# Avalon3.net
KiCad netlist of a schematic drawn in Altium Designer
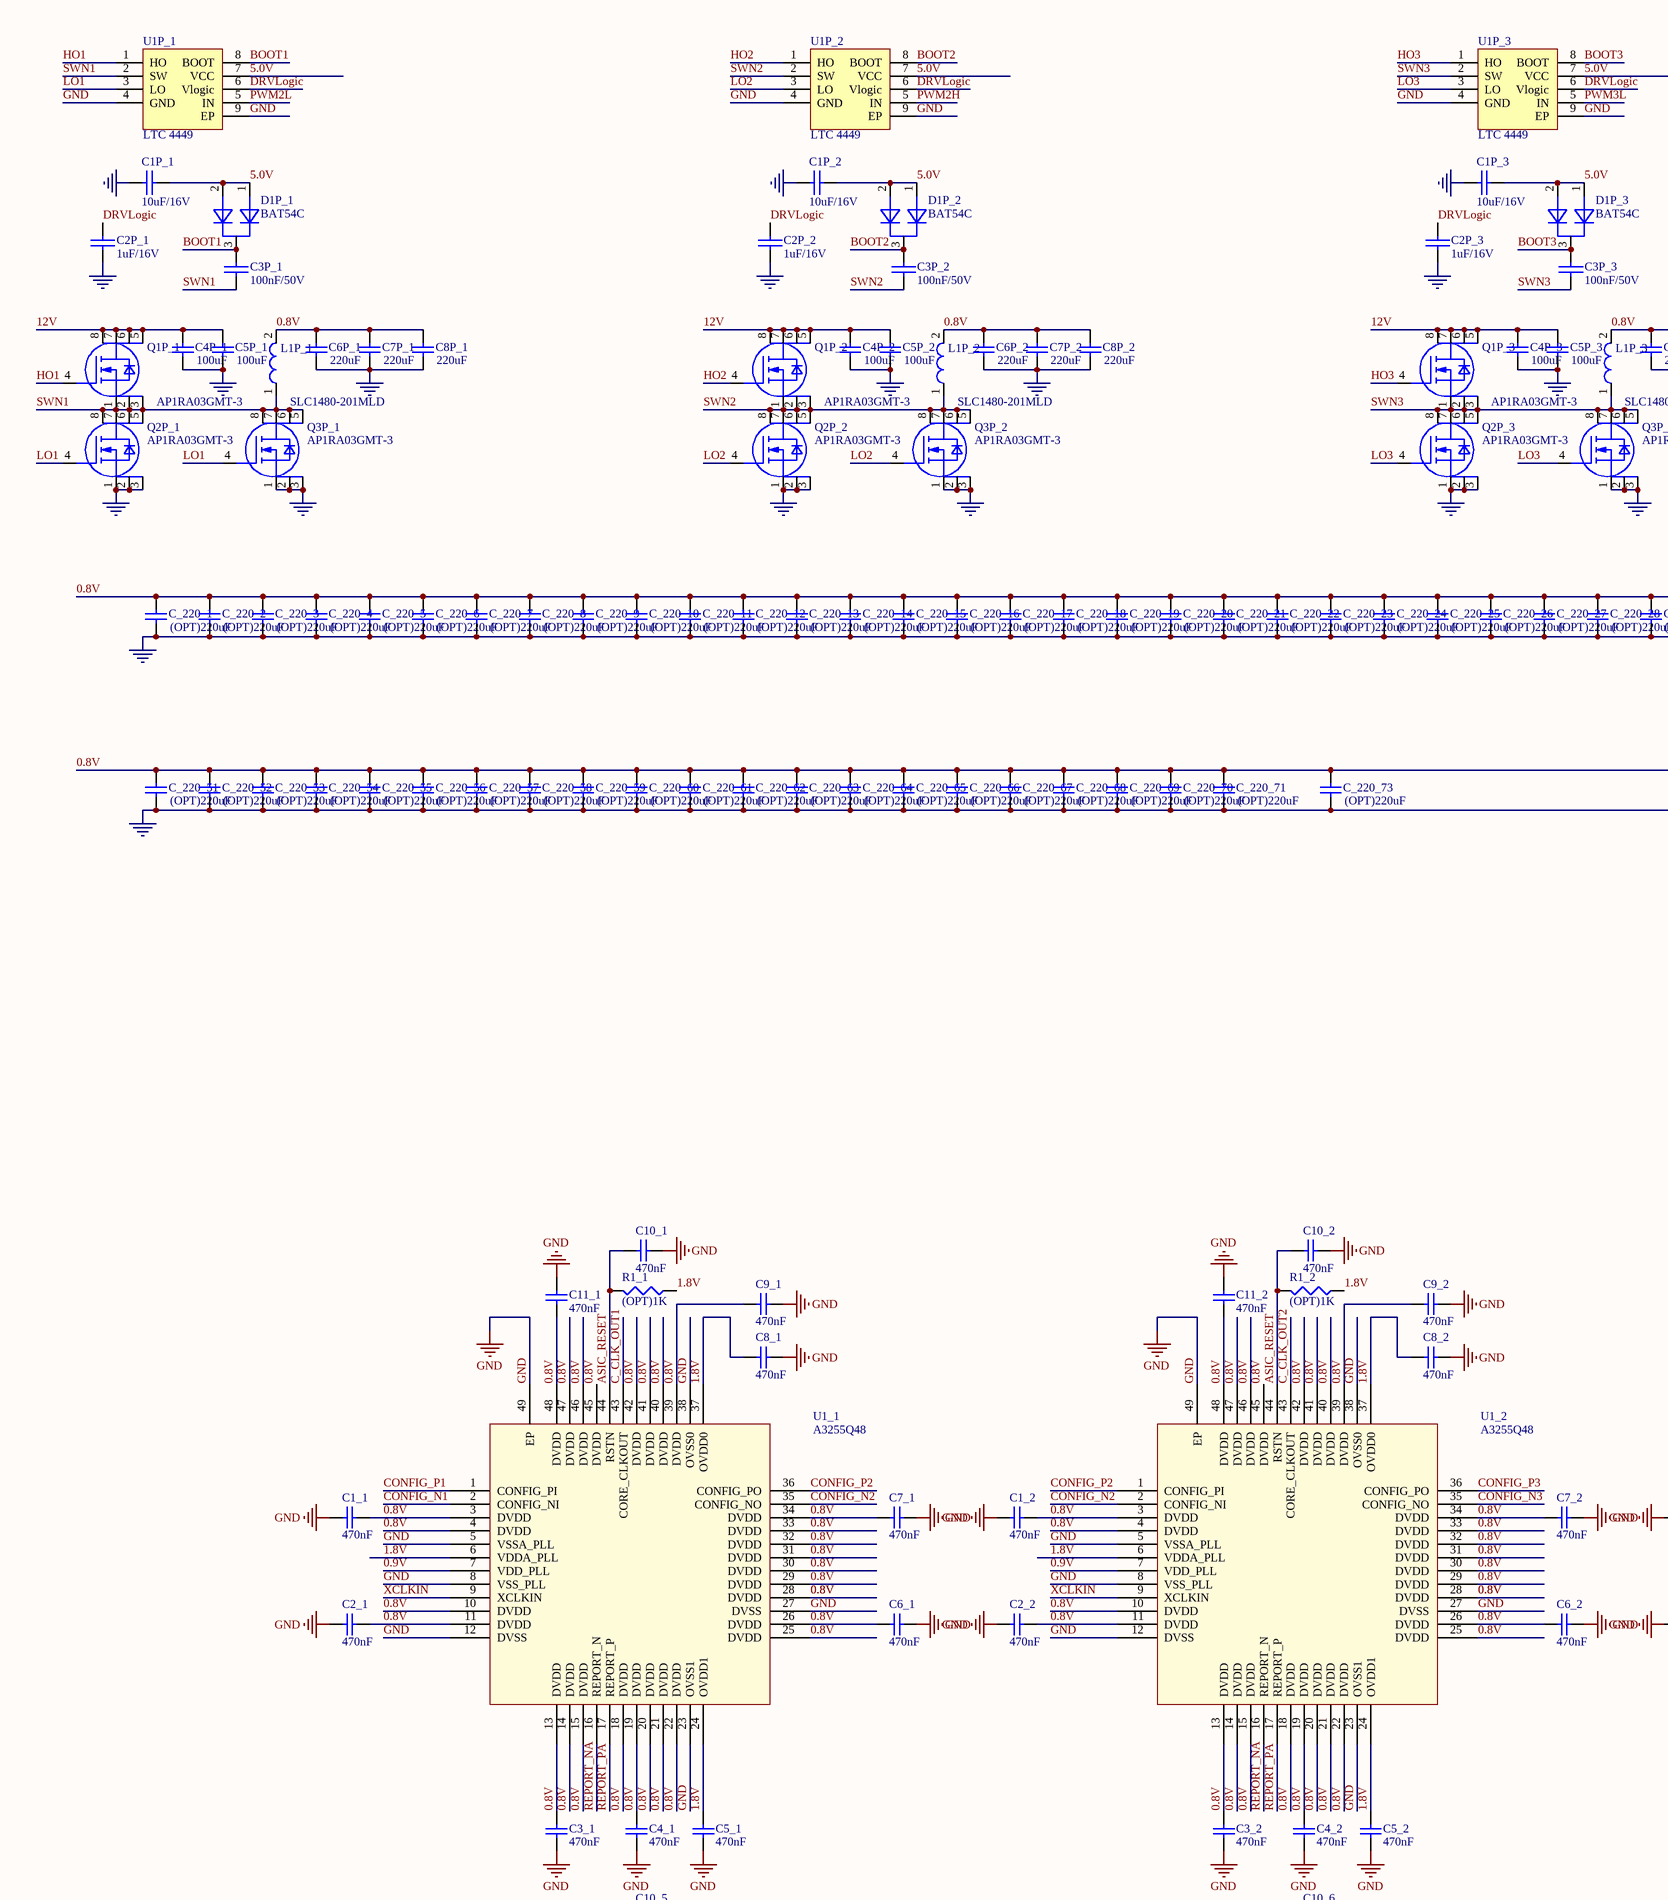
[diagram p0: Avalon3.SchDoc, top left]
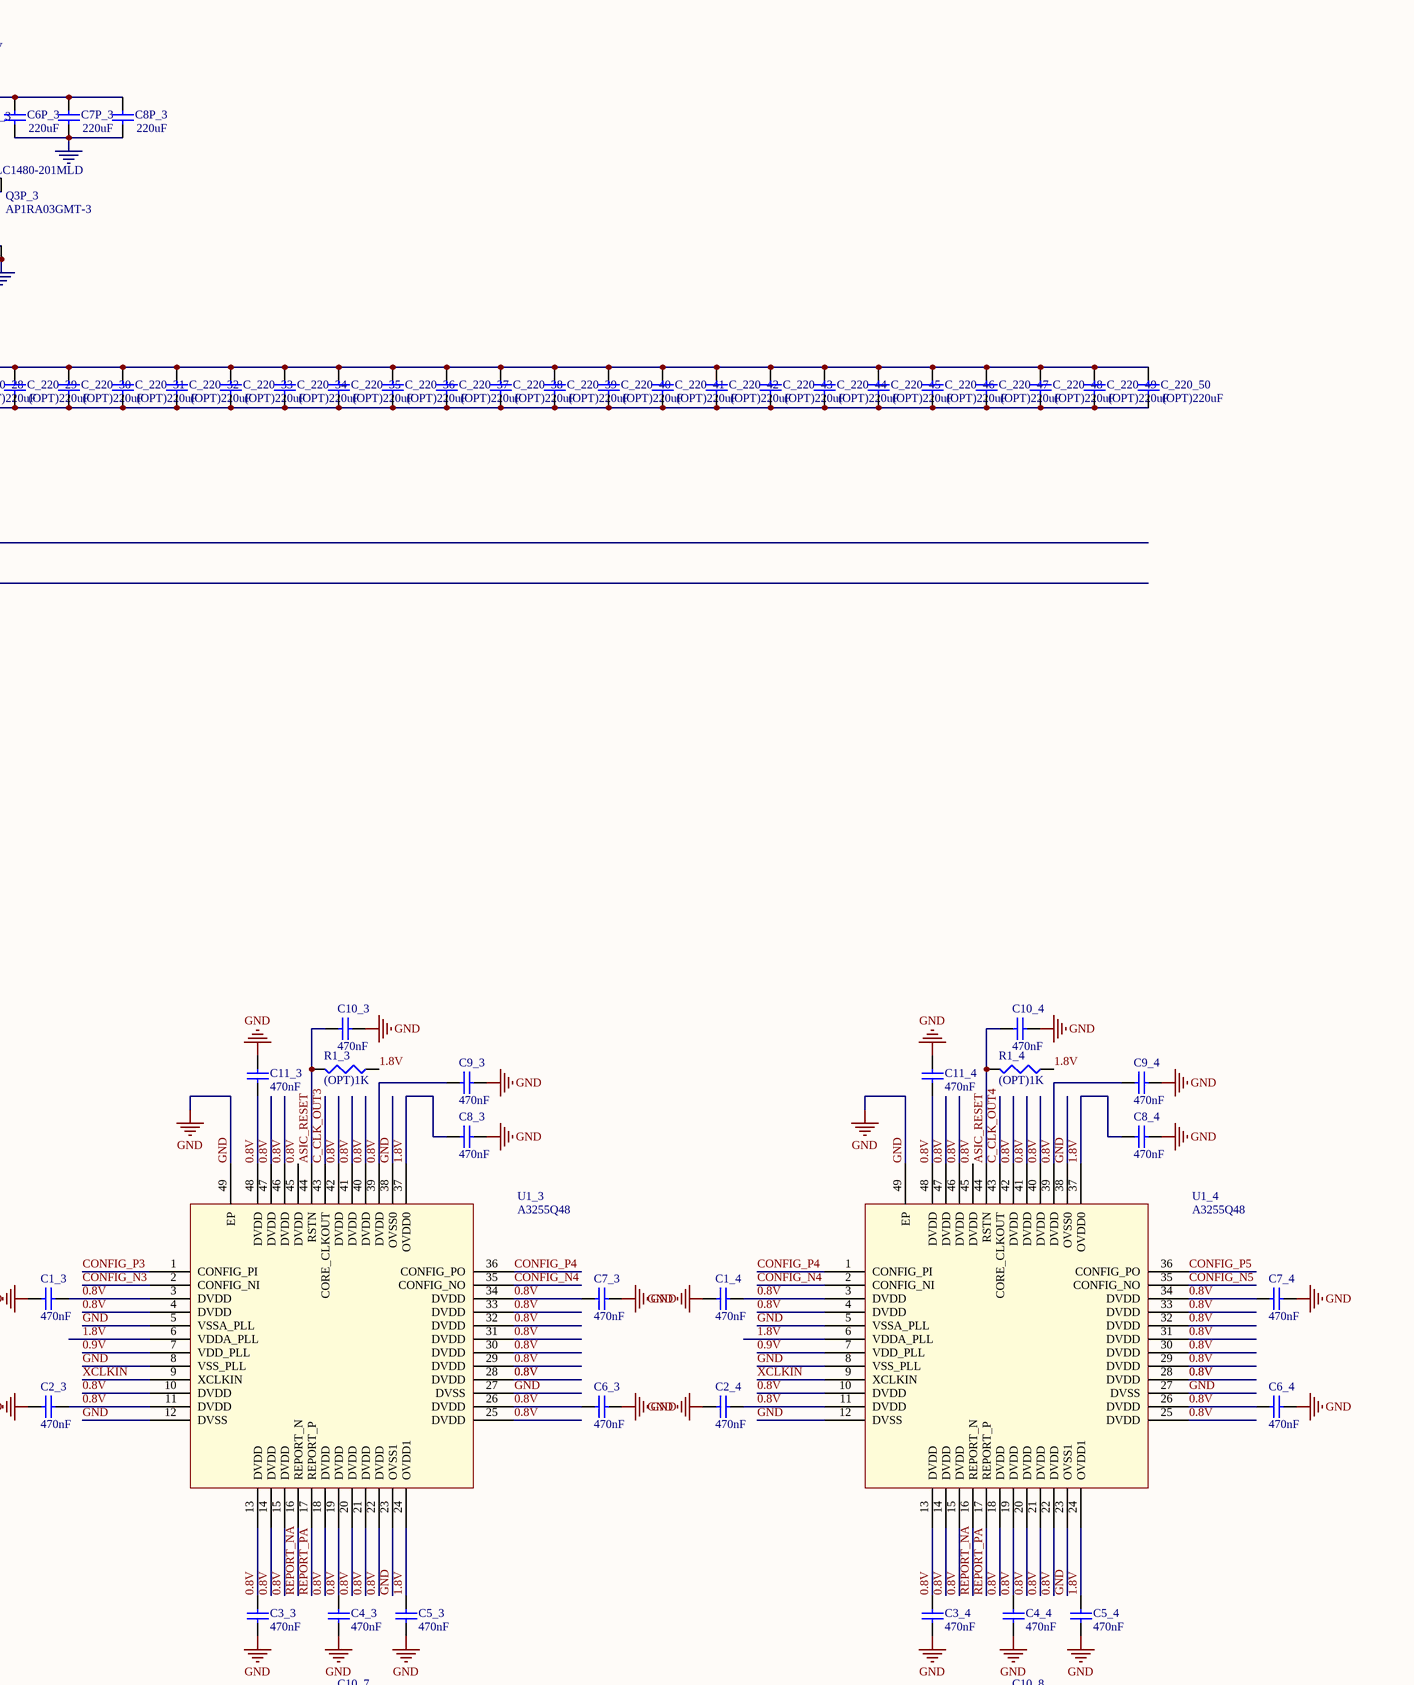
[diagram p1: Avalon3.SchDoc, top middle]
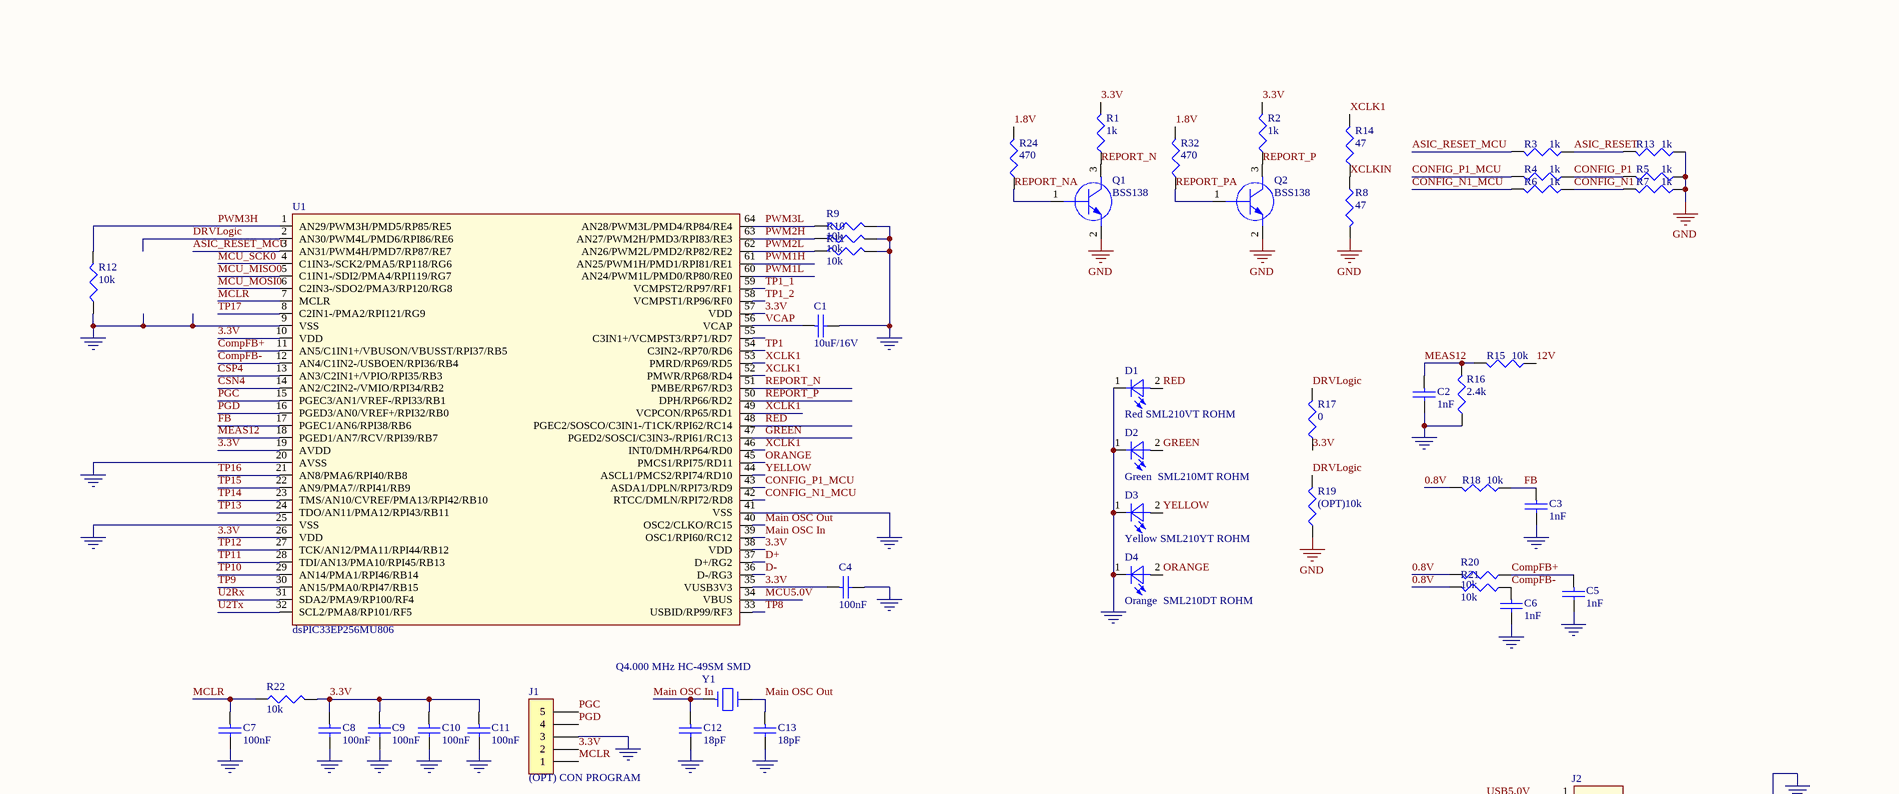
[diagram p2: Avalon3.SchDoc, top right]
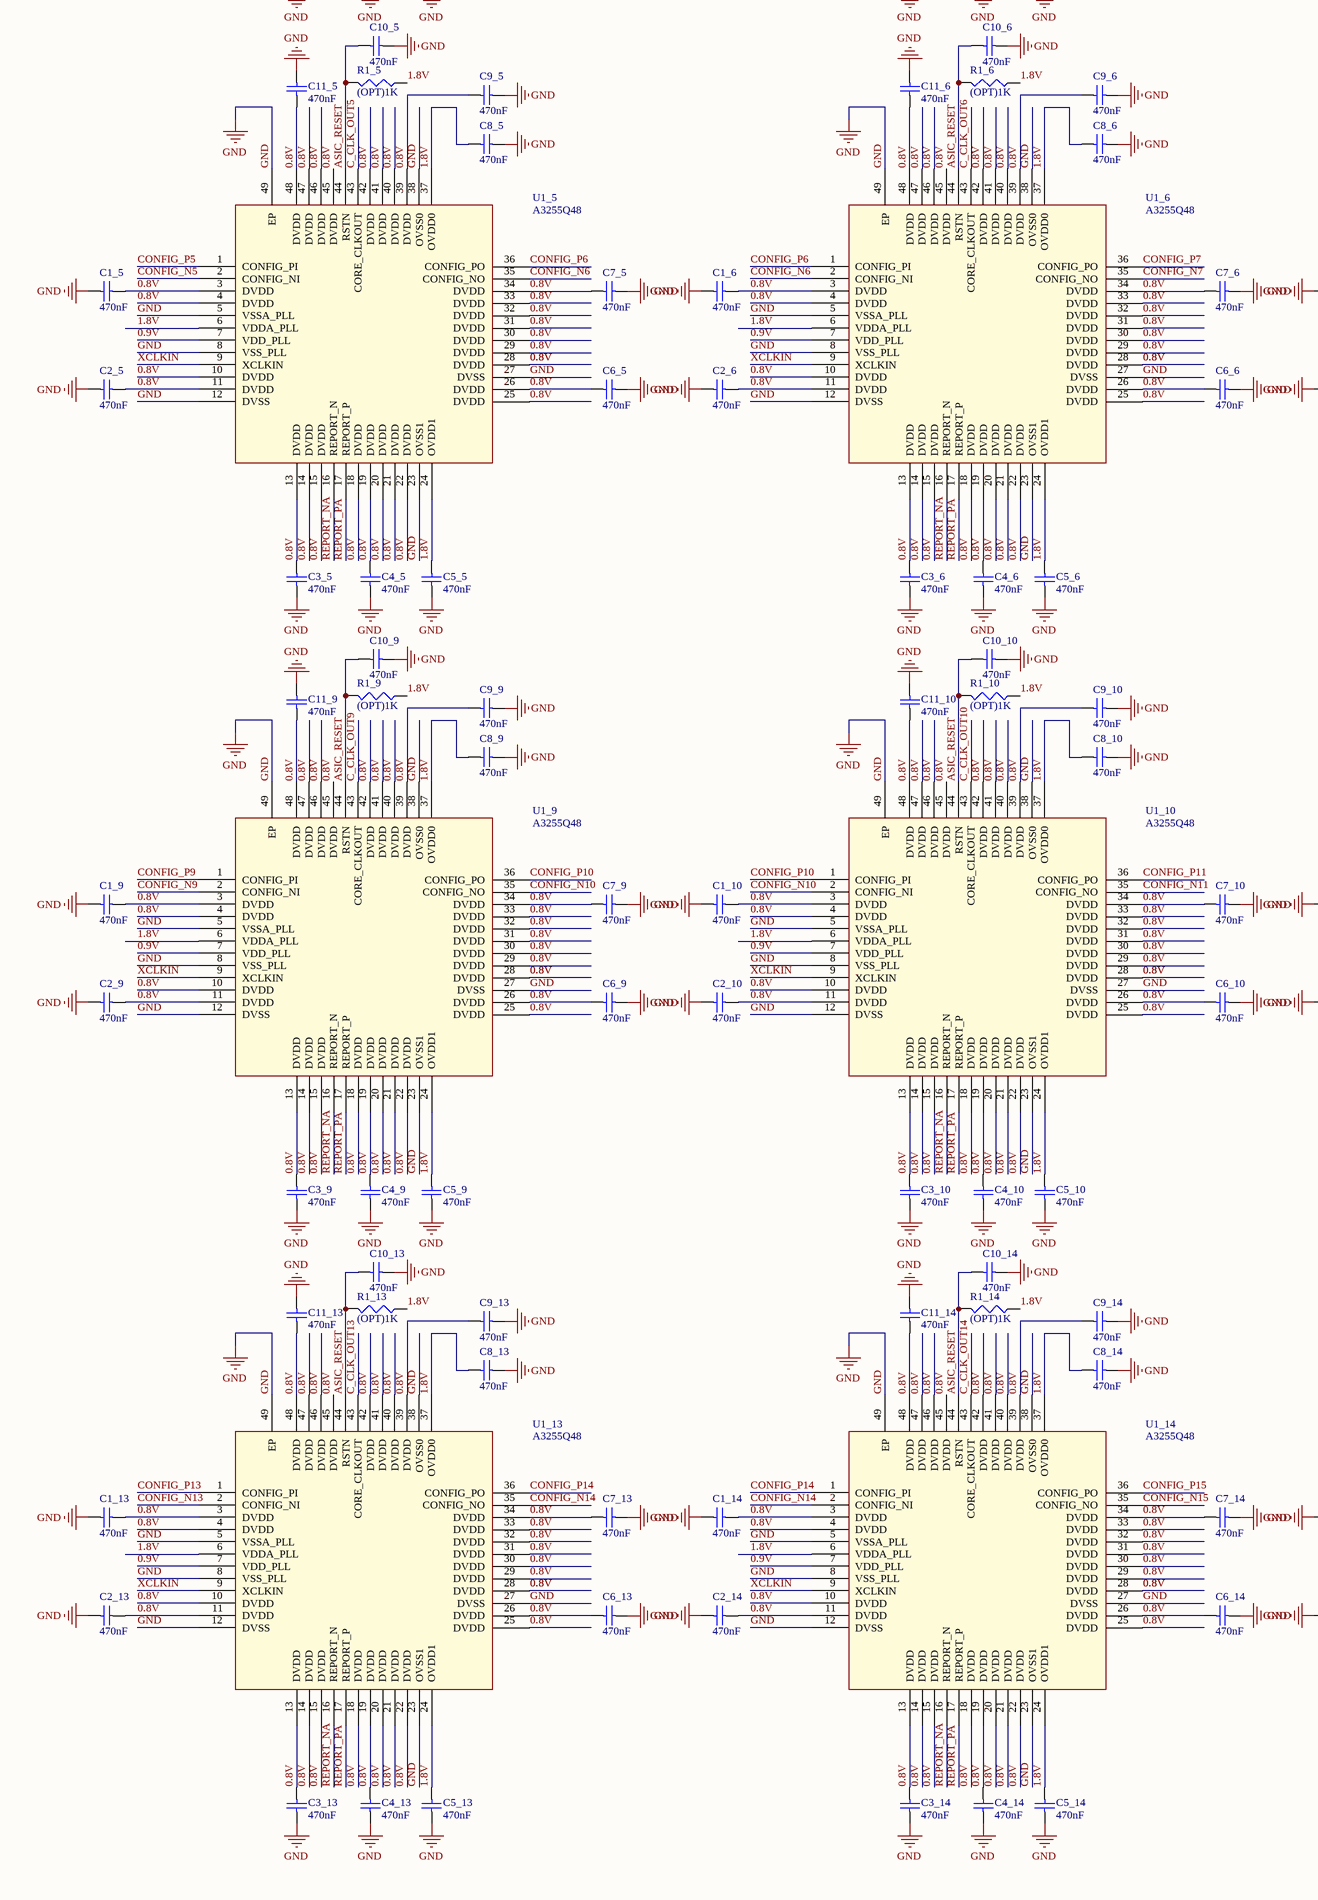
[diagram p3: Avalon3.SchDoc, bottom left]
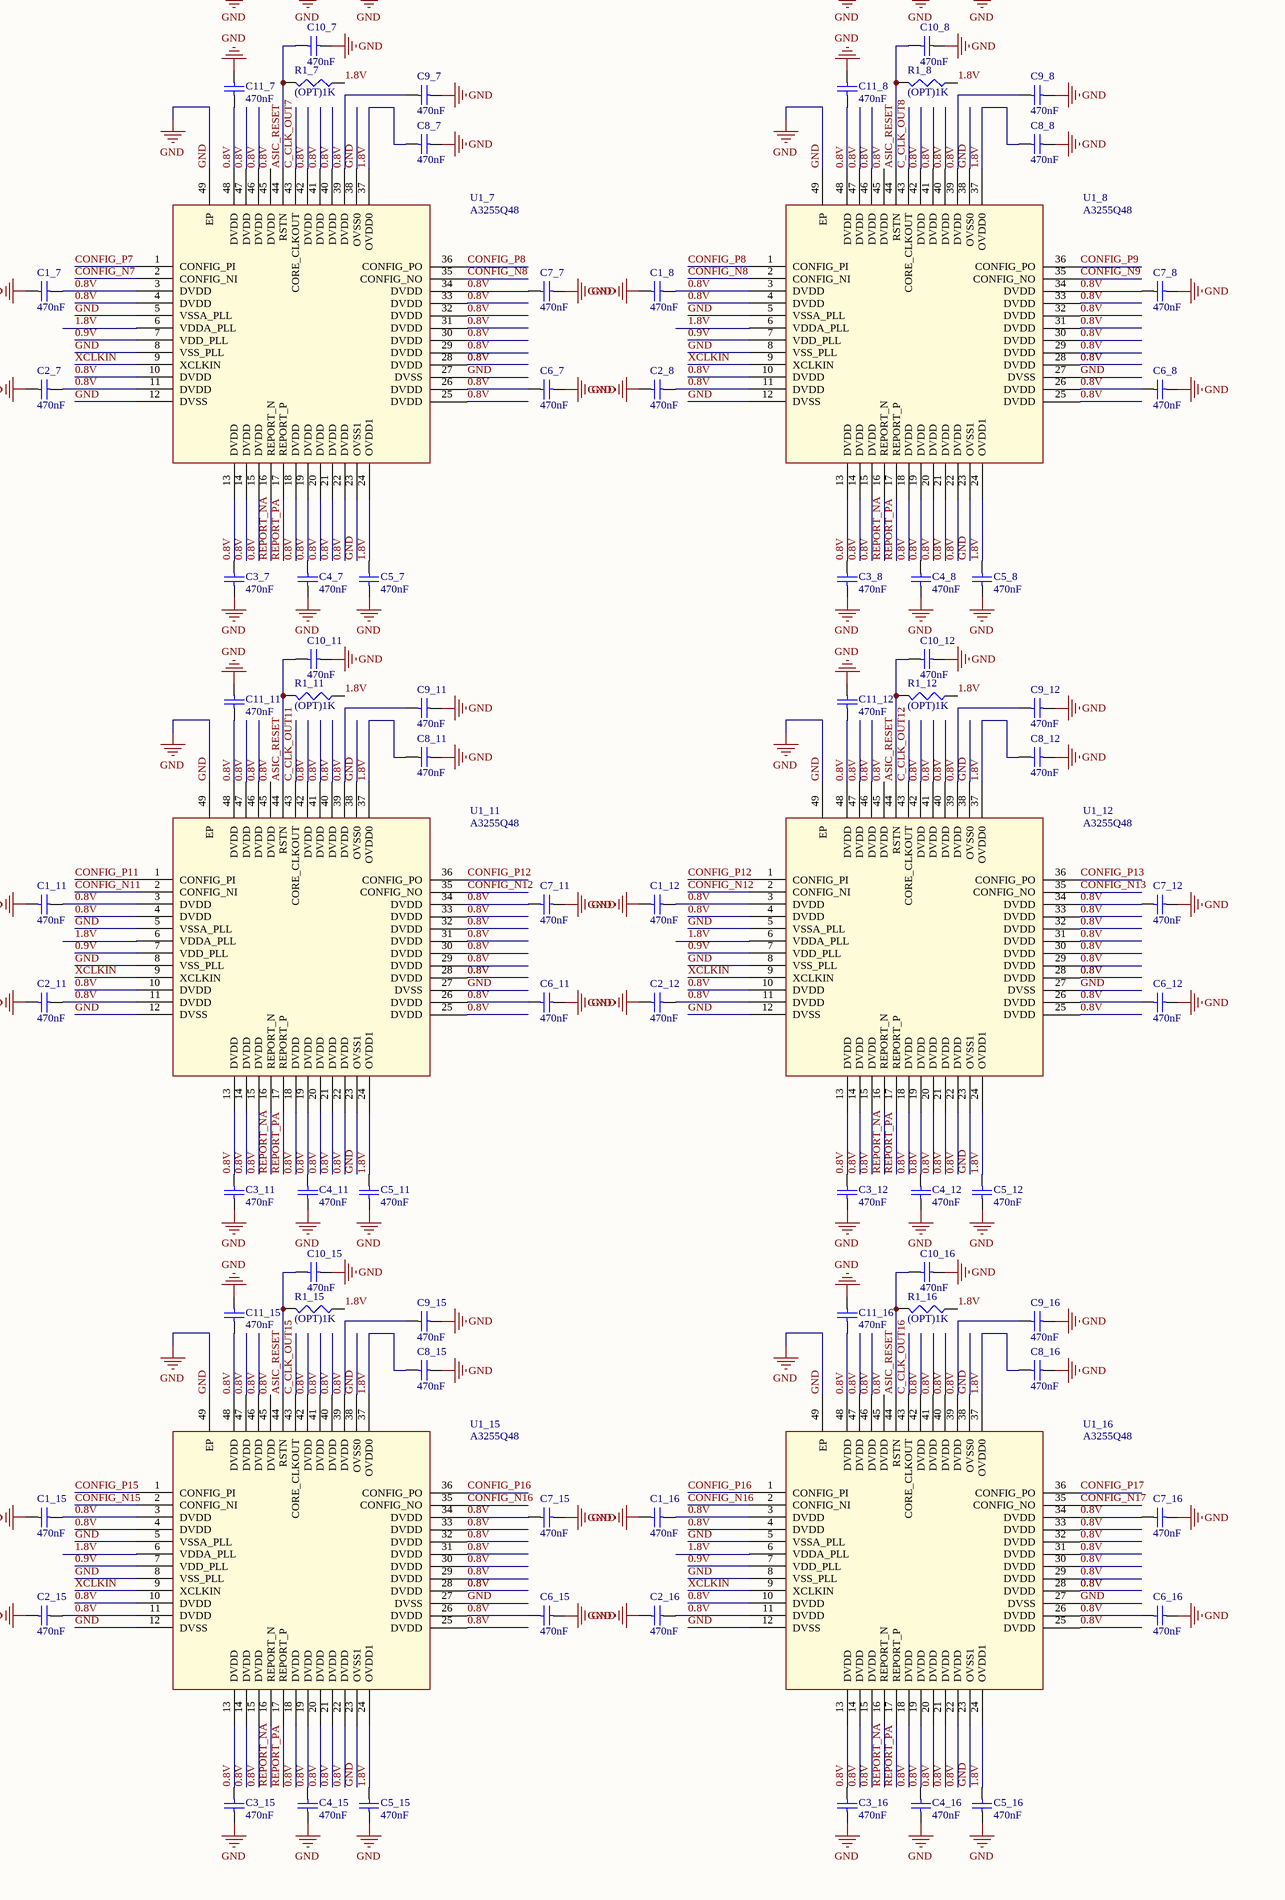
[diagram p4: Avalon3.SchDoc, bottom middle]
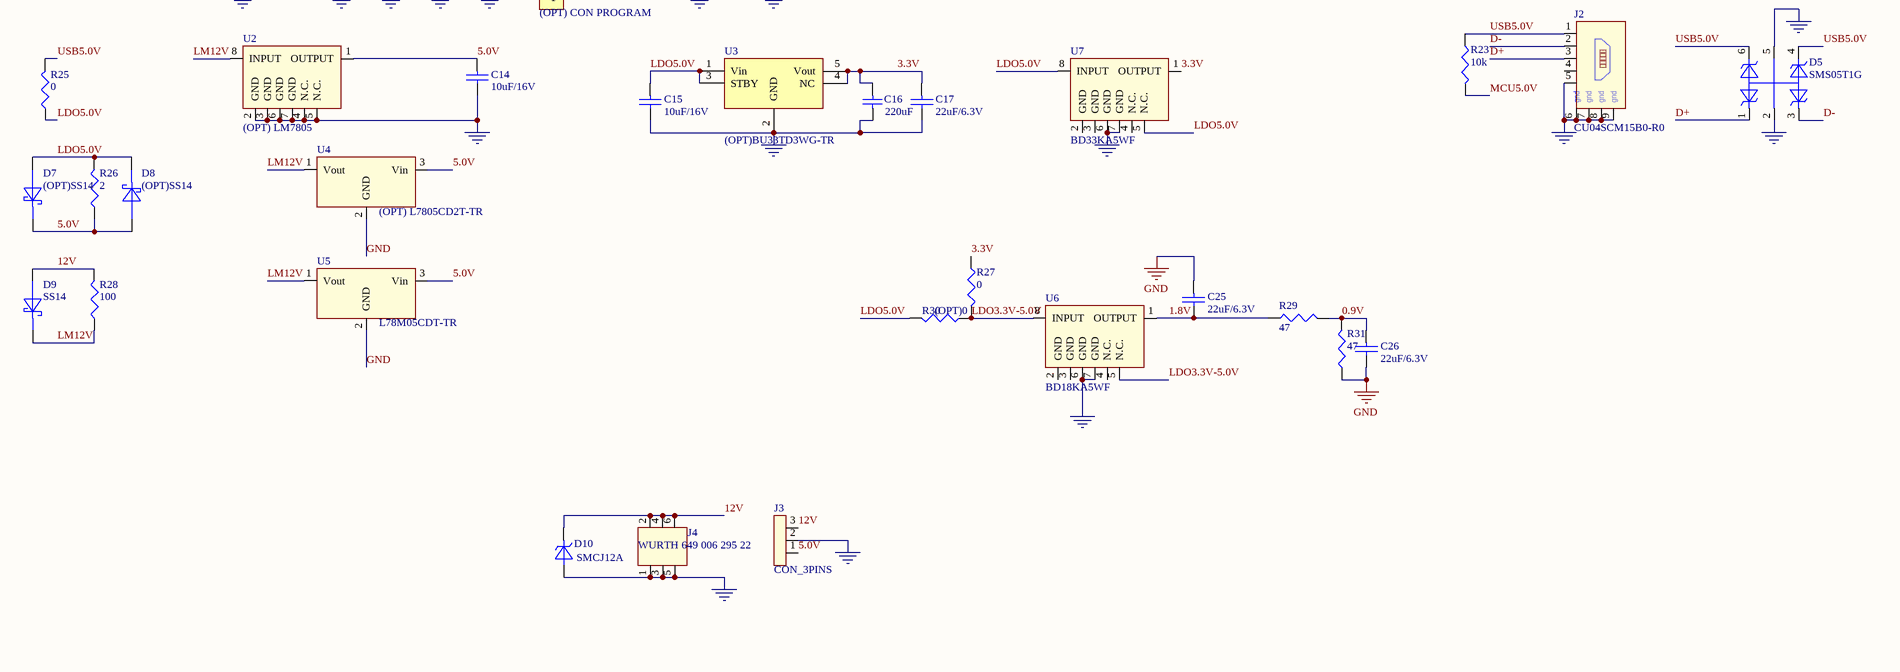
[diagram p5: Avalon3.SchDoc, bottom right]

(export (version "E")
  (design (tool "Eeschema 10.0.6"))
  (components
    (comp (ref "C1")
      (value "10uF/16V")
      (footprint "SMD_0805_CAPC2012X145N")
      (description "Capacitor")
      (libsource (lib "*") (part "CAP"))
    )
    (comp (ref "C1P_1")
      (value "10uF/16V")
      (footprint "SMD_0805_CAPC2012X145N")
      (description "Capacitor")
      (libsource (lib "*") (part "CAP"))
    )
    (comp (ref "C1P_2")
      (value "10uF/16V")
      (footprint "SMD_0805_CAPC2012X145N")
      (description "Capacitor")
      (libsource (lib "*") (part "CAP"))
    )
    (comp (ref "C1P_3")
      (value "10uF/16V")
      (footprint "SMD_0805_CAPC2012X145N")
      (description "Capacitor")
      (libsource (lib "*") (part "CAP"))
    )
    (comp (ref "C1_1")
      (value "470nF")
      (footprint "SMD_0603_CAPC1608X80N")
      (description "Capacitor (Semiconductor SIM Model)")
      (fields (field (name "PUBLISHER") "Altium Limited"))
      (libsource (lib "Miscellaneous Devices") (part "Cap Semi"))
    )
    (comp (ref "C1_2")
      (value "470nF")
      (footprint "SMD_0603_CAPC1608X80N")
      (description "Capacitor (Semiconductor SIM Model)")
      (fields (field (name "PUBLISHER") "Altium Limited"))
      (libsource (lib "Miscellaneous Devices") (part "Cap Semi"))
    )
    (comp (ref "C1_3")
      (value "470nF")
      (footprint "SMD_0603_CAPC1608X80N")
      (description "Capacitor (Semiconductor SIM Model)")
      (fields (field (name "PUBLISHER") "Altium Limited"))
      (libsource (lib "Miscellaneous Devices") (part "Cap Semi"))
    )
    (comp (ref "C1_4")
      (value "470nF")
      (footprint "SMD_0603_CAPC1608X80N")
      (description "Capacitor (Semiconductor SIM Model)")
      (fields (field (name "PUBLISHER") "Altium Limited"))
      (libsource (lib "Miscellaneous Devices") (part "Cap Semi"))
    )
    (comp (ref "C1_5")
      (value "470nF")
      (footprint "SMD_0603_CAPC1608X80N")
      (description "Capacitor (Semiconductor SIM Model)")
      (fields (field (name "PUBLISHER") "Altium Limited"))
      (libsource (lib "Miscellaneous Devices") (part "Cap Semi"))
    )
    (comp (ref "C1_6")
      (value "470nF")
      (footprint "SMD_0603_CAPC1608X80N")
      (description "Capacitor (Semiconductor SIM Model)")
      (fields (field (name "PUBLISHER") "Altium Limited"))
      (libsource (lib "Miscellaneous Devices") (part "Cap Semi"))
    )
    (comp (ref "C1_7")
      (value "470nF")
      (footprint "SMD_0603_CAPC1608X80N")
      (description "Capacitor (Semiconductor SIM Model)")
      (fields (field (name "PUBLISHER") "Altium Limited"))
      (libsource (lib "Miscellaneous Devices") (part "Cap Semi"))
    )
    (comp (ref "C1_8")
      (value "470nF")
      (footprint "SMD_0603_CAPC1608X80N")
      (description "Capacitor (Semiconductor SIM Model)")
      (fields (field (name "PUBLISHER") "Altium Limited"))
      (libsource (lib "Miscellaneous Devices") (part "Cap Semi"))
    )
    (comp (ref "C1_9")
      (value "470nF")
      (footprint "SMD_0603_CAPC1608X80N")
      (description "Capacitor (Semiconductor SIM Model)")
      (fields (field (name "PUBLISHER") "Altium Limited"))
      (libsource (lib "Miscellaneous Devices") (part "Cap Semi"))
    )
    (comp (ref "C1_10")
      (value "470nF")
      (footprint "SMD_0603_CAPC1608X80N")
      (description "Capacitor (Semiconductor SIM Model)")
      (fields (field (name "PUBLISHER") "Altium Limited"))
      (libsource (lib "Miscellaneous Devices") (part "Cap Semi"))
    )
    (comp (ref "C1_11")
      (value "470nF")
      (footprint "SMD_0603_CAPC1608X80N")
      (description "Capacitor (Semiconductor SIM Model)")
      (fields (field (name "PUBLISHER") "Altium Limited"))
      (libsource (lib "Miscellaneous Devices") (part "Cap Semi"))
    )
    (comp (ref "C1_12")
      (value "470nF")
      (footprint "SMD_0603_CAPC1608X80N")
      (description "Capacitor (Semiconductor SIM Model)")
      (fields (field (name "PUBLISHER") "Altium Limited"))
      (libsource (lib "Miscellaneous Devices") (part "Cap Semi"))
    )
    (comp (ref "C1_13")
      (value "470nF")
      (footprint "SMD_0603_CAPC1608X80N")
      (description "Capacitor (Semiconductor SIM Model)")
      (fields (field (name "PUBLISHER") "Altium Limited"))
      (libsource (lib "Miscellaneous Devices") (part "Cap Semi"))
    )
    (comp (ref "C1_14")
      (value "470nF")
      (footprint "SMD_0603_CAPC1608X80N")
      (description "Capacitor (Semiconductor SIM Model)")
      (fields (field (name "PUBLISHER") "Altium Limited"))
      (libsource (lib "Miscellaneous Devices") (part "Cap Semi"))
    )
    (comp (ref "C1_15")
      (value "470nF")
      (footprint "SMD_0603_CAPC1608X80N")
      (description "Capacitor (Semiconductor SIM Model)")
      (fields (field (name "PUBLISHER") "Altium Limited"))
      (libsource (lib "Miscellaneous Devices") (part "Cap Semi"))
    )
    (comp (ref "C1_16")
      (value "470nF")
      (footprint "SMD_0603_CAPC1608X80N")
      (description "Capacitor (Semiconductor SIM Model)")
      (fields (field (name "PUBLISHER") "Altium Limited"))
      (libsource (lib "Miscellaneous Devices") (part "Cap Semi"))
    )
    (comp (ref "C2")
      (value "1nF")
      (footprint "SMD_0603_CAPC1608X80N")
      (description "Capacitor")
      (libsource (lib "*") (part "CAP"))
    )
    (comp (ref "C2P_1")
      (value "1uF/16V")
      (footprint "SMD_0805_CAPC2012X145N")
      (description "Capacitor")
      (libsource (lib "*") (part "CAP"))
    )
    (comp (ref "C2P_2")
      (value "1uF/16V")
      (footprint "SMD_0805_CAPC2012X145N")
      (description "Capacitor")
      (libsource (lib "*") (part "CAP"))
    )
    (comp (ref "C2P_3")
      (value "1uF/16V")
      (footprint "SMD_0805_CAPC2012X145N")
      (description "Capacitor")
      (libsource (lib "*") (part "CAP"))
    )
    (comp (ref "C2_1")
      (value "470nF")
      (footprint "SMD_0603_CAPC1608X80N")
      (description "Capacitor (Semiconductor SIM Model)")
      (fields (field (name "PUBLISHER") "Altium Limited"))
      (libsource (lib "Miscellaneous Devices") (part "Cap Semi"))
    )
    (comp (ref "C2_2")
      (value "470nF")
      (footprint "SMD_0603_CAPC1608X80N")
      (description "Capacitor (Semiconductor SIM Model)")
      (fields (field (name "PUBLISHER") "Altium Limited"))
      (libsource (lib "Miscellaneous Devices") (part "Cap Semi"))
    )
    (comp (ref "C2_3")
      (value "470nF")
      (footprint "SMD_0603_CAPC1608X80N")
      (description "Capacitor (Semiconductor SIM Model)")
      (fields (field (name "PUBLISHER") "Altium Limited"))
      (libsource (lib "Miscellaneous Devices") (part "Cap Semi"))
    )
    (comp (ref "C2_4")
      (value "470nF")
      (footprint "SMD_0603_CAPC1608X80N")
      (description "Capacitor (Semiconductor SIM Model)")
      (fields (field (name "PUBLISHER") "Altium Limited"))
      (libsource (lib "Miscellaneous Devices") (part "Cap Semi"))
    )
    (comp (ref "C2_5")
      (value "470nF")
      (footprint "SMD_0603_CAPC1608X80N")
      (description "Capacitor (Semiconductor SIM Model)")
      (fields (field (name "PUBLISHER") "Altium Limited"))
      (libsource (lib "Miscellaneous Devices") (part "Cap Semi"))
    )
    (comp (ref "C2_6")
      (value "470nF")
      (footprint "SMD_0603_CAPC1608X80N")
      (description "Capacitor (Semiconductor SIM Model)")
      (fields (field (name "PUBLISHER") "Altium Limited"))
      (libsource (lib "Miscellaneous Devices") (part "Cap Semi"))
    )
    (comp (ref "C2_7")
      (value "470nF")
      (footprint "SMD_0603_CAPC1608X80N")
      (description "Capacitor (Semiconductor SIM Model)")
      (fields (field (name "PUBLISHER") "Altium Limited"))
      (libsource (lib "Miscellaneous Devices") (part "Cap Semi"))
    )
    (comp (ref "C2_8")
      (value "470nF")
      (footprint "SMD_0603_CAPC1608X80N")
      (description "Capacitor (Semiconductor SIM Model)")
      (fields (field (name "PUBLISHER") "Altium Limited"))
      (libsource (lib "Miscellaneous Devices") (part "Cap Semi"))
    )
    (comp (ref "C2_9")
      (value "470nF")
      (footprint "SMD_0603_CAPC1608X80N")
      (description "Capacitor (Semiconductor SIM Model)")
      (fields (field (name "PUBLISHER") "Altium Limited"))
      (libsource (lib "Miscellaneous Devices") (part "Cap Semi"))
    )
    (comp (ref "C2_10")
      (value "470nF")
      (footprint "SMD_0603_CAPC1608X80N")
      (description "Capacitor (Semiconductor SIM Model)")
      (fields (field (name "PUBLISHER") "Altium Limited"))
      (libsource (lib "Miscellaneous Devices") (part "Cap Semi"))
    )
    (comp (ref "C2_11")
      (value "470nF")
      (footprint "SMD_0603_CAPC1608X80N")
      (description "Capacitor (Semiconductor SIM Model)")
      (fields (field (name "PUBLISHER") "Altium Limited"))
      (libsource (lib "Miscellaneous Devices") (part "Cap Semi"))
    )
    (comp (ref "C2_12")
      (value "470nF")
      (footprint "SMD_0603_CAPC1608X80N")
      (description "Capacitor (Semiconductor SIM Model)")
      (fields (field (name "PUBLISHER") "Altium Limited"))
      (libsource (lib "Miscellaneous Devices") (part "Cap Semi"))
    )
    (comp (ref "C2_13")
      (value "470nF")
      (footprint "SMD_0603_CAPC1608X80N")
      (description "Capacitor (Semiconductor SIM Model)")
      (fields (field (name "PUBLISHER") "Altium Limited"))
      (libsource (lib "Miscellaneous Devices") (part "Cap Semi"))
    )
    (comp (ref "C2_14")
      (value "470nF")
      (footprint "SMD_0603_CAPC1608X80N")
      (description "Capacitor (Semiconductor SIM Model)")
      (fields (field (name "PUBLISHER") "Altium Limited"))
      (libsource (lib "Miscellaneous Devices") (part "Cap Semi"))
    )
    (comp (ref "C2_15")
      (value "470nF")
      (footprint "SMD_0603_CAPC1608X80N")
      (description "Capacitor (Semiconductor SIM Model)")
      (fields (field (name "PUBLISHER") "Altium Limited"))
      (libsource (lib "Miscellaneous Devices") (part "Cap Semi"))
    )
    (comp (ref "C2_16")
      (value "470nF")
      (footprint "SMD_0603_CAPC1608X80N")
      (description "Capacitor (Semiconductor SIM Model)")
      (fields (field (name "PUBLISHER") "Altium Limited"))
      (libsource (lib "Miscellaneous Devices") (part "Cap Semi"))
    )
    (comp (ref "C3")
      (value "1nF")
      (footprint "SMD_0603_CAPC1608X80N")
      (description "Capacitor")
      (libsource (lib "*") (part "CAP"))
    )
    (comp (ref "C3P_1")
      (value "100nF/50V")
      (footprint "SMD_0805_CAPC2012X145N")
      (description "Capacitor")
      (libsource (lib "*") (part "CAP"))
    )
    (comp (ref "C3P_2")
      (value "100nF/50V")
      (footprint "SMD_0805_CAPC2012X145N")
      (description "Capacitor")
      (libsource (lib "*") (part "CAP"))
    )
    (comp (ref "C3P_3")
      (value "100nF/50V")
      (footprint "SMD_0805_CAPC2012X145N")
      (description "Capacitor")
      (libsource (lib "*") (part "CAP"))
    )
    (comp (ref "C3_1")
      (value "470nF")
      (footprint "SMD_0603_CAPC1608X80N")
      (description "Capacitor (Semiconductor SIM Model)")
      (fields (field (name "PUBLISHER") "Altium Limited"))
      (libsource (lib "Miscellaneous Devices") (part "Cap Semi"))
    )
    (comp (ref "C3_2")
      (value "470nF")
      (footprint "SMD_0603_CAPC1608X80N")
      (description "Capacitor (Semiconductor SIM Model)")
      (fields (field (name "PUBLISHER") "Altium Limited"))
      (libsource (lib "Miscellaneous Devices") (part "Cap Semi"))
    )
    (comp (ref "C3_3")
      (value "470nF")
      (footprint "SMD_0603_CAPC1608X80N")
      (description "Capacitor (Semiconductor SIM Model)")
      (fields (field (name "PUBLISHER") "Altium Limited"))
      (libsource (lib "Miscellaneous Devices") (part "Cap Semi"))
    )
    (comp (ref "C3_4")
      (value "470nF")
      (footprint "SMD_0603_CAPC1608X80N")
      (description "Capacitor (Semiconductor SIM Model)")
      (fields (field (name "PUBLISHER") "Altium Limited"))
      (libsource (lib "Miscellaneous Devices") (part "Cap Semi"))
    )
    (comp (ref "C3_5")
      (value "470nF")
      (footprint "SMD_0603_CAPC1608X80N")
      (description "Capacitor (Semiconductor SIM Model)")
      (fields (field (name "PUBLISHER") "Altium Limited"))
      (libsource (lib "Miscellaneous Devices") (part "Cap Semi"))
    )
    (comp (ref "C3_6")
      (value "470nF")
      (footprint "SMD_0603_CAPC1608X80N")
      (description "Capacitor (Semiconductor SIM Model)")
      (fields (field (name "PUBLISHER") "Altium Limited"))
      (libsource (lib "Miscellaneous Devices") (part "Cap Semi"))
    )
    (comp (ref "C3_7")
      (value "470nF")
      (footprint "SMD_0603_CAPC1608X80N")
      (description "Capacitor (Semiconductor SIM Model)")
      (fields (field (name "PUBLISHER") "Altium Limited"))
      (libsource (lib "Miscellaneous Devices") (part "Cap Semi"))
    )
    (comp (ref "C3_8")
      (value "470nF")
      (footprint "SMD_0603_CAPC1608X80N")
      (description "Capacitor (Semiconductor SIM Model)")
      (fields (field (name "PUBLISHER") "Altium Limited"))
      (libsource (lib "Miscellaneous Devices") (part "Cap Semi"))
    )
    (comp (ref "C3_9")
      (value "470nF")
      (footprint "SMD_0603_CAPC1608X80N")
      (description "Capacitor (Semiconductor SIM Model)")
      (fields (field (name "PUBLISHER") "Altium Limited"))
      (libsource (lib "Miscellaneous Devices") (part "Cap Semi"))
    )
    (comp (ref "C3_10")
      (value "470nF")
      (footprint "SMD_0603_CAPC1608X80N")
      (description "Capacitor (Semiconductor SIM Model)")
      (fields (field (name "PUBLISHER") "Altium Limited"))
      (libsource (lib "Miscellaneous Devices") (part "Cap Semi"))
    )
    (comp (ref "C3_11")
      (value "470nF")
      (footprint "SMD_0603_CAPC1608X80N")
      (description "Capacitor (Semiconductor SIM Model)")
      (fields (field (name "PUBLISHER") "Altium Limited"))
      (libsource (lib "Miscellaneous Devices") (part "Cap Semi"))
    )
    (comp (ref "C3_12")
      (value "470nF")
      (footprint "SMD_0603_CAPC1608X80N")
      (description "Capacitor (Semiconductor SIM Model)")
      (fields (field (name "PUBLISHER") "Altium Limited"))
      (libsource (lib "Miscellaneous Devices") (part "Cap Semi"))
    )
    (comp (ref "C3_13")
      (value "470nF")
      (footprint "SMD_0603_CAPC1608X80N")
      (description "Capacitor (Semiconductor SIM Model)")
      (fields (field (name "PUBLISHER") "Altium Limited"))
      (libsource (lib "Miscellaneous Devices") (part "Cap Semi"))
    )
    (comp (ref "C3_14")
      (value "470nF")
      (footprint "SMD_0603_CAPC1608X80N")
      (description "Capacitor (Semiconductor SIM Model)")
      (fields (field (name "PUBLISHER") "Altium Limited"))
      (libsource (lib "Miscellaneous Devices") (part "Cap Semi"))
    )
    (comp (ref "C3_15")
      (value "470nF")
      (footprint "SMD_0603_CAPC1608X80N")
      (description "Capacitor (Semiconductor SIM Model)")
      (fields (field (name "PUBLISHER") "Altium Limited"))
      (libsource (lib "Miscellaneous Devices") (part "Cap Semi"))
    )
    (comp (ref "C3_16")
      (value "470nF")
      (footprint "SMD_0603_CAPC1608X80N")
      (description "Capacitor (Semiconductor SIM Model)")
      (fields (field (name "PUBLISHER") "Altium Limited"))
      (libsource (lib "Miscellaneous Devices") (part "Cap Semi"))
    )
    (comp (ref "C4")
      (value "100nF")
      (footprint "SMD_0603_CAPC1608X80N")
      (description "Capacitor")
      (libsource (lib "*") (part "CAP"))
    )
    (comp (ref "C4P_1")
      (value "100uF")
      (footprint "SMD_1210_CAPC3225X279N")
      (description "CL32A227MQVNNNE 220UF 6.3V 20% X5R 1210")
      (fields (field (name "PUBLISHER") "Altium Limited"))
      (libsource (lib "Miscellaneous Devices") (part "Cap Semi"))
    )
    (comp (ref "C4P_2")
      (value "100uF")
      (footprint "SMD_1210_CAPC3225X279N")
      (description "CL32A227MQVNNNE 220UF 6.3V 20% X5R 1210")
      (fields (field (name "PUBLISHER") "Altium Limited"))
      (libsource (lib "Miscellaneous Devices") (part "Cap Semi"))
    )
    (comp (ref "C4P_3")
      (value "100uF")
      (footprint "SMD_1210_CAPC3225X279N")
      (description "CL32A227MQVNNNE 220UF 6.3V 20% X5R 1210")
      (fields (field (name "PUBLISHER") "Altium Limited"))
      (libsource (lib "Miscellaneous Devices") (part "Cap Semi"))
    )
    (comp (ref "C4_1")
      (value "470nF")
      (footprint "SMD_0603_CAPC1608X80N")
      (description "Capacitor (Semiconductor SIM Model)")
      (fields (field (name "PUBLISHER") "Altium Limited"))
      (libsource (lib "Miscellaneous Devices") (part "Cap Semi"))
    )
    (comp (ref "C4_2")
      (value "470nF")
      (footprint "SMD_0603_CAPC1608X80N")
      (description "Capacitor (Semiconductor SIM Model)")
      (fields (field (name "PUBLISHER") "Altium Limited"))
      (libsource (lib "Miscellaneous Devices") (part "Cap Semi"))
    )
    (comp (ref "C4_3")
      (value "470nF")
      (footprint "SMD_0603_CAPC1608X80N")
      (description "Capacitor (Semiconductor SIM Model)")
      (fields (field (name "PUBLISHER") "Altium Limited"))
      (libsource (lib "Miscellaneous Devices") (part "Cap Semi"))
    )
    (comp (ref "C4_4")
      (value "470nF")
      (footprint "SMD_0603_CAPC1608X80N")
      (description "Capacitor (Semiconductor SIM Model)")
      (fields (field (name "PUBLISHER") "Altium Limited"))
      (libsource (lib "Miscellaneous Devices") (part "Cap Semi"))
    )
    (comp (ref "C4_5")
      (value "470nF")
      (footprint "SMD_0603_CAPC1608X80N")
      (description "Capacitor (Semiconductor SIM Model)")
      (fields (field (name "PUBLISHER") "Altium Limited"))
      (libsource (lib "Miscellaneous Devices") (part "Cap Semi"))
    )
    (comp (ref "C4_6")
      (value "470nF")
      (footprint "SMD_0603_CAPC1608X80N")
      (description "Capacitor (Semiconductor SIM Model)")
      (fields (field (name "PUBLISHER") "Altium Limited"))
      (libsource (lib "Miscellaneous Devices") (part "Cap Semi"))
    )
    (comp (ref "C4_7")
      (value "470nF")
      (footprint "SMD_0603_CAPC1608X80N")
      (description "Capacitor (Semiconductor SIM Model)")
      (fields (field (name "PUBLISHER") "Altium Limited"))
      (libsource (lib "Miscellaneous Devices") (part "Cap Semi"))
    )
    (comp (ref "C4_8")
      (value "470nF")
      (footprint "SMD_0603_CAPC1608X80N")
      (description "Capacitor (Semiconductor SIM Model)")
      (fields (field (name "PUBLISHER") "Altium Limited"))
      (libsource (lib "Miscellaneous Devices") (part "Cap Semi"))
    )
    (comp (ref "C4_9")
      (value "470nF")
      (footprint "SMD_0603_CAPC1608X80N")
      (description "Capacitor (Semiconductor SIM Model)")
      (fields (field (name "PUBLISHER") "Altium Limited"))
      (libsource (lib "Miscellaneous Devices") (part "Cap Semi"))
    )
    (comp (ref "C4_10")
      (value "470nF")
      (footprint "SMD_0603_CAPC1608X80N")
      (description "Capacitor (Semiconductor SIM Model)")
      (fields (field (name "PUBLISHER") "Altium Limited"))
      (libsource (lib "Miscellaneous Devices") (part "Cap Semi"))
    )
    (comp (ref "C4_11")
      (value "470nF")
      (footprint "SMD_0603_CAPC1608X80N")
      (description "Capacitor (Semiconductor SIM Model)")
      (fields (field (name "PUBLISHER") "Altium Limited"))
      (libsource (lib "Miscellaneous Devices") (part "Cap Semi"))
    )
    (comp (ref "C4_12")
      (value "470nF")
      (footprint "SMD_0603_CAPC1608X80N")
      (description "Capacitor (Semiconductor SIM Model)")
      (fields (field (name "PUBLISHER") "Altium Limited"))
      (libsource (lib "Miscellaneous Devices") (part "Cap Semi"))
    )
    (comp (ref "C4_13")
      (value "470nF")
      (footprint "SMD_0603_CAPC1608X80N")
      (description "Capacitor (Semiconductor SIM Model)")
      (fields (field (name "PUBLISHER") "Altium Limited"))
      (libsource (lib "Miscellaneous Devices") (part "Cap Semi"))
    )
    (comp (ref "C4_14")
      (value "470nF")
      (footprint "SMD_0603_CAPC1608X80N")
      (description "Capacitor (Semiconductor SIM Model)")
      (fields (field (name "PUBLISHER") "Altium Limited"))
      (libsource (lib "Miscellaneous Devices") (part "Cap Semi"))
    )
    (comp (ref "C4_15")
      (value "470nF")
      (footprint "SMD_0603_CAPC1608X80N")
      (description "Capacitor (Semiconductor SIM Model)")
      (fields (field (name "PUBLISHER") "Altium Limited"))
      (libsource (lib "Miscellaneous Devices") (part "Cap Semi"))
    )
    (comp (ref "C4_16")
      (value "470nF")
      (footprint "SMD_0603_CAPC1608X80N")
      (description "Capacitor (Semiconductor SIM Model)")
      (fields (field (name "PUBLISHER") "Altium Limited"))
      (libsource (lib "Miscellaneous Devices") (part "Cap Semi"))
    )
    (comp (ref "C5")
      (value "1nF")
      (footprint "SMD_0603_CAPC1608X80N")
      (description "Capacitor")
      (libsource (lib "*") (part "CAP"))
    )
    (comp (ref "C5P_1")
      (value "100uF")
      (footprint "SMD_1210_CAPC3225X279N")
      (description "CL32A227MQVNNNE 220UF 6.3V 20% X5R 1210")
      (fields (field (name "PUBLISHER") "Altium Limited"))
      (libsource (lib "Miscellaneous Devices") (part "Cap Semi"))
    )
    (comp (ref "C5P_2")
      (value "100uF")
      (footprint "SMD_1210_CAPC3225X279N")
      (description "CL32A227MQVNNNE 220UF 6.3V 20% X5R 1210")
      (fields (field (name "PUBLISHER") "Altium Limited"))
      (libsource (lib "Miscellaneous Devices") (part "Cap Semi"))
    )
    (comp (ref "C5P_3")
      (value "100uF")
      (footprint "SMD_1210_CAPC3225X279N")
      (description "CL32A227MQVNNNE 220UF 6.3V 20% X5R 1210")
      (fields (field (name "PUBLISHER") "Altium Limited"))
      (libsource (lib "Miscellaneous Devices") (part "Cap Semi"))
    )
    (comp (ref "C5_1")
      (value "470nF")
      (footprint "SMD_0603_CAPC1608X80N")
      (description "Capacitor (Semiconductor SIM Model)")
      (fields (field (name "PUBLISHER") "Altium Limited"))
      (libsource (lib "Miscellaneous Devices") (part "Cap Semi"))
    )
    (comp (ref "C5_2")
      (value "470nF")
      (footprint "SMD_0603_CAPC1608X80N")
      (description "Capacitor (Semiconductor SIM Model)")
      (fields (field (name "PUBLISHER") "Altium Limited"))
      (libsource (lib "Miscellaneous Devices") (part "Cap Semi"))
    )
    (comp (ref "C5_3")
      (value "470nF")
      (footprint "SMD_0603_CAPC1608X80N")
      (description "Capacitor (Semiconductor SIM Model)")
      (fields (field (name "PUBLISHER") "Altium Limited"))
      (libsource (lib "Miscellaneous Devices") (part "Cap Semi"))
    )
    (comp (ref "C5_4")
      (value "470nF")
      (footprint "SMD_0603_CAPC1608X80N")
      (description "Capacitor (Semiconductor SIM Model)")
      (fields (field (name "PUBLISHER") "Altium Limited"))
      (libsource (lib "Miscellaneous Devices") (part "Cap Semi"))
    )
    (comp (ref "C5_5")
      (value "470nF")
      (footprint "SMD_0603_CAPC1608X80N")
      (description "Capacitor (Semiconductor SIM Model)")
      (fields (field (name "PUBLISHER") "Altium Limited"))
      (libsource (lib "Miscellaneous Devices") (part "Cap Semi"))
    )
    (comp (ref "C5_6")
      (value "470nF")
      (footprint "SMD_0603_CAPC1608X80N")
      (description "Capacitor (Semiconductor SIM Model)")
      (fields (field (name "PUBLISHER") "Altium Limited"))
      (libsource (lib "Miscellaneous Devices") (part "Cap Semi"))
    )
    (comp (ref "C5_7")
      (value "470nF")
      (footprint "SMD_0603_CAPC1608X80N")
      (description "Capacitor (Semiconductor SIM Model)")
      (fields (field (name "PUBLISHER") "Altium Limited"))
      (libsource (lib "Miscellaneous Devices") (part "Cap Semi"))
    )
    (comp (ref "C5_8")
      (value "470nF")
      (footprint "SMD_0603_CAPC1608X80N")
      (description "Capacitor (Semiconductor SIM Model)")
      (fields (field (name "PUBLISHER") "Altium Limited"))
      (libsource (lib "Miscellaneous Devices") (part "Cap Semi"))
    )
    (comp (ref "C5_9")
      (value "470nF")
      (footprint "SMD_0603_CAPC1608X80N")
      (description "Capacitor (Semiconductor SIM Model)")
      (fields (field (name "PUBLISHER") "Altium Limited"))
      (libsource (lib "Miscellaneous Devices") (part "Cap Semi"))
    )
    (comp (ref "C5_10")
      (value "470nF")
      (footprint "SMD_0603_CAPC1608X80N")
      (description "Capacitor (Semiconductor SIM Model)")
      (fields (field (name "PUBLISHER") "Altium Limited"))
      (libsource (lib "Miscellaneous Devices") (part "Cap Semi"))
    )
    (comp (ref "C5_11")
      (value "470nF")
      (footprint "SMD_0603_CAPC1608X80N")
      (description "Capacitor (Semiconductor SIM Model)")
      (fields (field (name "PUBLISHER") "Altium Limited"))
      (libsource (lib "Miscellaneous Devices") (part "Cap Semi"))
    )
    (comp (ref "C5_12")
      (value "470nF")
      (footprint "SMD_0603_CAPC1608X80N")
      (description "Capacitor (Semiconductor SIM Model)")
      (fields (field (name "PUBLISHER") "Altium Limited"))
      (libsource (lib "Miscellaneous Devices") (part "Cap Semi"))
    )
    (comp (ref "C5_13")
      (value "470nF")
      (footprint "SMD_0603_CAPC1608X80N")
      (description "Capacitor (Semiconductor SIM Model)")
      (fields (field (name "PUBLISHER") "Altium Limited"))
      (libsource (lib "Miscellaneous Devices") (part "Cap Semi"))
    )
    (comp (ref "C5_14")
      (value "470nF")
      (footprint "SMD_0603_CAPC1608X80N")
      (description "Capacitor (Semiconductor SIM Model)")
      (fields (field (name "PUBLISHER") "Altium Limited"))
      (libsource (lib "Miscellaneous Devices") (part "Cap Semi"))
    )
    (comp (ref "C5_15")
      (value "470nF")
      (footprint "SMD_0603_CAPC1608X80N")
      (description "Capacitor (Semiconductor SIM Model)")
      (fields (field (name "PUBLISHER") "Altium Limited"))
      (libsource (lib "Miscellaneous Devices") (part "Cap Semi"))
    )
    (comp (ref "C5_16")
      (value "470nF")
      (footprint "SMD_0603_CAPC1608X80N")
      (description "Capacitor (Semiconductor SIM Model)")
      (fields (field (name "PUBLISHER") "Altium Limited"))
      (libsource (lib "Miscellaneous Devices") (part "Cap Semi"))
    )
    (comp (ref "C6")
      (value "1nF")
      (footprint "SMD_0603_CAPC1608X80N")
      (description "Capacitor")
      (libsource (lib "*") (part "CAP"))
    )
    (comp (ref "C6P_1")
      (value "220uF")
      (footprint "SMD_1210_CAPC3225X279N")
      (description "CL32A227MQVNNNE 220UF 6.3V 20% X5R 1210")
      (fields (field (name "PUBLISHER") "Altium Limited"))
      (libsource (lib "Miscellaneous Devices") (part "Cap Semi"))
    )
    (comp (ref "C6P_2")
      (value "220uF")
      (footprint "SMD_1210_CAPC3225X279N")
      (description "CL32A227MQVNNNE 220UF 6.3V 20% X5R 1210")
      (fields (field (name "PUBLISHER") "Altium Limited"))
      (libsource (lib "Miscellaneous Devices") (part "Cap Semi"))
    )
    (comp (ref "C6P_3")
      (value "220uF")
      (footprint "SMD_1210_CAPC3225X279N")
      (description "CL32A227MQVNNNE 220UF 6.3V 20% X5R 1210")
      (fields (field (name "PUBLISHER") "Altium Limited"))
      (libsource (lib "Miscellaneous Devices") (part "Cap Semi"))
    )
    (comp (ref "C6_1")
      (value "470nF")
      (footprint "SMD_0603_CAPC1608X80N")
      (description "Capacitor (Semiconductor SIM Model)")
      (fields (field (name "PUBLISHER") "Altium Limited"))
      (libsource (lib "Miscellaneous Devices") (part "Cap Semi"))
    )
    (comp (ref "C6_2")
      (value "470nF")
      (footprint "SMD_0603_CAPC1608X80N")
      (description "Capacitor (Semiconductor SIM Model)")
      (fields (field (name "PUBLISHER") "Altium Limited"))
      (libsource (lib "Miscellaneous Devices") (part "Cap Semi"))
    )
    (comp (ref "C6_3")
      (value "470nF")
      (footprint "SMD_0603_CAPC1608X80N")
      (description "Capacitor (Semiconductor SIM Model)")
      (fields (field (name "PUBLISHER") "Altium Limited"))
      (libsource (lib "Miscellaneous Devices") (part "Cap Semi"))
    )
    (comp (ref "C6_4")
      (value "470nF")
      (footprint "SMD_0603_CAPC1608X80N")
      (description "Capacitor (Semiconductor SIM Model)")
      (fields (field (name "PUBLISHER") "Altium Limited"))
      (libsource (lib "Miscellaneous Devices") (part "Cap Semi"))
    )
    (comp (ref "C6_5")
      (value "470nF")
      (footprint "SMD_0603_CAPC1608X80N")
      (description "Capacitor (Semiconductor SIM Model)")
      (fields (field (name "PUBLISHER") "Altium Limited"))
      (libsource (lib "Miscellaneous Devices") (part "Cap Semi"))
    )
    (comp (ref "C6_6")
      (value "470nF")
      (footprint "SMD_0603_CAPC1608X80N")
      (description "Capacitor (Semiconductor SIM Model)")
      (fields (field (name "PUBLISHER") "Altium Limited"))
      (libsource (lib "Miscellaneous Devices") (part "Cap Semi"))
    )
    (comp (ref "C6_7")
      (value "470nF")
      (footprint "SMD_0603_CAPC1608X80N")
      (description "Capacitor (Semiconductor SIM Model)")
      (fields (field (name "PUBLISHER") "Altium Limited"))
      (libsource (lib "Miscellaneous Devices") (part "Cap Semi"))
    )
    (comp (ref "C6_8")
      (value "470nF")
      (footprint "SMD_0603_CAPC1608X80N")
      (description "Capacitor (Semiconductor SIM Model)")
      (fields (field (name "PUBLISHER") "Altium Limited"))
      (libsource (lib "Miscellaneous Devices") (part "Cap Semi"))
    )
    (comp (ref "C6_9")
      (value "470nF")
      (footprint "SMD_0603_CAPC1608X80N")
      (description "Capacitor (Semiconductor SIM Model)")
      (fields (field (name "PUBLISHER") "Altium Limited"))
      (libsource (lib "Miscellaneous Devices") (part "Cap Semi"))
    )
    (comp (ref "C6_10")
      (value "470nF")
      (footprint "SMD_0603_CAPC1608X80N")
      (description "Capacitor (Semiconductor SIM Model)")
      (fields (field (name "PUBLISHER") "Altium Limited"))
      (libsource (lib "Miscellaneous Devices") (part "Cap Semi"))
    )
    (comp (ref "C6_11")
      (value "470nF")
      (footprint "SMD_0603_CAPC1608X80N")
      (description "Capacitor (Semiconductor SIM Model)")
      (fields (field (name "PUBLISHER") "Altium Limited"))
      (libsource (lib "Miscellaneous Devices") (part "Cap Semi"))
    )
    (comp (ref "C6_12")
      (value "470nF")
      (footprint "SMD_0603_CAPC1608X80N")
      (description "Capacitor (Semiconductor SIM Model)")
      (fields (field (name "PUBLISHER") "Altium Limited"))
      (libsource (lib "Miscellaneous Devices") (part "Cap Semi"))
    )
    (comp (ref "C6_13")
      (value "470nF")
      (footprint "SMD_0603_CAPC1608X80N")
      (description "Capacitor (Semiconductor SIM Model)")
      (fields (field (name "PUBLISHER") "Altium Limited"))
      (libsource (lib "Miscellaneous Devices") (part "Cap Semi"))
    )
    (comp (ref "C6_14")
      (value "470nF")
      (footprint "SMD_0603_CAPC1608X80N")
      (description "Capacitor (Semiconductor SIM Model)")
      (fields (field (name "PUBLISHER") "Altium Limited"))
      (libsource (lib "Miscellaneous Devices") (part "Cap Semi"))
    )
    (comp (ref "C6_15")
      (value "470nF")
      (footprint "SMD_0603_CAPC1608X80N")
      (description "Capacitor (Semiconductor SIM Model)")
      (fields (field (name "PUBLISHER") "Altium Limited"))
      (libsource (lib "Miscellaneous Devices") (part "Cap Semi"))
    )
    (comp (ref "C6_16")
      (value "470nF")
      (footprint "SMD_0603_CAPC1608X80N")
      (description "Capacitor (Semiconductor SIM Model)")
      (fields (field (name "PUBLISHER") "Altium Limited"))
      (libsource (lib "Miscellaneous Devices") (part "Cap Semi"))
    )
    (comp (ref "C7")
      (value "100nF")
      (footprint "SMD_0603_CAPC1608X80N")
      (description "Capacitor")
      (libsource (lib "*") (part "CAP"))
    )
    (comp (ref "C7P_1")
      (value "220uF")
      (footprint "SMD_1210_CAPC3225X279N")
      (description "CL32A227MQVNNNE 220UF 6.3V 20% X5R 1210")
      (fields (field (name "PUBLISHER") "Altium Limited"))
      (libsource (lib "Miscellaneous Devices") (part "Cap Semi"))
    )
    (comp (ref "C7P_2")
      (value "220uF")
      (footprint "SMD_1210_CAPC3225X279N")
      (description "CL32A227MQVNNNE 220UF 6.3V 20% X5R 1210")
      (fields (field (name "PUBLISHER") "Altium Limited"))
      (libsource (lib "Miscellaneous Devices") (part "Cap Semi"))
    )
    (comp (ref "C7P_3")
      (value "220uF")
      (footprint "SMD_1210_CAPC3225X279N")
      (description "CL32A227MQVNNNE 220UF 6.3V 20% X5R 1210")
      (fields (field (name "PUBLISHER") "Altium Limited"))
      (libsource (lib "Miscellaneous Devices") (part "Cap Semi"))
    )
    (comp (ref "C7_1")
      (value "470nF")
      (footprint "SMD_0603_CAPC1608X80N")
      (description "Capacitor (Semiconductor SIM Model)")
      (fields (field (name "PUBLISHER") "Altium Limited"))
      (libsource (lib "Miscellaneous Devices") (part "Cap Semi"))
    )
    (comp (ref "C7_2")
      (value "470nF")
      (footprint "SMD_0603_CAPC1608X80N")
      (description "Capacitor (Semiconductor SIM Model)")
      (fields (field (name "PUBLISHER") "Altium Limited"))
      (libsource (lib "Miscellaneous Devices") (part "Cap Semi"))
    )
    (comp (ref "C7_3")
      (value "470nF")
      (footprint "SMD_0603_CAPC1608X80N")
      (description "Capacitor (Semiconductor SIM Model)")
      (fields (field (name "PUBLISHER") "Altium Limited"))
      (libsource (lib "Miscellaneous Devices") (part "Cap Semi"))
    )
    (comp (ref "C7_4")
      (value "470nF")
      (footprint "SMD_0603_CAPC1608X80N")
      (description "Capacitor (Semiconductor SIM Model)")
      (fields (field (name "PUBLISHER") "Altium Limited"))
      (libsource (lib "Miscellaneous Devices") (part "Cap Semi"))
    )
    (comp (ref "C7_5")
      (value "470nF")
      (footprint "SMD_0603_CAPC1608X80N")
      (description "Capacitor (Semiconductor SIM Model)")
      (fields (field (name "PUBLISHER") "Altium Limited"))
      (libsource (lib "Miscellaneous Devices") (part "Cap Semi"))
    )
    (comp (ref "C7_6")
      (value "470nF")
      (footprint "SMD_0603_CAPC1608X80N")
      (description "Capacitor (Semiconductor SIM Model)")
      (fields (field (name "PUBLISHER") "Altium Limited"))
      (libsource (lib "Miscellaneous Devices") (part "Cap Semi"))
    )
    (comp (ref "C7_7")
      (value "470nF")
      (footprint "SMD_0603_CAPC1608X80N")
      (description "Capacitor (Semiconductor SIM Model)")
      (fields (field (name "PUBLISHER") "Altium Limited"))
      (libsource (lib "Miscellaneous Devices") (part "Cap Semi"))
    )
    (comp (ref "C7_8")
      (value "470nF")
      (footprint "SMD_0603_CAPC1608X80N")
      (description "Capacitor (Semiconductor SIM Model)")
      (fields (field (name "PUBLISHER") "Altium Limited"))
      (libsource (lib "Miscellaneous Devices") (part "Cap Semi"))
    )
    (comp (ref "C7_9")
      (value "470nF")
      (footprint "SMD_0603_CAPC1608X80N")
      (description "Capacitor (Semiconductor SIM Model)")
      (fields (field (name "PUBLISHER") "Altium Limited"))
      (libsource (lib "Miscellaneous Devices") (part "Cap Semi"))
    )
    (comp (ref "C7_10")
      (value "470nF")
      (footprint "SMD_0603_CAPC1608X80N")
      (description "Capacitor (Semiconductor SIM Model)")
      (fields (field (name "PUBLISHER") "Altium Limited"))
      (libsource (lib "Miscellaneous Devices") (part "Cap Semi"))
    )
    (comp (ref "C7_11")
      (value "470nF")
      (footprint "SMD_0603_CAPC1608X80N")
      (description "Capacitor (Semiconductor SIM Model)")
      (fields (field (name "PUBLISHER") "Altium Limited"))
      (libsource (lib "Miscellaneous Devices") (part "Cap Semi"))
    )
    (comp (ref "C7_12")
      (value "470nF")
      (footprint "SMD_0603_CAPC1608X80N")
      (description "Capacitor (Semiconductor SIM Model)")
      (fields (field (name "PUBLISHER") "Altium Limited"))
      (libsource (lib "Miscellaneous Devices") (part "Cap Semi"))
    )
    (comp (ref "C7_13")
      (value "470nF")
      (footprint "SMD_0603_CAPC1608X80N")
      (description "Capacitor (Semiconductor SIM Model)")
      (fields (field (name "PUBLISHER") "Altium Limited"))
      (libsource (lib "Miscellaneous Devices") (part "Cap Semi"))
    )
    (comp (ref "C7_14")
      (value "470nF")
      (footprint "SMD_0603_CAPC1608X80N")
      (description "Capacitor (Semiconductor SIM Model)")
      (fields (field (name "PUBLISHER") "Altium Limited"))
      (libsource (lib "Miscellaneous Devices") (part "Cap Semi"))
    )
    (comp (ref "C7_15")
      (value "470nF")
      (footprint "SMD_0603_CAPC1608X80N")
      (description "Capacitor (Semiconductor SIM Model)")
      (fields (field (name "PUBLISHER") "Altium Limited"))
      (libsource (lib "Miscellaneous Devices") (part "Cap Semi"))
    )
    (comp (ref "C7_16")
      (value "470nF")
      (footprint "SMD_0603_CAPC1608X80N")
      (description "Capacitor (Semiconductor SIM Model)")
      (fields (field (name "PUBLISHER") "Altium Limited"))
      (libsource (lib "Miscellaneous Devices") (part "Cap Semi"))
    )
    (comp (ref "C8")
      (value "100nF")
      (footprint "SMD_0603_CAPC1608X80N")
      (description "Capacitor")
      (libsource (lib "*") (part "CAP"))
    )
    (comp (ref "C8P_1")
      (value "220uF")
      (footprint "SMD_1210_CAPC3225X279N")
      (description "CL32A227MQVNNNE 220UF 6.3V 20% X5R 1210")
      (fields (field (name "PUBLISHER") "Altium Limited"))
      (libsource (lib "Miscellaneous Devices") (part "Cap Semi"))
    )
    (comp (ref "C8P_2")
      (value "220uF")
      (footprint "SMD_1210_CAPC3225X279N")
      (description "CL32A227MQVNNNE 220UF 6.3V 20% X5R 1210")
      (fields (field (name "PUBLISHER") "Altium Limited"))
      (libsource (lib "Miscellaneous Devices") (part "Cap Semi"))
    )
    (comp (ref "C8P_3")
      (value "220uF")
      (footprint "SMD_1210_CAPC3225X279N")
      (description "CL32A227MQVNNNE 220UF 6.3V 20% X5R 1210")
      (fields (field (name "PUBLISHER") "Altium Limited"))
      (libsource (lib "Miscellaneous Devices") (part "Cap Semi"))
    )
    (comp (ref "C8_1")
      (value "470nF")
      (footprint "SMD_0603_CAPC1608X80N")
      (description "Capacitor (Semiconductor SIM Model)")
      (fields (field (name "PUBLISHER") "Altium Limited"))
      (libsource (lib "Miscellaneous Devices") (part "Cap Semi"))
    )
    (comp (ref "C8_2")
      (value "470nF")
      (footprint "SMD_0603_CAPC1608X80N")
      (description "Capacitor (Semiconductor SIM Model)")
      (fields (field (name "PUBLISHER") "Altium Limited"))
      (libsource (lib "Miscellaneous Devices") (part "Cap Semi"))
    )
    (comp (ref "C8_3")
      (value "470nF")
      (footprint "SMD_0603_CAPC1608X80N")
      (description "Capacitor (Semiconductor SIM Model)")
      (fields (field (name "PUBLISHER") "Altium Limited"))
      (libsource (lib "Miscellaneous Devices") (part "Cap Semi"))
    )
    (comp (ref "C8_4")
      (value "470nF")
      (footprint "SMD_0603_CAPC1608X80N")
      (description "Capacitor (Semiconductor SIM Model)")
      (fields (field (name "PUBLISHER") "Altium Limited"))
      (libsource (lib "Miscellaneous Devices") (part "Cap Semi"))
    )
    (comp (ref "C8_5")
      (value "470nF")
      (footprint "SMD_0603_CAPC1608X80N")
      (description "Capacitor (Semiconductor SIM Model)")
      (fields (field (name "PUBLISHER") "Altium Limited"))
      (libsource (lib "Miscellaneous Devices") (part "Cap Semi"))
    )
    (comp (ref "C8_6")
      (value "470nF")
      (footprint "SMD_0603_CAPC1608X80N")
      (description "Capacitor (Semiconductor SIM Model)")
      (fields (field (name "PUBLISHER") "Altium Limited"))
      (libsource (lib "Miscellaneous Devices") (part "Cap Semi"))
    )
    (comp (ref "C8_7")
      (value "470nF")
      (footprint "SMD_0603_CAPC1608X80N")
      (description "Capacitor (Semiconductor SIM Model)")
      (fields (field (name "PUBLISHER") "Altium Limited"))
      (libsource (lib "Miscellaneous Devices") (part "Cap Semi"))
    )
    (comp (ref "C8_8")
      (value "470nF")
      (footprint "SMD_0603_CAPC1608X80N")
      (description "Capacitor (Semiconductor SIM Model)")
      (fields (field (name "PUBLISHER") "Altium Limited"))
      (libsource (lib "Miscellaneous Devices") (part "Cap Semi"))
    )
    (comp (ref "C8_9")
      (value "470nF")
      (footprint "SMD_0603_CAPC1608X80N")
      (description "Capacitor (Semiconductor SIM Model)")
      (fields (field (name "PUBLISHER") "Altium Limited"))
      (libsource (lib "Miscellaneous Devices") (part "Cap Semi"))
    )
    (comp (ref "C8_10")
      (value "470nF")
      (footprint "SMD_0603_CAPC1608X80N")
      (description "Capacitor (Semiconductor SIM Model)")
      (fields (field (name "PUBLISHER") "Altium Limited"))
      (libsource (lib "Miscellaneous Devices") (part "Cap Semi"))
    )
    (comp (ref "C8_11")
      (value "470nF")
      (footprint "SMD_0603_CAPC1608X80N")
      (description "Capacitor (Semiconductor SIM Model)")
      (fields (field (name "PUBLISHER") "Altium Limited"))
      (libsource (lib "Miscellaneous Devices") (part "Cap Semi"))
    )
    (comp (ref "C8_12")
      (value "470nF")
      (footprint "SMD_0603_CAPC1608X80N")
      (description "Capacitor (Semiconductor SIM Model)")
      (fields (field (name "PUBLISHER") "Altium Limited"))
      (libsource (lib "Miscellaneous Devices") (part "Cap Semi"))
    )
    (comp (ref "C8_13")
      (value "470nF")
      (footprint "SMD_0603_CAPC1608X80N")
      (description "Capacitor (Semiconductor SIM Model)")
      (fields (field (name "PUBLISHER") "Altium Limited"))
      (libsource (lib "Miscellaneous Devices") (part "Cap Semi"))
    )
    (comp (ref "C8_14")
      (value "470nF")
      (footprint "SMD_0603_CAPC1608X80N")
      (description "Capacitor (Semiconductor SIM Model)")
      (fields (field (name "PUBLISHER") "Altium Limited"))
      (libsource (lib "Miscellaneous Devices") (part "Cap Semi"))
    )
    (comp (ref "C8_15")
      (value "470nF")
      (footprint "SMD_0603_CAPC1608X80N")
      (description "Capacitor (Semiconductor SIM Model)")
      (fields (field (name "PUBLISHER") "Altium Limited"))
      (libsource (lib "Miscellaneous Devices") (part "Cap Semi"))
    )
    (comp (ref "C8_16")
      (value "470nF")
      (footprint "SMD_0603_CAPC1608X80N")
      (description "Capacitor (Semiconductor SIM Model)")
      (fields (field (name "PUBLISHER") "Altium Limited"))
      (libsource (lib "Miscellaneous Devices") (part "Cap Semi"))
    )
    (comp (ref "C9")
      (value "100nF")
      (footprint "SMD_0603_CAPC1608X80N")
      (description "Capacitor")
      (libsource (lib "*") (part "CAP"))
    )
    (comp (ref "C9_1")
      (value "470nF")
      (footprint "SMD_0603_CAPC1608X80N")
      (description "Capacitor (Semiconductor SIM Model)")
      (fields (field (name "PUBLISHER") "Altium Limited"))
      (libsource (lib "Miscellaneous Devices") (part "Cap Semi"))
    )
    (comp (ref "C9_2")
      (value "470nF")
      (footprint "SMD_0603_CAPC1608X80N")
      (description "Capacitor (Semiconductor SIM Model)")
      (fields (field (name "PUBLISHER") "Altium Limited"))
      (libsource (lib "Miscellaneous Devices") (part "Cap Semi"))
    )
    (comp (ref "C9_3")
      (value "470nF")
      (footprint "SMD_0603_CAPC1608X80N")
      (description "Capacitor (Semiconductor SIM Model)")
      (fields (field (name "PUBLISHER") "Altium Limited"))
      (libsource (lib "Miscellaneous Devices") (part "Cap Semi"))
    )
    (comp (ref "C9_4")
      (value "470nF")
      (footprint "SMD_0603_CAPC1608X80N")
      (description "Capacitor (Semiconductor SIM Model)")
      (fields (field (name "PUBLISHER") "Altium Limited"))
      (libsource (lib "Miscellaneous Devices") (part "Cap Semi"))
    )
    (comp (ref "C9_5")
      (value "470nF")
      (footprint "SMD_0603_CAPC1608X80N")
      (description "Capacitor (Semiconductor SIM Model)")
      (fields (field (name "PUBLISHER") "Altium Limited"))
      (libsource (lib "Miscellaneous Devices") (part "Cap Semi"))
    )
    (comp (ref "C9_6")
      (value "470nF")
      (footprint "SMD_0603_CAPC1608X80N")
      (description "Capacitor (Semiconductor SIM Model)")
      (fields (field (name "PUBLISHER") "Altium Limited"))
      (libsource (lib "Miscellaneous Devices") (part "Cap Semi"))
    )
    (comp (ref "C9_7")
      (value "470nF")
      (footprint "SMD_0603_CAPC1608X80N")
      (description "Capacitor (Semiconductor SIM Model)")
      (fields (field (name "PUBLISHER") "Altium Limited"))
      (libsource (lib "Miscellaneous Devices") (part "Cap Semi"))
    )
    (comp (ref "C9_8")
      (value "470nF")
      (footprint "SMD_0603_CAPC1608X80N")
      (description "Capacitor (Semiconductor SIM Model)")
      (fields (field (name "PUBLISHER") "Altium Limited"))
      (libsource (lib "Miscellaneous Devices") (part "Cap Semi"))
    )
    (comp (ref "C9_9")
      (value "470nF")
      (footprint "SMD_0603_CAPC1608X80N")
      (description "Capacitor (Semiconductor SIM Model)")
      (fields (field (name "PUBLISHER") "Altium Limited"))
      (libsource (lib "Miscellaneous Devices") (part "Cap Semi"))
    )
    (comp (ref "C9_10")
      (value "470nF")
      (footprint "SMD_0603_CAPC1608X80N")
      (description "Capacitor (Semiconductor SIM Model)")
      (fields (field (name "PUBLISHER") "Altium Limited"))
      (libsource (lib "Miscellaneous Devices") (part "Cap Semi"))
    )
    (comp (ref "C9_11")
      (value "470nF")
      (footprint "SMD_0603_CAPC1608X80N")
      (description "Capacitor (Semiconductor SIM Model)")
      (fields (field (name "PUBLISHER") "Altium Limited"))
      (libsource (lib "Miscellaneous Devices") (part "Cap Semi"))
    )
    (comp (ref "C9_12")
      (value "470nF")
      (footprint "SMD_0603_CAPC1608X80N")
      (description "Capacitor (Semiconductor SIM Model)")
      (fields (field (name "PUBLISHER") "Altium Limited"))
      (libsource (lib "Miscellaneous Devices") (part "Cap Semi"))
    )
    (comp (ref "C9_13")
      (value "470nF")
      (footprint "SMD_0603_CAPC1608X80N")
      (description "Capacitor (Semiconductor SIM Model)")
      (fields (field (name "PUBLISHER") "Altium Limited"))
      (libsource (lib "Miscellaneous Devices") (part "Cap Semi"))
    )
    (comp (ref "C9_14")
      (value "470nF")
      (footprint "SMD_0603_CAPC1608X80N")
      (description "Capacitor (Semiconductor SIM Model)")
      (fields (field (name "PUBLISHER") "Altium Limited"))
      (libsource (lib "Miscellaneous Devices") (part "Cap Semi"))
    )
    (comp (ref "C9_15")
      (value "470nF")
      (footprint "SMD_0603_CAPC1608X80N")
      (description "Capacitor (Semiconductor SIM Model)")
      (fields (field (name "PUBLISHER") "Altium Limited"))
      (libsource (lib "Miscellaneous Devices") (part "Cap Semi"))
    )
    (comp (ref "C9_16")
      (value "470nF")
      (footprint "SMD_0603_CAPC1608X80N")
      (description "Capacitor (Semiconductor SIM Model)")
      (fields (field (name "PUBLISHER") "Altium Limited"))
      (libsource (lib "Miscellaneous Devices") (part "Cap Semi"))
    )
    (comp (ref "C10")
      (value "100nF")
      (footprint "SMD_0603_CAPC1608X80N")
      (description "Capacitor")
      (libsource (lib "*") (part "CAP"))
    )
    (comp (ref "C10_1")
      (value "470nF")
      (footprint "SMD_0603_CAPC1608X80N")
      (description "Capacitor (Semiconductor SIM Model)")
      (fields (field (name "PUBLISHER") "Altium Limited"))
      (libsource (lib "Miscellaneous Devices") (part "Cap Semi"))
    )
    (comp (ref "C10_2")
      (value "470nF")
      (footprint "SMD_0603_CAPC1608X80N")
      (description "Capacitor (Semiconductor SIM Model)")
      (fields (field (name "PUBLISHER") "Altium Limited"))
      (libsource (lib "Miscellaneous Devices") (part "Cap Semi"))
    )
    (comp (ref "C10_3")
      (value "470nF")
      (footprint "SMD_0603_CAPC1608X80N")
      (description "Capacitor (Semiconductor SIM Model)")
      (fields (field (name "PUBLISHER") "Altium Limited"))
      (libsource (lib "Miscellaneous Devices") (part "Cap Semi"))
    )
    (comp (ref "C10_4")
      (value "470nF")
      (footprint "SMD_0603_CAPC1608X80N")
      (description "Capacitor (Semiconductor SIM Model)")
      (fields (field (name "PUBLISHER") "Altium Limited"))
      (libsource (lib "Miscellaneous Devices") (part "Cap Semi"))
    )
    (comp (ref "C10_5")
      (value "470nF")
      (footprint "SMD_0603_CAPC1608X80N")
      (description "Capacitor (Semiconductor SIM Model)")
      (fields (field (name "PUBLISHER") "Altium Limited"))
      (libsource (lib "Miscellaneous Devices") (part "Cap Semi"))
    )
    (comp (ref "C10_6")
      (value "470nF")
      (footprint "SMD_0603_CAPC1608X80N")
      (description "Capacitor (Semiconductor SIM Model)")
      (fields (field (name "PUBLISHER") "Altium Limited"))
      (libsource (lib "Miscellaneous Devices") (part "Cap Semi"))
    )
    (comp (ref "C10_7")
      (value "470nF")
      (footprint "SMD_0603_CAPC1608X80N")
      (description "Capacitor (Semiconductor SIM Model)")
      (fields (field (name "PUBLISHER") "Altium Limited"))
      (libsource (lib "Miscellaneous Devices") (part "Cap Semi"))
    )
    (comp (ref "C10_8")
      (value "470nF")
      (footprint "SMD_0603_CAPC1608X80N")
      (description "Capacitor (Semiconductor SIM Model)")
      (fields (field (name "PUBLISHER") "Altium Limited"))
      (libsource (lib "Miscellaneous Devices") (part "Cap Semi"))
    )
    (comp (ref "C10_9")
      (value "470nF")
      (footprint "SMD_0603_CAPC1608X80N")
      (description "Capacitor (Semiconductor SIM Model)")
      (fields (field (name "PUBLISHER") "Altium Limited"))
      (libsource (lib "Miscellaneous Devices") (part "Cap Semi"))
    )
    (comp (ref "C10_10")
      (value "470nF")
      (footprint "SMD_0603_CAPC1608X80N")
      (description "Capacitor (Semiconductor SIM Model)")
      (fields (field (name "PUBLISHER") "Altium Limited"))
      (libsource (lib "Miscellaneous Devices") (part "Cap Semi"))
    )
    (comp (ref "C10_11")
      (value "470nF")
      (footprint "SMD_0603_CAPC1608X80N")
      (description "Capacitor (Semiconductor SIM Model)")
      (fields (field (name "PUBLISHER") "Altium Limited"))
      (libsource (lib "Miscellaneous Devices") (part "Cap Semi"))
    )
    (comp (ref "C10_12")
      (value "470nF")
      (footprint "SMD_0603_CAPC1608X80N")
      (description "Capacitor (Semiconductor SIM Model)")
      (fields (field (name "PUBLISHER") "Altium Limited"))
      (libsource (lib "Miscellaneous Devices") (part "Cap Semi"))
    )
    (comp (ref "C10_13")
      (value "470nF")
      (footprint "SMD_0603_CAPC1608X80N")
      (description "Capacitor (Semiconductor SIM Model)")
      (fields (field (name "PUBLISHER") "Altium Limited"))
      (libsource (lib "Miscellaneous Devices") (part "Cap Semi"))
    )
    (comp (ref "C10_14")
      (value "470nF")
      (footprint "SMD_0603_CAPC1608X80N")
      (description "Capacitor (Semiconductor SIM Model)")
      (fields (field (name "PUBLISHER") "Altium Limited"))
      (libsource (lib "Miscellaneous Devices") (part "Cap Semi"))
    )
    (comp (ref "C10_15")
      (value "470nF")
      (footprint "SMD_0603_CAPC1608X80N")
      (description "Capacitor (Semiconductor SIM Model)")
      (fields (field (name "PUBLISHER") "Altium Limited"))
      (libsource (lib "Miscellaneous Devices") (part "Cap Semi"))
    )
    (comp (ref "C10_16")
      (value "470nF")
      (footprint "SMD_0603_CAPC1608X80N")
      (description "Capacitor (Semiconductor SIM Model)")
      (fields (field (name "PUBLISHER") "Altium Limited"))
      (libsource (lib "Miscellaneous Devices") (part "Cap Semi"))
    )
    (comp (ref "C11")
      (value "100nF")
      (footprint "SMD_0603_CAPC1608X80N")
      (description "Capacitor")
      (libsource (lib "*") (part "CAP"))
    )
    (comp (ref "C11_1")
      (value "470nF")
      (footprint "SMD_0603_CAPC1608X80N")
      (description "Capacitor (Semiconductor SIM Model)")
      (fields (field (name "PUBLISHER") "Altium Limited"))
      (libsource (lib "Miscellaneous Devices") (part "Cap Semi"))
    )
    (comp (ref "C11_2")
      (value "470nF")
      (footprint "SMD_0603_CAPC1608X80N")
      (description "Capacitor (Semiconductor SIM Model)")
      (fields (field (name "PUBLISHER") "Altium Limited"))
      (libsource (lib "Miscellaneous Devices") (part "Cap Semi"))
    )
    (comp (ref "C11_3")
      (value "470nF")
      (footprint "SMD_0603_CAPC1608X80N")
      (description "Capacitor (Semiconductor SIM Model)")
      (fields (field (name "PUBLISHER") "Altium Limited"))
      (libsource (lib "Miscellaneous Devices") (part "Cap Semi"))
    )
    (comp (ref "C11_4")
      (value "470nF")
      (footprint "SMD_0603_CAPC1608X80N")
      (description "Capacitor (Semiconductor SIM Model)")
      (fields (field (name "PUBLISHER") "Altium Limited"))
      (libsource (lib "Miscellaneous Devices") (part "Cap Semi"))
    )
    (comp (ref "C11_5")
      (value "470nF")
      (footprint "SMD_0603_CAPC1608X80N")
      (description "Capacitor (Semiconductor SIM Model)")
      (fields (field (name "PUBLISHER") "Altium Limited"))
      (libsource (lib "Miscellaneous Devices") (part "Cap Semi"))
    )
    (comp (ref "C11_6")
      (value "470nF")
      (footprint "SMD_0603_CAPC1608X80N")
      (description "Capacitor (Semiconductor SIM Model)")
      (fields (field (name "PUBLISHER") "Altium Limited"))
      (libsource (lib "Miscellaneous Devices") (part "Cap Semi"))
    )
    (comp (ref "C11_7")
      (value "470nF")
      (footprint "SMD_0603_CAPC1608X80N")
      (description "Capacitor (Semiconductor SIM Model)")
      (fields (field (name "PUBLISHER") "Altium Limited"))
      (libsource (lib "Miscellaneous Devices") (part "Cap Semi"))
    )
    (comp (ref "C11_8")
      (value "470nF")
      (footprint "SMD_0603_CAPC1608X80N")
      (description "Capacitor (Semiconductor SIM Model)")
      (fields (field (name "PUBLISHER") "Altium Limited"))
      (libsource (lib "Miscellaneous Devices") (part "Cap Semi"))
    )
    (comp (ref "C11_9")
      (value "470nF")
      (footprint "SMD_0603_CAPC1608X80N")
      (description "Capacitor (Semiconductor SIM Model)")
      (fields (field (name "PUBLISHER") "Altium Limited"))
      (libsource (lib "Miscellaneous Devices") (part "Cap Semi"))
    )
    (comp (ref "C11_10")
      (value "470nF")
      (footprint "SMD_0603_CAPC1608X80N")
      (description "Capacitor (Semiconductor SIM Model)")
      (fields (field (name "PUBLISHER") "Altium Limited"))
      (libsource (lib "Miscellaneous Devices") (part "Cap Semi"))
    )
    (comp (ref "C11_11")
      (value "470nF")
      (footprint "SMD_0603_CAPC1608X80N")
      (description "Capacitor (Semiconductor SIM Model)")
      (fields (field (name "PUBLISHER") "Altium Limited"))
      (libsource (lib "Miscellaneous Devices") (part "Cap Semi"))
    )
    (comp (ref "C11_12")
      (value "470nF")
      (footprint "SMD_0603_CAPC1608X80N")
      (description "Capacitor (Semiconductor SIM Model)")
      (fields (field (name "PUBLISHER") "Altium Limited"))
      (libsource (lib "Miscellaneous Devices") (part "Cap Semi"))
    )
    (comp (ref "C11_13")
      (value "470nF")
      (footprint "SMD_0603_CAPC1608X80N")
      (description "Capacitor (Semiconductor SIM Model)")
      (fields (field (name "PUBLISHER") "Altium Limited"))
      (libsource (lib "Miscellaneous Devices") (part "Cap Semi"))
    )
    (comp (ref "C11_14")
      (value "470nF")
      (footprint "SMD_0603_CAPC1608X80N")
      (description "Capacitor (Semiconductor SIM Model)")
      (fields (field (name "PUBLISHER") "Altium Limited"))
      (libsource (lib "Miscellaneous Devices") (part "Cap Semi"))
    )
    (comp (ref "C11_15")
      (value "470nF")
      (footprint "SMD_0603_CAPC1608X80N")
      (description "Capacitor (Semiconductor SIM Model)")
      (fields (field (name "PUBLISHER") "Altium Limited"))
      (libsource (lib "Miscellaneous Devices") (part "Cap Semi"))
    )
    (comp (ref "C11_16")
      (value "470nF")
      (footprint "SMD_0603_CAPC1608X80N")
      (description "Capacitor (Semiconductor SIM Model)")
      (fields (field (name "PUBLISHER") "Altium Limited"))
      (libsource (lib "Miscellaneous Devices") (part "Cap Semi"))
    )
    (comp (ref "C12")
      (value "18pF")
      (footprint "SMD_0603_CAPC1608X80N")
      (description "Capacitor")
      (libsource (lib "*") (part "CAP"))
    )
    (comp (ref "C13")
      (value "18pF")
      (footprint "SMD_0603_CAPC1608X80N")
      (description "Capacitor")
      (libsource (lib "*") (part "CAP"))
    )
    (comp (ref "C14")
      (value "10uF/16V")
      (footprint "SMD_0805_CAPC2012X145N")
      (description "Capacitor")
      (libsource (lib "*") (part "CAP"))
    )
    (comp (ref "C15")
      (value "10uF/16V")
      (footprint "SMD_0805_CAPC2012X145N")
      (description "Capacitor")
      (libsource (lib "*") (part "CAP"))
    )
    (comp (ref "C16")
      (value "220uF")
      (footprint "SMD_1210_CAPC3225X279N")
      (description "CL32A227MQVNNNE 220UF 6.3V 20% X5R 1210")
      (fields (field (name "PUBLISHER") "Altium Limited"))
      (libsource (lib "Miscellaneous Devices") (part "Cap Semi"))
    )
    (comp (ref "C17")
      (value "22uF/6.3V")
      (footprint "SMD_0805_CAPC2012X145N")
      (description "Capacitor")
      (libsource (lib "*") (part "CAP"))
    )
    (comp (ref "C25")
      (value "22uF/6.3V")
      (footprint "SMD_0805_CAPC2012X145N")
      (description "Capacitor")
      (libsource (lib "*") (part "CAP"))
    )
    (comp (ref "C26")
      (value "22uF/6.3V")
      (footprint "SMD_0805_CAPC2012X145N")
      (description "Capacitor")
      (libsource (lib "*") (part "CAP"))
    )
    (comp (ref "C_220_1")
      (value "(OPT)220uF")
      (footprint "SMD_1210_CAPC3225X279N")
      (description "CL32A227MQVNNNE 220UF 6.3V 20% X5R 1210")
      (fields (field (name "PUBLISHER") "Altium Limited"))
      (libsource (lib "Miscellaneous Devices") (part "Cap Semi"))
    )
    (comp (ref "C_220_2")
      (value "(OPT)220uF")
      (footprint "SMD_1210_CAPC3225X279N")
      (description "CL32A227MQVNNNE 220UF 6.3V 20% X5R 1210")
      (fields (field (name "PUBLISHER") "Altium Limited"))
      (libsource (lib "Miscellaneous Devices") (part "Cap Semi"))
    )
    (comp (ref "C_220_3")
      (value "(OPT)220uF")
      (footprint "SMD_1210_CAPC3225X279N")
      (description "CL32A227MQVNNNE 220UF 6.3V 20% X5R 1210")
      (fields (field (name "PUBLISHER") "Altium Limited"))
      (libsource (lib "Miscellaneous Devices") (part "Cap Semi"))
    )
    (comp (ref "C_220_4")
      (value "(OPT)220uF")
      (footprint "SMD_1210_CAPC3225X279N")
      (description "CL32A227MQVNNNE 220UF 6.3V 20% X5R 1210")
      (fields (field (name "PUBLISHER") "Altium Limited"))
      (libsource (lib "Miscellaneous Devices") (part "Cap Semi"))
    )
    (comp (ref "C_220_5")
      (value "(OPT)220uF")
      (footprint "SMD_1210_CAPC3225X279N")
      (description "CL32A227MQVNNNE 220UF 6.3V 20% X5R 1210")
      (fields (field (name "PUBLISHER") "Altium Limited"))
      (libsource (lib "Miscellaneous Devices") (part "Cap Semi"))
    )
    (comp (ref "C_220_6")
      (value "(OPT)220uF")
      (footprint "SMD_1210_CAPC3225X279N")
      (description "CL32A227MQVNNNE 220UF 6.3V 20% X5R 1210")
      (fields (field (name "PUBLISHER") "Altium Limited"))
      (libsource (lib "Miscellaneous Devices") (part "Cap Semi"))
    )
    (comp (ref "C_220_7")
      (value "(OPT)220uF")
      (footprint "SMD_1210_CAPC3225X279N")
      (description "CL32A227MQVNNNE 220UF 6.3V 20% X5R 1210")
      (fields (field (name "PUBLISHER") "Altium Limited"))
      (libsource (lib "Miscellaneous Devices") (part "Cap Semi"))
    )
    (comp (ref "C_220_8")
      (value "(OPT)220uF")
      (footprint "SMD_1210_CAPC3225X279N")
      (description "CL32A227MQVNNNE 220UF 6.3V 20% X5R 1210")
      (fields (field (name "PUBLISHER") "Altium Limited"))
      (libsource (lib "Miscellaneous Devices") (part "Cap Semi"))
    )
    (comp (ref "C_220_9")
      (value "(OPT)220uF")
      (footprint "SMD_1210_CAPC3225X279N")
      (description "CL32A227MQVNNNE 220UF 6.3V 20% X5R 1210")
      (fields (field (name "PUBLISHER") "Altium Limited"))
      (libsource (lib "Miscellaneous Devices") (part "Cap Semi"))
    )
    (comp (ref "C_220_10")
      (value "(OPT)220uF")
      (footprint "SMD_1210_CAPC3225X279N")
      (description "CL32A227MQVNNNE 220UF 6.3V 20% X5R 1210")
      (fields (field (name "PUBLISHER") "Altium Limited"))
      (libsource (lib "Miscellaneous Devices") (part "Cap Semi"))
    )
    (comp (ref "C_220_11")
      (value "(OPT)220uF")
      (footprint "SMD_1210_CAPC3225X279N")
      (description "CL32A227MQVNNNE 220UF 6.3V 20% X5R 1210")
      (fields (field (name "PUBLISHER") "Altium Limited"))
      (libsource (lib "Miscellaneous Devices") (part "Cap Semi"))
    )
    (comp (ref "C_220_12")
      (value "(OPT)220uF")
      (footprint "SMD_1210_CAPC3225X279N")
      (description "CL32A227MQVNNNE 220UF 6.3V 20% X5R 1210")
      (fields (field (name "PUBLISHER") "Altium Limited"))
      (libsource (lib "Miscellaneous Devices") (part "Cap Semi"))
    )
    (comp (ref "C_220_13")
      (value "(OPT)220uF")
      (footprint "SMD_1210_CAPC3225X279N")
      (description "CL32A227MQVNNNE 220UF 6.3V 20% X5R 1210")
      (fields (field (name "PUBLISHER") "Altium Limited"))
      (libsource (lib "Miscellaneous Devices") (part "Cap Semi"))
    )
    (comp (ref "C_220_14")
      (value "(OPT)220uF")
      (footprint "SMD_1210_CAPC3225X279N")
      (description "CL32A227MQVNNNE 220UF 6.3V 20% X5R 1210")
      (fields (field (name "PUBLISHER") "Altium Limited"))
      (libsource (lib "Miscellaneous Devices") (part "Cap Semi"))
    )
    (comp (ref "C_220_15")
      (value "(OPT)220uF")
      (footprint "SMD_1210_CAPC3225X279N")
      (description "CL32A227MQVNNNE 220UF 6.3V 20% X5R 1210")
      (fields (field (name "PUBLISHER") "Altium Limited"))
      (libsource (lib "Miscellaneous Devices") (part "Cap Semi"))
    )
    (comp (ref "C_220_16")
      (value "(OPT)220uF")
      (footprint "SMD_1210_CAPC3225X279N")
      (description "CL32A227MQVNNNE 220UF 6.3V 20% X5R 1210")
      (fields (field (name "PUBLISHER") "Altium Limited"))
      (libsource (lib "Miscellaneous Devices") (part "Cap Semi"))
    )
    (comp (ref "C_220_17")
      (value "(OPT)220uF")
      (footprint "SMD_1210_CAPC3225X279N")
      (description "CL32A227MQVNNNE 220UF 6.3V 20% X5R 1210")
      (fields (field (name "PUBLISHER") "Altium Limited"))
      (libsource (lib "Miscellaneous Devices") (part "Cap Semi"))
    )
    (comp (ref "C_220_18")
      (value "(OPT)220uF")
      (footprint "SMD_1210_CAPC3225X279N")
      (description "CL32A227MQVNNNE 220UF 6.3V 20% X5R 1210")
      (fields (field (name "PUBLISHER") "Altium Limited"))
      (libsource (lib "Miscellaneous Devices") (part "Cap Semi"))
    )
    (comp (ref "C_220_19")
      (value "(OPT)220uF")
      (footprint "SMD_1210_CAPC3225X279N")
      (description "CL32A227MQVNNNE 220UF 6.3V 20% X5R 1210")
      (fields (field (name "PUBLISHER") "Altium Limited"))
      (libsource (lib "Miscellaneous Devices") (part "Cap Semi"))
    )
    (comp (ref "C_220_20")
      (value "(OPT)220uF")
      (footprint "SMD_1210_CAPC3225X279N")
      (description "CL32A227MQVNNNE 220UF 6.3V 20% X5R 1210")
      (fields (field (name "PUBLISHER") "Altium Limited"))
      (libsource (lib "Miscellaneous Devices") (part "Cap Semi"))
    )
    (comp (ref "C_220_21")
      (value "(OPT)220uF")
      (footprint "SMD_1210_CAPC3225X279N")
      (description "CL32A227MQVNNNE 220UF 6.3V 20% X5R 1210")
      (fields (field (name "PUBLISHER") "Altium Limited"))
      (libsource (lib "Miscellaneous Devices") (part "Cap Semi"))
    )
    (comp (ref "C_220_22")
      (value "(OPT)220uF")
      (footprint "SMD_1210_CAPC3225X279N")
      (description "CL32A227MQVNNNE 220UF 6.3V 20% X5R 1210")
      (fields (field (name "PUBLISHER") "Altium Limited"))
      (libsource (lib "Miscellaneous Devices") (part "Cap Semi"))
    )
    (comp (ref "C_220_23")
      (value "(OPT)220uF")
      (footprint "SMD_1210_CAPC3225X279N")
      (description "CL32A227MQVNNNE 220UF 6.3V 20% X5R 1210")
      (fields (field (name "PUBLISHER") "Altium Limited"))
      (libsource (lib "Miscellaneous Devices") (part "Cap Semi"))
    )
    (comp (ref "C_220_24")
      (value "(OPT)220uF")
      (footprint "SMD_1210_CAPC3225X279N")
      (description "CL32A227MQVNNNE 220UF 6.3V 20% X5R 1210")
      (fields (field (name "PUBLISHER") "Altium Limited"))
      (libsource (lib "Miscellaneous Devices") (part "Cap Semi"))
    )
    (comp (ref "C_220_25")
      (value "(OPT)220uF")
      (footprint "SMD_1210_CAPC3225X279N")
      (description "CL32A227MQVNNNE 220UF 6.3V 20% X5R 1210")
      (fields (field (name "PUBLISHER") "Altium Limited"))
      (libsource (lib "Miscellaneous Devices") (part "Cap Semi"))
    )
    (comp (ref "C_220_26")
      (value "(OPT)220uF")
      (footprint "SMD_1210_CAPC3225X279N")
      (description "CL32A227MQVNNNE 220UF 6.3V 20% X5R 1210")
      (fields (field (name "PUBLISHER") "Altium Limited"))
      (libsource (lib "Miscellaneous Devices") (part "Cap Semi"))
    )
    (comp (ref "C_220_27")
      (value "(OPT)220uF")
      (footprint "SMD_1210_CAPC3225X279N")
      (description "CL32A227MQVNNNE 220UF 6.3V 20% X5R 1210")
      (fields (field (name "PUBLISHER") "Altium Limited"))
      (libsource (lib "Miscellaneous Devices") (part "Cap Semi"))
    )
    (comp (ref "C_220_28")
      (value "(OPT)220uF")
      (footprint "SMD_1210_CAPC3225X279N")
      (description "CL32A227MQVNNNE 220UF 6.3V 20% X5R 1210")
      (fields (field (name "PUBLISHER") "Altium Limited"))
      (libsource (lib "Miscellaneous Devices") (part "Cap Semi"))
    )
    (comp (ref "C_220_29")
      (value "(OPT)220uF")
      (footprint "SMD_1210_CAPC3225X279N")
      (description "CL32A227MQVNNNE 220UF 6.3V 20% X5R 1210")
      (fields (field (name "PUBLISHER") "Altium Limited"))
      (libsource (lib "Miscellaneous Devices") (part "Cap Semi"))
    )
    (comp (ref "C_220_30")
      (value "(OPT)220uF")
      (footprint "SMD_1210_CAPC3225X279N")
      (description "CL32A227MQVNNNE 220UF 6.3V 20% X5R 1210")
      (fields (field (name "PUBLISHER") "Altium Limited"))
      (libsource (lib "Miscellaneous Devices") (part "Cap Semi"))
    )
    (comp (ref "C_220_31")
      (value "(OPT)220uF")
      (footprint "SMD_1210_CAPC3225X279N")
      (description "CL32A227MQVNNNE 220UF 6.3V 20% X5R 1210")
      (fields (field (name "PUBLISHER") "Altium Limited"))
      (libsource (lib "Miscellaneous Devices") (part "Cap Semi"))
    )
    (comp (ref "C_220_32")
      (value "(OPT)220uF")
      (footprint "SMD_1210_CAPC3225X279N")
      (description "CL32A227MQVNNNE 220UF 6.3V 20% X5R 1210")
      (fields (field (name "PUBLISHER") "Altium Limited"))
      (libsource (lib "Miscellaneous Devices") (part "Cap Semi"))
    )
    (comp (ref "C_220_33")
      (value "(OPT)220uF")
      (footprint "SMD_1210_CAPC3225X279N")
      (description "CL32A227MQVNNNE 220UF 6.3V 20% X5R 1210")
      (fields (field (name "PUBLISHER") "Altium Limited"))
      (libsource (lib "Miscellaneous Devices") (part "Cap Semi"))
    )
    (comp (ref "C_220_34")
      (value "(OPT)220uF")
      (footprint "SMD_1210_CAPC3225X279N")
      (description "CL32A227MQVNNNE 220UF 6.3V 20% X5R 1210")
      (fields (field (name "PUBLISHER") "Altium Limited"))
      (libsource (lib "Miscellaneous Devices") (part "Cap Semi"))
    )
    (comp (ref "C_220_35")
      (value "(OPT)220uF")
      (footprint "SMD_1210_CAPC3225X279N")
      (description "CL32A227MQVNNNE 220UF 6.3V 20% X5R 1210")
      (fields (field (name "PUBLISHER") "Altium Limited"))
      (libsource (lib "Miscellaneous Devices") (part "Cap Semi"))
    )
    (comp (ref "C_220_36")
      (value "(OPT)220uF")
      (footprint "SMD_1210_CAPC3225X279N")
      (description "CL32A227MQVNNNE 220UF 6.3V 20% X5R 1210")
      (fields (field (name "PUBLISHER") "Altium Limited"))
      (libsource (lib "Miscellaneous Devices") (part "Cap Semi"))
    )
    (comp (ref "C_220_37")
      (value "(OPT)220uF")
      (footprint "SMD_1210_CAPC3225X279N")
      (description "CL32A227MQVNNNE 220UF 6.3V 20% X5R 1210")
      (fields (field (name "PUBLISHER") "Altium Limited"))
      (libsource (lib "Miscellaneous Devices") (part "Cap Semi"))
    )
    (comp (ref "C_220_38")
      (value "(OPT)220uF")
      (footprint "SMD_1210_CAPC3225X279N")
      (description "CL32A227MQVNNNE 220UF 6.3V 20% X5R 1210")
      (fields (field (name "PUBLISHER") "Altium Limited"))
      (libsource (lib "Miscellaneous Devices") (part "Cap Semi"))
    )
    (comp (ref "C_220_39")
      (value "(OPT)220uF")
      (footprint "SMD_1210_CAPC3225X279N")
      (description "CL32A227MQVNNNE 220UF 6.3V 20% X5R 1210")
      (fields (field (name "PUBLISHER") "Altium Limited"))
      (libsource (lib "Miscellaneous Devices") (part "Cap Semi"))
    )
    (comp (ref "C_220_40")
      (value "(OPT)220uF")
      (footprint "SMD_1210_CAPC3225X279N")
      (description "CL32A227MQVNNNE 220UF 6.3V 20% X5R 1210")
      (fields (field (name "PUBLISHER") "Altium Limited"))
      (libsource (lib "Miscellaneous Devices") (part "Cap Semi"))
    )
    (comp (ref "C_220_41")
      (value "(OPT)220uF")
      (footprint "SMD_1210_CAPC3225X279N")
      (description "CL32A227MQVNNNE 220UF 6.3V 20% X5R 1210")
      (fields (field (name "PUBLISHER") "Altium Limited"))
      (libsource (lib "Miscellaneous Devices") (part "Cap Semi"))
    )
    (comp (ref "C_220_42")
      (value "(OPT)220uF")
      (footprint "SMD_1210_CAPC3225X279N")
      (description "CL32A227MQVNNNE 220UF 6.3V 20% X5R 1210")
      (fields (field (name "PUBLISHER") "Altium Limited"))
      (libsource (lib "Miscellaneous Devices") (part "Cap Semi"))
    )
    (comp (ref "C_220_43")
      (value "(OPT)220uF")
      (footprint "SMD_1210_CAPC3225X279N")
      (description "CL32A227MQVNNNE 220UF 6.3V 20% X5R 1210")
      (fields (field (name "PUBLISHER") "Altium Limited"))
      (libsource (lib "Miscellaneous Devices") (part "Cap Semi"))
    )
    (comp (ref "C_220_44")
      (value "(OPT)220uF")
      (footprint "SMD_1210_CAPC3225X279N")
      (description "CL32A227MQVNNNE 220UF 6.3V 20% X5R 1210")
      (fields (field (name "PUBLISHER") "Altium Limited"))
      (libsource (lib "Miscellaneous Devices") (part "Cap Semi"))
    )
    (comp (ref "C_220_45")
      (value "(OPT)220uF")
      (footprint "SMD_1210_CAPC3225X279N")
      (description "CL32A227MQVNNNE 220UF 6.3V 20% X5R 1210")
      (fields (field (name "PUBLISHER") "Altium Limited"))
      (libsource (lib "Miscellaneous Devices") (part "Cap Semi"))
    )
    (comp (ref "C_220_46")
      (value "(OPT)220uF")
      (footprint "SMD_1210_CAPC3225X279N")
      (description "CL32A227MQVNNNE 220UF 6.3V 20% X5R 1210")
      (fields (field (name "PUBLISHER") "Altium Limited"))
      (libsource (lib "Miscellaneous Devices") (part "Cap Semi"))
    )
    (comp (ref "C_220_47")
      (value "(OPT)220uF")
      (footprint "SMD_1210_CAPC3225X279N")
      (description "CL32A227MQVNNNE 220UF 6.3V 20% X5R 1210")
      (fields (field (name "PUBLISHER") "Altium Limited"))
      (libsource (lib "Miscellaneous Devices") (part "Cap Semi"))
    )
    (comp (ref "C_220_48")
      (value "(OPT)220uF")
      (footprint "SMD_1210_CAPC3225X279N")
      (description "CL32A227MQVNNNE 220UF 6.3V 20% X5R 1210")
      (fields (field (name "PUBLISHER") "Altium Limited"))
      (libsource (lib "Miscellaneous Devices") (part "Cap Semi"))
    )
    (comp (ref "C_220_49")
      (value "(OPT)220uF")
      (footprint "SMD_1210_CAPC3225X279N")
      (description "CL32A227MQVNNNE 220UF 6.3V 20% X5R 1210")
      (fields (field (name "PUBLISHER") "Altium Limited"))
      (libsource (lib "Miscellaneous Devices") (part "Cap Semi"))
    )
    (comp (ref "C_220_50")
      (value "(OPT)220uF")
      (footprint "SMD_1210_CAPC3225X279N")
      (description "CL32A227MQVNNNE 220UF 6.3V 20% X5R 1210")
      (fields (field (name "PUBLISHER") "Altium Limited"))
      (libsource (lib "Miscellaneous Devices") (part "Cap Semi"))
    )
    (comp (ref "C_220_51")
      (value "(OPT)220uF")
      (footprint "SMD_1210_CAPC3225X279N")
      (description "CL32A227MQVNNNE 220UF 6.3V 20% X5R 1210")
      (fields (field (name "PUBLISHER") "Altium Limited"))
      (libsource (lib "Miscellaneous Devices") (part "Cap Semi"))
    )
    (comp (ref "C_220_52")
      (value "(OPT)220uF")
      (footprint "SMD_1210_CAPC3225X279N")
      (description "CL32A227MQVNNNE 220UF 6.3V 20% X5R 1210")
      (fields (field (name "PUBLISHER") "Altium Limited"))
      (libsource (lib "Miscellaneous Devices") (part "Cap Semi"))
    )
    (comp (ref "C_220_53")
      (value "(OPT)220uF")
      (footprint "SMD_1210_CAPC3225X279N")
      (description "CL32A227MQVNNNE 220UF 6.3V 20% X5R 1210")
      (fields (field (name "PUBLISHER") "Altium Limited"))
      (libsource (lib "Miscellaneous Devices") (part "Cap Semi"))
    )
    (comp (ref "C_220_54")
      (value "(OPT)220uF")
      (footprint "SMD_1210_CAPC3225X279N")
      (description "CL32A227MQVNNNE 220UF 6.3V 20% X5R 1210")
      (fields (field (name "PUBLISHER") "Altium Limited"))
      (libsource (lib "Miscellaneous Devices") (part "Cap Semi"))
    )
    (comp (ref "C_220_55")
      (value "(OPT)220uF")
      (footprint "SMD_1210_CAPC3225X279N")
      (description "CL32A227MQVNNNE 220UF 6.3V 20% X5R 1210")
      (fields (field (name "PUBLISHER") "Altium Limited"))
      (libsource (lib "Miscellaneous Devices") (part "Cap Semi"))
    )
    (comp (ref "C_220_56")
      (value "(OPT)220uF")
      (footprint "SMD_1210_CAPC3225X279N")
      (description "CL32A227MQVNNNE 220UF 6.3V 20% X5R 1210")
      (fields (field (name "PUBLISHER") "Altium Limited"))
      (libsource (lib "Miscellaneous Devices") (part "Cap Semi"))
    )
    (comp (ref "C_220_57")
      (value "(OPT)220uF")
      (footprint "SMD_1210_CAPC3225X279N")
      (description "CL32A227MQVNNNE 220UF 6.3V 20% X5R 1210")
      (fields (field (name "PUBLISHER") "Altium Limited"))
      (libsource (lib "Miscellaneous Devices") (part "Cap Semi"))
    )
    (comp (ref "C_220_58")
      (value "(OPT)220uF")
      (footprint "SMD_1210_CAPC3225X279N")
      (description "CL32A227MQVNNNE 220UF 6.3V 20% X5R 1210")
      (fields (field (name "PUBLISHER") "Altium Limited"))
      (libsource (lib "Miscellaneous Devices") (part "Cap Semi"))
    )
    (comp (ref "C_220_59")
      (value "(OPT)220uF")
      (footprint "SMD_1210_CAPC3225X279N")
      (description "CL32A227MQVNNNE 220UF 6.3V 20% X5R 1210")
      (fields (field (name "PUBLISHER") "Altium Limited"))
      (libsource (lib "Miscellaneous Devices") (part "Cap Semi"))
    )
    (comp (ref "C_220_60")
      (value "(OPT)220uF")
      (footprint "SMD_1210_CAPC3225X279N")
      (description "CL32A227MQVNNNE 220UF 6.3V 20% X5R 1210")
      (fields (field (name "PUBLISHER") "Altium Limited"))
      (libsource (lib "Miscellaneous Devices") (part "Cap Semi"))
    )
    (comp (ref "C_220_61")
      (value "(OPT)220uF")
      (footprint "SMD_1210_CAPC3225X279N")
      (description "CL32A227MQVNNNE 220UF 6.3V 20% X5R 1210")
      (fields (field (name "PUBLISHER") "Altium Limited"))
      (libsource (lib "Miscellaneous Devices") (part "Cap Semi"))
    )
    (comp (ref "C_220_62")
      (value "(OPT)220uF")
      (footprint "SMD_1210_CAPC3225X279N")
      (description "CL32A227MQVNNNE 220UF 6.3V 20% X5R 1210")
      (fields (field (name "PUBLISHER") "Altium Limited"))
      (libsource (lib "Miscellaneous Devices") (part "Cap Semi"))
    )
    (comp (ref "C_220_63")
      (value "(OPT)220uF")
      (footprint "SMD_1210_CAPC3225X279N")
      (description "CL32A227MQVNNNE 220UF 6.3V 20% X5R 1210")
      (fields (field (name "PUBLISHER") "Altium Limited"))
      (libsource (lib "Miscellaneous Devices") (part "Cap Semi"))
    )
    (comp (ref "C_220_64")
      (value "(OPT)220uF")
      (footprint "SMD_1210_CAPC3225X279N")
      (description "CL32A227MQVNNNE 220UF 6.3V 20% X5R 1210")
      (fields (field (name "PUBLISHER") "Altium Limited"))
      (libsource (lib "Miscellaneous Devices") (part "Cap Semi"))
    )
    (comp (ref "C_220_65")
      (value "(OPT)220uF")
      (footprint "SMD_1210_CAPC3225X279N")
      (description "CL32A227MQVNNNE 220UF 6.3V 20% X5R 1210")
      (fields (field (name "PUBLISHER") "Altium Limited"))
      (libsource (lib "Miscellaneous Devices") (part "Cap Semi"))
    )
    (comp (ref "C_220_66")
      (value "(OPT)220uF")
      (footprint "SMD_1210_CAPC3225X279N")
      (description "CL32A227MQVNNNE 220UF 6.3V 20% X5R 1210")
      (fields (field (name "PUBLISHER") "Altium Limited"))
      (libsource (lib "Miscellaneous Devices") (part "Cap Semi"))
    )
    (comp (ref "C_220_67")
      (value "(OPT)220uF")
      (footprint "SMD_1210_CAPC3225X279N")
      (description "CL32A227MQVNNNE 220UF 6.3V 20% X5R 1210")
      (fields (field (name "PUBLISHER") "Altium Limited"))
      (libsource (lib "Miscellaneous Devices") (part "Cap Semi"))
    )
    (comp (ref "C_220_68")
      (value "(OPT)220uF")
      (footprint "SMD_1210_CAPC3225X279N")
      (description "CL32A227MQVNNNE 220UF 6.3V 20% X5R 1210")
      (fields (field (name "PUBLISHER") "Altium Limited"))
      (libsource (lib "Miscellaneous Devices") (part "Cap Semi"))
    )
    (comp (ref "C_220_69")
      (value "(OPT)220uF")
      (footprint "SMD_1210_CAPC3225X279N")
      (description "CL32A227MQVNNNE 220UF 6.3V 20% X5R 1210")
      (fields (field (name "PUBLISHER") "Altium Limited"))
      (libsource (lib "Miscellaneous Devices") (part "Cap Semi"))
    )
    (comp (ref "C_220_70")
      (value "(OPT)220uF")
      (footprint "SMD_1210_CAPC3225X279N")
      (description "CL32A227MQVNNNE 220UF 6.3V 20% X5R 1210")
      (fields (field (name "PUBLISHER") "Altium Limited"))
      (libsource (lib "Miscellaneous Devices") (part "Cap Semi"))
    )
    (comp (ref "C_220_71")
      (value "(OPT)220uF")
      (footprint "SMD_1210_CAPC3225X279N")
      (description "CL32A227MQVNNNE 220UF 6.3V 20% X5R 1210")
      (fields (field (name "PUBLISHER") "Altium Limited"))
      (libsource (lib "Miscellaneous Devices") (part "Cap Semi"))
    )
    (comp (ref "C_220_73")
      (value "(OPT)220uF")
      (footprint "SMD_1210_CAPC3225X279N")
      (description "CL32A227MQVNNNE 220UF 6.3V 20% X5R 1210")
      (fields (field (name "PUBLISHER") "Altium Limited"))
      (libsource (lib "Miscellaneous Devices") (part "Cap Semi"))
    )
    (comp (ref "D1")
      (value "Red SML210VT ROHM")
      (footprint "SMD_0805_LED2012X100N")
      (libsource (lib "EPIQ_DND_CIS_Library") (part "LED_2"))
    )
    (comp (ref "D1P_1")
      (value "BAT54C")
      (footprint "SMD_SOT23_SOT95P240X120-3N")
      (libsource (lib "EPIQ_DND_CIS_Library") (part "D_DUAL_A1A2CC3"))
    )
    (comp (ref "D1P_2")
      (value "BAT54C")
      (footprint "SMD_SOT23_SOT95P240X120-3N")
      (libsource (lib "EPIQ_DND_CIS_Library") (part "D_DUAL_A1A2CC3"))
    )
    (comp (ref "D1P_3")
      (value "BAT54C")
      (footprint "SMD_SOT23_SOT95P240X120-3N")
      (libsource (lib "EPIQ_DND_CIS_Library") (part "D_DUAL_A1A2CC3"))
    )
    (comp (ref "D2")
      (value "Green 	SML210MT ROHM")
      (footprint "SMD_0805_LED2012X100N")
      (libsource (lib "EPIQ_DND_CIS_Library") (part "LED_2"))
    )
    (comp (ref "D3")
      (value "Yellow SML210YT ROHM")
      (footprint "SMD_0805_LED2012X100N")
      (libsource (lib "EPIQ_DND_CIS_Library") (part "LED_2"))
    )
    (comp (ref "D4")
      (value "Orange 	SML210DT ROHM")
      (footprint "SMD_0805_LED2012X100N")
      (libsource (lib "EPIQ_DND_CIS_Library") (part "LED_2"))
    )
    (comp (ref "D5")
      (value "SMS05T1G")
      (footprint "SMD_SOT95P280X145-6N-W")
      (description "4 IO lines TVS")
      (libsource (lib "BitCoin") (part "D_TVS_QUAD_C1AA2AA5C3C4C6"))
    )
    (comp (ref "D7")
      (value "(OPT)SS14")
      (footprint "SMD_DO214AC_SMA")
      (libsource (lib "BitCoin") (part "D_STKY"))
    )
    (comp (ref "D8")
      (value "(OPT)SS14")
      (footprint "SMD_DO214AC_SMA")
      (libsource (lib "BitCoin") (part "D_STKY"))
    )
    (comp (ref "D9") (value "SS14") (footprint "SMD_DO214AC_SMA") (libsource (lib "BitCoin") (part "D_STKY")))
    (comp (ref "D10")
      (value "SMCJ12A")
      (footprint "SMD_DO214AC_SMC")
      (description "Еднопосочен трансил, 600W, UBRmin13.3V@1mA")
      (libsource (lib "BitCoin") (part "D_TVS_UNI"))
    )
    (comp (ref "J1")
      (value "(OPT) CON PROGRAM")
      (footprint "SIP5 PGM TOP")
      (description "Connector")
      (libsource (lib "Miscellaneous Devices") (part "CON5"))
    )
    (comp (ref "J2")
      (value "CU04SCM15B0-R0")
      (footprint "SMD_CON-CVILUX-CU04-SCM15B0")
      (libsource (lib "EPIQ_DND_CIS_Library") (part "CON_USB_MINI_1"))
    )
    (comp (ref "J3")
      (value "CON_3PINS")
      (footprint "PTH_CON_3.5mm_3PINs")
      (libsource (lib "EPIQ_DND_CIS_Library") (part "CON_3PINS"))
    )
    (comp (ref "J4")
      (value "WURTH 649 006 295 22")
      (footprint "PTH_CON_PCI-E")
      (description "4.20mm Male Dual Row Angled Header WR-MPC4")
      (libsource (lib "BitCoin") (part "CON_PCI-E"))
    )
    (comp (ref "L1P_1")
      (value "SLC1480-201MLD")
      (footprint "SMD_INDM12501250X800A - Coilcraft SLC1480")
      (libsource (lib "EPIQ_DND_CIS_Library") (part "L"))
    )
    (comp (ref "L1P_2")
      (value "SLC1480-201MLD")
      (footprint "SMD_INDM12501250X800A - Coilcraft SLC1480")
      (libsource (lib "EPIQ_DND_CIS_Library") (part "L"))
    )
    (comp (ref "L1P_3")
      (value "SLC1480-201MLD")
      (footprint "SMD_INDM12501250X800A - Coilcraft SLC1480")
      (libsource (lib "EPIQ_DND_CIS_Library") (part "L"))
    )
    (comp (ref "Q1")
      (value "BSS138")
      (footprint "SMD_SOT23_SOT95P240X120-3N")
      (libsource (lib "EPIQ_DND_CIS_Library") (part "BJT_NPN_B1E2C3"))
    )
    (comp (ref "Q1P_1")
      (value "AP1RA03GMT-3")
      (footprint "SMD_SON127P615X520X100-8N")
      (libsource (lib "EPIQ_DND_CIS_Library") (part "MOS_N_D1_S1S2S3G4D5D6D7D8"))
    )
    (comp (ref "Q1P_2")
      (value "AP1RA03GMT-3")
      (footprint "SMD_SON127P615X520X100-8N")
      (libsource (lib "EPIQ_DND_CIS_Library") (part "MOS_N_D1_S1S2S3G4D5D6D7D8"))
    )
    (comp (ref "Q1P_3")
      (value "AP1RA03GMT-3")
      (footprint "SMD_SON127P615X520X100-8N")
      (libsource (lib "EPIQ_DND_CIS_Library") (part "MOS_N_D1_S1S2S3G4D5D6D7D8"))
    )
    (comp (ref "Q2")
      (value "BSS138")
      (footprint "SMD_SOT23_SOT95P240X120-3N")
      (libsource (lib "EPIQ_DND_CIS_Library") (part "BJT_NPN_B1E2C3"))
    )
    (comp (ref "Q2P_1")
      (value "AP1RA03GMT-3")
      (footprint "SMD_SON127P615X520X100-8N")
      (libsource (lib "EPIQ_DND_CIS_Library") (part "MOS_N_D1_S1S2S3G4D5D6D7D8"))
    )
    (comp (ref "Q2P_2")
      (value "AP1RA03GMT-3")
      (footprint "SMD_SON127P615X520X100-8N")
      (libsource (lib "EPIQ_DND_CIS_Library") (part "MOS_N_D1_S1S2S3G4D5D6D7D8"))
    )
    (comp (ref "Q2P_3")
      (value "AP1RA03GMT-3")
      (footprint "SMD_SON127P615X520X100-8N")
      (libsource (lib "EPIQ_DND_CIS_Library") (part "MOS_N_D1_S1S2S3G4D5D6D7D8"))
    )
    (comp (ref "Q3P_1")
      (value "AP1RA03GMT-3")
      (footprint "SMD_SON127P615X520X100-8N")
      (libsource (lib "EPIQ_DND_CIS_Library") (part "MOS_N_D1_S1S2S3G4D5D6D7D8"))
    )
    (comp (ref "Q3P_2")
      (value "AP1RA03GMT-3")
      (footprint "SMD_SON127P615X520X100-8N")
      (libsource (lib "EPIQ_DND_CIS_Library") (part "MOS_N_D1_S1S2S3G4D5D6D7D8"))
    )
    (comp (ref "Q3P_3")
      (value "AP1RA03GMT-3")
      (footprint "SMD_SON127P615X520X100-8N")
      (libsource (lib "EPIQ_DND_CIS_Library") (part "MOS_N_D1_S1S2S3G4D5D6D7D8"))
    )
    (comp (ref "R1")
      (value "1k")
      (footprint "SMD_0603_RESC1608X55N")
      (description "Resistor")
      (fields (field (name "PUBLISHER") "Altium Limited"))
      (libsource (lib "Miscellaneous Devices") (part "Res3"))
    )
    (comp (ref "R1_1")
      (value "(OPT)1K")
      (footprint "SMD_0603_RESC1608X55N")
      (description "Resistor")
      (fields (field (name "PUBLISHER") "Altium Limited"))
      (libsource (lib "Miscellaneous Devices") (part "Res3"))
    )
    (comp (ref "R1_2")
      (value "(OPT)1K")
      (footprint "SMD_0603_RESC1608X55N")
      (description "Resistor")
      (fields (field (name "PUBLISHER") "Altium Limited"))
      (libsource (lib "Miscellaneous Devices") (part "Res3"))
    )
    (comp (ref "R1_3")
      (value "(OPT)1K")
      (footprint "SMD_0603_RESC1608X55N")
      (description "Resistor")
      (fields (field (name "PUBLISHER") "Altium Limited"))
      (libsource (lib "Miscellaneous Devices") (part "Res3"))
    )
    (comp (ref "R1_4")
      (value "(OPT)1K")
      (footprint "SMD_0603_RESC1608X55N")
      (description "Resistor")
      (fields (field (name "PUBLISHER") "Altium Limited"))
      (libsource (lib "Miscellaneous Devices") (part "Res3"))
    )
    (comp (ref "R1_5")
      (value "(OPT)1K")
      (footprint "SMD_0603_RESC1608X55N")
      (description "Resistor")
      (fields (field (name "PUBLISHER") "Altium Limited"))
      (libsource (lib "Miscellaneous Devices") (part "Res3"))
    )
    (comp (ref "R1_6")
      (value "(OPT)1K")
      (footprint "SMD_0603_RESC1608X55N")
      (description "Resistor")
      (fields (field (name "PUBLISHER") "Altium Limited"))
      (libsource (lib "Miscellaneous Devices") (part "Res3"))
    )
    (comp (ref "R1_7")
      (value "(OPT)1K")
      (footprint "SMD_0603_RESC1608X55N")
      (description "Resistor")
      (fields (field (name "PUBLISHER") "Altium Limited"))
      (libsource (lib "Miscellaneous Devices") (part "Res3"))
    )
    (comp (ref "R1_8")
      (value "(OPT)1K")
      (footprint "SMD_0603_RESC1608X55N")
      (description "Resistor")
      (fields (field (name "PUBLISHER") "Altium Limited"))
      (libsource (lib "Miscellaneous Devices") (part "Res3"))
    )
    (comp (ref "R1_9")
      (value "(OPT)1K")
      (footprint "SMD_0603_RESC1608X55N")
      (description "Resistor")
      (fields (field (name "PUBLISHER") "Altium Limited"))
      (libsource (lib "Miscellaneous Devices") (part "Res3"))
    )
    (comp (ref "R1_10")
      (value "(OPT)1K")
      (footprint "SMD_0603_RESC1608X55N")
      (description "Resistor")
      (fields (field (name "PUBLISHER") "Altium Limited"))
      (libsource (lib "Miscellaneous Devices") (part "Res3"))
    )
    (comp (ref "R1_11")
      (value "(OPT)1K")
      (footprint "SMD_0603_RESC1608X55N")
      (description "Resistor")
      (fields (field (name "PUBLISHER") "Altium Limited"))
      (libsource (lib "Miscellaneous Devices") (part "Res3"))
    )
    (comp (ref "R1_12")
      (value "(OPT)1K")
      (footprint "SMD_0603_RESC1608X55N")
      (description "Resistor")
      (fields (field (name "PUBLISHER") "Altium Limited"))
      (libsource (lib "Miscellaneous Devices") (part "Res3"))
    )
    (comp (ref "R1_13")
      (value "(OPT)1K")
      (footprint "SMD_0603_RESC1608X55N")
      (description "Resistor")
      (fields (field (name "PUBLISHER") "Altium Limited"))
      (libsource (lib "Miscellaneous Devices") (part "Res3"))
    )
    (comp (ref "R1_14")
      (value "(OPT)1K")
      (footprint "SMD_0603_RESC1608X55N")
      (description "Resistor")
      (fields (field (name "PUBLISHER") "Altium Limited"))
      (libsource (lib "Miscellaneous Devices") (part "Res3"))
    )
    (comp (ref "R1_15")
      (value "(OPT)1K")
      (footprint "SMD_0603_RESC1608X55N")
      (description "Resistor")
      (fields (field (name "PUBLISHER") "Altium Limited"))
      (libsource (lib "Miscellaneous Devices") (part "Res3"))
    )
    (comp (ref "R1_16")
      (value "(OPT)1K")
      (footprint "SMD_0603_RESC1608X55N")
      (description "Resistor")
      (fields (field (name "PUBLISHER") "Altium Limited"))
      (libsource (lib "Miscellaneous Devices") (part "Res3"))
    )
    (comp (ref "R2")
      (value "1k")
      (footprint "SMD_0603_RESC1608X55N")
      (description "Resistor")
      (fields (field (name "PUBLISHER") "Altium Limited"))
      (libsource (lib "Miscellaneous Devices") (part "Res3"))
    )
    (comp (ref "R3")
      (value "1k")
      (footprint "SMD_0603_RESC1608X55N")
      (description "Resistor")
      (fields (field (name "PUBLISHER") "Altium Limited"))
      (libsource (lib "Miscellaneous Devices") (part "Res3"))
    )
    (comp (ref "R4")
      (value "1k")
      (footprint "SMD_0603_RESC1608X55N")
      (description "Resistor")
      (fields (field (name "PUBLISHER") "Altium Limited"))
      (libsource (lib "Miscellaneous Devices") (part "Res3"))
    )
    (comp (ref "R5")
      (value "1k")
      (footprint "SMD_0603_RESC1608X55N")
      (description "Resistor")
      (fields (field (name "PUBLISHER") "Altium Limited"))
      (libsource (lib "Miscellaneous Devices") (part "Res3"))
    )
    (comp (ref "R6")
      (value "1k")
      (footprint "SMD_0603_RESC1608X55N")
      (description "Resistor")
      (fields (field (name "PUBLISHER") "Altium Limited"))
      (libsource (lib "Miscellaneous Devices") (part "Res3"))
    )
    (comp (ref "R7")
      (value "1k")
      (footprint "SMD_0603_RESC1608X55N")
      (description "Resistor")
      (fields (field (name "PUBLISHER") "Altium Limited"))
      (libsource (lib "Miscellaneous Devices") (part "Res3"))
    )
    (comp (ref "R8")
      (value "47")
      (footprint "SMD_0603_RESC1608X55N")
      (description "Resistor")
      (fields (field (name "PUBLISHER") "Altium Limited"))
      (libsource (lib "Miscellaneous Devices") (part "Res3"))
    )
    (comp (ref "R9")
      (value "10k")
      (footprint "SMD_0603_RESC1608X55N")
      (description "Resistor")
      (fields (field (name "PUBLISHER") "Altium Limited"))
      (libsource (lib "Miscellaneous Devices") (part "Res3"))
    )
    (comp (ref "R10")
      (value "10k")
      (footprint "SMD_0603_RESC1608X55N")
      (description "Resistor")
      (fields (field (name "PUBLISHER") "Altium Limited"))
      (libsource (lib "Miscellaneous Devices") (part "Res3"))
    )
    (comp (ref "R11")
      (value "10k")
      (footprint "SMD_0603_RESC1608X55N")
      (description "Resistor")
      (fields (field (name "PUBLISHER") "Altium Limited"))
      (libsource (lib "Miscellaneous Devices") (part "Res3"))
    )
    (comp (ref "R12")
      (value "10k")
      (footprint "SMD_0603_RESC1608X55N")
      (description "Resistor")
      (fields (field (name "PUBLISHER") "Altium Limited"))
      (libsource (lib "Miscellaneous Devices") (part "Res3"))
    )
    (comp (ref "R13")
      (value "1k")
      (footprint "SMD_0603_RESC1608X55N")
      (description "Resistor")
      (fields (field (name "PUBLISHER") "Altium Limited"))
      (libsource (lib "Miscellaneous Devices") (part "Res3"))
    )
    (comp (ref "R14")
      (value "47")
      (footprint "SMD_0603_RESC1608X55N")
      (description "Resistor")
      (fields (field (name "PUBLISHER") "Altium Limited"))
      (libsource (lib "Miscellaneous Devices") (part "Res3"))
    )
    (comp (ref "R15")
      (value "10k")
      (footprint "SMD_0603_RESC1608X55N")
      (description "Resistor")
      (fields (field (name "PUBLISHER") "Altium Limited"))
      (libsource (lib "Miscellaneous Devices") (part "Res3"))
    )
    (comp (ref "R16")
      (value "2.4k")
      (footprint "SMD_0603_RESC1608X55N")
      (description "Resistor")
      (fields (field (name "PUBLISHER") "Altium Limited"))
      (libsource (lib "Miscellaneous Devices") (part "Res3"))
    )
    (comp (ref "R17")
      (value "0")
      (footprint "SMD_0603_RESC1608X55N")
      (description "Resistor")
      (fields (field (name "PUBLISHER") "Altium Limited"))
      (libsource (lib "Miscellaneous Devices") (part "Res3"))
    )
    (comp (ref "R18")
      (value "10k")
      (footprint "SMD_0603_RESC1608X55N")
      (description "Resistor")
      (fields (field (name "PUBLISHER") "Altium Limited"))
      (libsource (lib "Miscellaneous Devices") (part "Res3"))
    )
    (comp (ref "R19")
      (value "(OPT)10k")
      (footprint "SMD_0603_RESC1608X55N")
      (description "Resistor")
      (fields (field (name "PUBLISHER") "Altium Limited"))
      (libsource (lib "Miscellaneous Devices") (part "Res3"))
    )
    (comp (ref "R20")
      (value "10k")
      (footprint "SMD_0603_RESC1608X55N")
      (description "Resistor")
      (fields (field (name "PUBLISHER") "Altium Limited"))
      (libsource (lib "Miscellaneous Devices") (part "Res3"))
    )
    (comp (ref "R21")
      (value "10k")
      (footprint "SMD_0603_RESC1608X55N")
      (description "Resistor")
      (fields (field (name "PUBLISHER") "Altium Limited"))
      (libsource (lib "Miscellaneous Devices") (part "Res3"))
    )
    (comp (ref "R22")
      (value "10k")
      (footprint "SMD_0603_RESC1608X55N")
      (description "Resistor")
      (fields (field (name "PUBLISHER") "Altium Limited"))
      (libsource (lib "Miscellaneous Devices") (part "Res3"))
    )
    (comp (ref "R23")
      (value "10k")
      (footprint "SMD_0603_RESC1608X55N")
      (description "Resistor")
      (fields (field (name "PUBLISHER") "Altium Limited"))
      (libsource (lib "Miscellaneous Devices") (part "Res3"))
    )
    (comp (ref "R24")
      (value "470")
      (footprint "SMD_0603_RESC1608X55N")
      (description "Resistor")
      (fields (field (name "PUBLISHER") "Altium Limited"))
      (libsource (lib "Miscellaneous Devices") (part "Res3"))
    )
    (comp (ref "R25")
      (value "0")
      (footprint "SMD_0603_RESC1608X55N")
      (description "Resistor")
      (fields (field (name "PUBLISHER") "Altium Limited"))
      (libsource (lib "Miscellaneous Devices") (part "Res3"))
    )
    (comp (ref "R26")
      (value "2")
      (footprint "SMD_1206_RESC3216X180N")
      (description "Resistor")
      (fields (field (name "PUBLISHER") "Altium Limited"))
      (libsource (lib "Miscellaneous Devices") (part "Res3"))
    )
    (comp (ref "R27")
      (value "0")
      (footprint "SMD_0603_RESC1608X55N")
      (description "Resistor")
      (fields (field (name "PUBLISHER") "Altium Limited"))
      (libsource (lib "Miscellaneous Devices") (part "Res3"))
    )
    (comp (ref "R28")
      (value "100")
      (footprint "SMD_1206_RESC3216X180N")
      (description "Resistor")
      (fields (field (name "PUBLISHER") "Altium Limited"))
      (libsource (lib "Miscellaneous Devices") (part "Res3"))
    )
    (comp (ref "R29")
      (value "47")
      (footprint "SMD_0603_RESC1608X55N")
      (description "Resistor")
      (fields (field (name "PUBLISHER") "Altium Limited"))
      (libsource (lib "Miscellaneous Devices") (part "Res3"))
    )
    (comp (ref "R30")
      (value "(OPT)0")
      (footprint "SMD_0603_RESC1608X55N")
      (description "Resistor")
      (fields (field (name "PUBLISHER") "Altium Limited"))
      (libsource (lib "Miscellaneous Devices") (part "Res3"))
    )
    (comp (ref "R31")
      (value "47")
      (footprint "SMD_0603_RESC1608X55N")
      (description "Resistor")
      (fields (field (name "PUBLISHER") "Altium Limited"))
      (libsource (lib "Miscellaneous Devices") (part "Res3"))
    )
    (comp (ref "R32")
      (value "470")
      (footprint "SMD_0603_RESC1608X55N")
      (description "Resistor")
      (fields (field (name "PUBLISHER") "Altium Limited"))
      (libsource (lib "Miscellaneous Devices") (part "Res3"))
    )
    (comp (ref "U1")
      (value "dsPIC33EP256MU806")
      (footprint "SMD_QFP50P1200X1200X120-64N")
      (libsource (lib "MCU") (part "dsPIC33EP256MU806"))
    )
    (comp (ref "U1P_1")
      (value "LTC 4449")
      (footprint "SMD_DFN16166SON50P161X161X60-9N - LTC4449")
      (description "Mosfet 12V Dual Bootstrapped PWM Sync Buck Optimised")
      (libsource (lib "Devices") (part "DRVFET_LTC4442"))
    )
    (comp (ref "U1P_2")
      (value "LTC 4449")
      (footprint "SMD_DFN16166SON50P161X161X60-9N - LTC4449")
      (description "Mosfet 12V Dual Bootstrapped PWM Sync Buck Optimised")
      (libsource (lib "Devices") (part "DRVFET_LTC4442"))
    )
    (comp (ref "U1P_3")
      (value "LTC 4449")
      (footprint "SMD_DFN16166SON50P161X161X60-9N - LTC4449")
      (description "Mosfet 12V Dual Bootstrapped PWM Sync Buck Optimised")
      (libsource (lib "Devices") (part "DRVFET_LTC4442"))
    )
    (comp (ref "U1_1")
      (value "A3255Q48")
      (footprint "SMD_QFN50P700X700X90-49N")
      (description "Avalon2 SHA256")
      (libsource (lib "DevicesA10") (part "A3255Q48"))
    )
    (comp (ref "U1_2")
      (value "A3255Q48")
      (footprint "SMD_QFN50P700X700X90-49N")
      (description "Avalon2 SHA256")
      (libsource (lib "DevicesA10") (part "A3255Q48"))
    )
    (comp (ref "U1_3")
      (value "A3255Q48")
      (footprint "SMD_QFN50P700X700X90-49N")
      (description "Avalon2 SHA256")
      (libsource (lib "DevicesA10") (part "A3255Q48"))
    )
    (comp (ref "U1_4")
      (value "A3255Q48")
      (footprint "SMD_QFN50P700X700X90-49N")
      (description "Avalon2 SHA256")
      (libsource (lib "DevicesA10") (part "A3255Q48"))
    )
    (comp (ref "U1_5")
      (value "A3255Q48")
      (footprint "SMD_QFN50P700X700X90-49N")
      (description "Avalon2 SHA256")
      (libsource (lib "DevicesA10") (part "A3255Q48"))
    )
    (comp (ref "U1_6")
      (value "A3255Q48")
      (footprint "SMD_QFN50P700X700X90-49N")
      (description "Avalon2 SHA256")
      (libsource (lib "DevicesA10") (part "A3255Q48"))
    )
    (comp (ref "U1_7")
      (value "A3255Q48")
      (footprint "SMD_QFN50P700X700X90-49N")
      (description "Avalon2 SHA256")
      (libsource (lib "DevicesA10") (part "A3255Q48"))
    )
    (comp (ref "U1_8")
      (value "A3255Q48")
      (footprint "SMD_QFN50P700X700X90-49N")
      (description "Avalon2 SHA256")
      (libsource (lib "DevicesA10") (part "A3255Q48"))
    )
    (comp (ref "U1_9")
      (value "A3255Q48")
      (footprint "SMD_QFN50P700X700X90-49N")
      (description "Avalon2 SHA256")
      (libsource (lib "DevicesA10") (part "A3255Q48"))
    )
    (comp (ref "U1_10")
      (value "A3255Q48")
      (footprint "SMD_QFN50P700X700X90-49N")
      (description "Avalon2 SHA256")
      (libsource (lib "DevicesA10") (part "A3255Q48"))
    )
    (comp (ref "U1_11")
      (value "A3255Q48")
      (footprint "SMD_QFN50P700X700X90-49N")
      (description "Avalon2 SHA256")
      (libsource (lib "DevicesA10") (part "A3255Q48"))
    )
    (comp (ref "U1_12")
      (value "A3255Q48")
      (footprint "SMD_QFN50P700X700X90-49N")
      (description "Avalon2 SHA256")
      (libsource (lib "DevicesA10") (part "A3255Q48"))
    )
    (comp (ref "U1_13")
      (value "A3255Q48")
      (footprint "SMD_QFN50P700X700X90-49N")
      (description "Avalon2 SHA256")
      (libsource (lib "DevicesA10") (part "A3255Q48"))
    )
    (comp (ref "U1_14")
      (value "A3255Q48")
      (footprint "SMD_QFN50P700X700X90-49N")
      (description "Avalon2 SHA256")
      (libsource (lib "DevicesA10") (part "A3255Q48"))
    )
    (comp (ref "U1_15")
      (value "A3255Q48")
      (footprint "SMD_QFN50P700X700X90-49N")
      (description "Avalon2 SHA256")
      (libsource (lib "DevicesA10") (part "A3255Q48"))
    )
    (comp (ref "U1_16")
      (value "A3255Q48")
      (footprint "SMD_QFN50P700X700X90-49N")
      (description "Avalon2 SHA256")
      (libsource (lib "DevicesA10") (part "A3255Q48"))
    )
    (comp (ref "U2")
      (value "(OPT) LM7805")
      (footprint "SMD_SOIC127P602X173-8N")
      (libsource (lib "EPIQ_DND_CIS_Library") (part "IC_LM2931AD-5.0R2G_SO-8"))
    )
    (comp (ref "U3")
      (value "(OPT)BU33TD3WG-TR")
      (footprint "SMD_SOT26_SOT95P285X140-5N - DLV")
      (libsource (lib "Miscellaneous Devices") (part "VOLTREG LDO"))
    )
    (comp (ref "U4")
      (value "(OPT) L7805CD2T-TR")
      (footprint "SMD_TO254P1524X483-3_4N_D2PAK")
      (libsource (lib "EPIQ_DND_CIS_Library") (part "IC_Vout1GND2Vin3"))
    )
    (comp (ref "U5")
      (value "L78M05CDT-TR")
      (footprint "SMD_TO229P991X239-4AN_DPAK")
      (libsource (lib "EPIQ_DND_CIS_Library") (part "IC_Vout1GND2Vin3"))
    )
    (comp (ref "U6")
      (value "BD18KA5WF")
      (footprint "SMD_SOIC127P602X173-8N")
      (libsource (lib "EPIQ_DND_CIS_Library") (part "IC_LM2931AD-5.0R2G_SO-8"))
    )
    (comp (ref "U7")
      (value "BD33KA5WF")
      (footprint "SMD_SOIC127P602X173-8N")
      (libsource (lib "EPIQ_DND_CIS_Library") (part "IC_LM2931AD-5.0R2G_SO-8"))
    )
    (comp (ref "Y1")
      (value "Q4.000 MHz HC-49SM SMD")
      (footprint "SMD_HC49_XTAL1140X480X420N")
      (description "Crystal")
      (libsource (lib "*") (part "CRYSTAL"))
    )
  )
  (nets
    (net (code "1") (name "/0.8V") (class "Default")
      (node (ref "C11_1") (pin "1") (pinfunction "1_1") (pintype "passive"))
      (node (ref "C11_10") (pin "1") (pinfunction "1_1") (pintype "passive"))
      (node (ref "C11_11") (pin "1") (pinfunction "1_1") (pintype "passive"))
      (node (ref "C11_12") (pin "1") (pinfunction "1_1") (pintype "passive"))
      (node (ref "C11_13") (pin "1") (pinfunction "1_1") (pintype "passive"))
      (node (ref "C11_14") (pin "1") (pinfunction "1_1") (pintype "passive"))
      (node (ref "C11_15") (pin "1") (pinfunction "1_1") (pintype "passive"))
      (node (ref "C11_16") (pin "1") (pinfunction "1_1") (pintype "passive"))
      (node (ref "C11_2") (pin "1") (pinfunction "1_1") (pintype "passive"))
      (node (ref "C11_3") (pin "1") (pinfunction "1_1") (pintype "passive"))
      (node (ref "C11_4") (pin "1") (pinfunction "1_1") (pintype "passive"))
      (node (ref "C11_5") (pin "1") (pinfunction "1_1") (pintype "passive"))
      (node (ref "C11_6") (pin "1") (pinfunction "1_1") (pintype "passive"))
      (node (ref "C11_7") (pin "1") (pinfunction "1_1") (pintype "passive"))
      (node (ref "C11_8") (pin "1") (pinfunction "1_1") (pintype "passive"))
      (node (ref "C11_9") (pin "1") (pinfunction "1_1") (pintype "passive"))
      (node (ref "C1_1") (pin "1") (pinfunction "1_1") (pintype "passive"))
      (node (ref "C1_10") (pin "1") (pinfunction "1_1") (pintype "passive"))
      (node (ref "C1_11") (pin "1") (pinfunction "1_1") (pintype "passive"))
      (node (ref "C1_12") (pin "1") (pinfunction "1_1") (pintype "passive"))
      (node (ref "C1_13") (pin "1") (pinfunction "1_1") (pintype "passive"))
      (node (ref "C1_14") (pin "1") (pinfunction "1_1") (pintype "passive"))
      (node (ref "C1_15") (pin "1") (pinfunction "1_1") (pintype "passive"))
      (node (ref "C1_16") (pin "1") (pinfunction "1_1") (pintype "passive"))
      (node (ref "C1_2") (pin "1") (pinfunction "1_1") (pintype "passive"))
      (node (ref "C1_3") (pin "1") (pinfunction "1_1") (pintype "passive"))
      (node (ref "C1_4") (pin "1") (pinfunction "1_1") (pintype "passive"))
      (node (ref "C1_5") (pin "1") (pinfunction "1_1") (pintype "passive"))
      (node (ref "C1_6") (pin "1") (pinfunction "1_1") (pintype "passive"))
      (node (ref "C1_7") (pin "1") (pinfunction "1_1") (pintype "passive"))
      (node (ref "C1_8") (pin "1") (pinfunction "1_1") (pintype "passive"))
      (node (ref "C1_9") (pin "1") (pinfunction "1_1") (pintype "passive"))
      (node (ref "C2_1") (pin "1") (pinfunction "1_1") (pintype "passive"))
      (node (ref "C2_10") (pin "1") (pinfunction "1_1") (pintype "passive"))
      (node (ref "C2_11") (pin "1") (pinfunction "1_1") (pintype "passive"))
      (node (ref "C2_12") (pin "1") (pinfunction "1_1") (pintype "passive"))
      (node (ref "C2_13") (pin "1") (pinfunction "1_1") (pintype "passive"))
      (node (ref "C2_14") (pin "1") (pinfunction "1_1") (pintype "passive"))
      (node (ref "C2_15") (pin "1") (pinfunction "1_1") (pintype "passive"))
      (node (ref "C2_16") (pin "1") (pinfunction "1_1") (pintype "passive"))
      (node (ref "C2_2") (pin "1") (pinfunction "1_1") (pintype "passive"))
      (node (ref "C2_3") (pin "1") (pinfunction "1_1") (pintype "passive"))
      (node (ref "C2_4") (pin "1") (pinfunction "1_1") (pintype "passive"))
      (node (ref "C2_5") (pin "1") (pinfunction "1_1") (pintype "passive"))
      (node (ref "C2_6") (pin "1") (pinfunction "1_1") (pintype "passive"))
      (node (ref "C2_7") (pin "1") (pinfunction "1_1") (pintype "passive"))
      (node (ref "C2_8") (pin "1") (pinfunction "1_1") (pintype "passive"))
      (node (ref "C2_9") (pin "1") (pinfunction "1_1") (pintype "passive"))
      (node (ref "C3_1") (pin "1") (pinfunction "1_1") (pintype "passive"))
      (node (ref "C3_10") (pin "1") (pinfunction "1_1") (pintype "passive"))
      (node (ref "C3_11") (pin "1") (pinfunction "1_1") (pintype "passive"))
      (node (ref "C3_12") (pin "1") (pinfunction "1_1") (pintype "passive"))
      (node (ref "C3_13") (pin "1") (pinfunction "1_1") (pintype "passive"))
      (node (ref "C3_14") (pin "1") (pinfunction "1_1") (pintype "passive"))
      (node (ref "C3_15") (pin "1") (pinfunction "1_1") (pintype "passive"))
      (node (ref "C3_16") (pin "1") (pinfunction "1_1") (pintype "passive"))
      (node (ref "C3_2") (pin "1") (pinfunction "1_1") (pintype "passive"))
      (node (ref "C3_3") (pin "1") (pinfunction "1_1") (pintype "passive"))
      (node (ref "C3_4") (pin "1") (pinfunction "1_1") (pintype "passive"))
      (node (ref "C3_5") (pin "1") (pinfunction "1_1") (pintype "passive"))
      (node (ref "C3_6") (pin "1") (pinfunction "1_1") (pintype "passive"))
      (node (ref "C3_7") (pin "1") (pinfunction "1_1") (pintype "passive"))
      (node (ref "C3_8") (pin "1") (pinfunction "1_1") (pintype "passive"))
      (node (ref "C3_9") (pin "1") (pinfunction "1_1") (pintype "passive"))
      (node (ref "C4_1") (pin "1") (pinfunction "1_1") (pintype "passive"))
      (node (ref "C4_10") (pin "1") (pinfunction "1_1") (pintype "passive"))
      (node (ref "C4_11") (pin "1") (pinfunction "1_1") (pintype "passive"))
      (node (ref "C4_12") (pin "1") (pinfunction "1_1") (pintype "passive"))
      (node (ref "C4_13") (pin "1") (pinfunction "1_1") (pintype "passive"))
      (node (ref "C4_14") (pin "1") (pinfunction "1_1") (pintype "passive"))
      (node (ref "C4_15") (pin "1") (pinfunction "1_1") (pintype "passive"))
      (node (ref "C4_16") (pin "1") (pinfunction "1_1") (pintype "passive"))
      (node (ref "C4_2") (pin "1") (pinfunction "1_1") (pintype "passive"))
      (node (ref "C4_3") (pin "1") (pinfunction "1_1") (pintype "passive"))
      (node (ref "C4_4") (pin "1") (pinfunction "1_1") (pintype "passive"))
      (node (ref "C4_5") (pin "1") (pinfunction "1_1") (pintype "passive"))
      (node (ref "C4_6") (pin "1") (pinfunction "1_1") (pintype "passive"))
      (node (ref "C4_7") (pin "1") (pinfunction "1_1") (pintype "passive"))
      (node (ref "C4_8") (pin "1") (pinfunction "1_1") (pintype "passive"))
      (node (ref "C4_9") (pin "1") (pinfunction "1_1") (pintype "passive"))
      (node (ref "C6P_1") (pin "1") (pinfunction "1_1") (pintype "passive"))
      (node (ref "C6P_2") (pin "1") (pinfunction "1_1") (pintype "passive"))
      (node (ref "C6P_3") (pin "1") (pinfunction "1_1") (pintype "passive"))
      (node (ref "C6_1") (pin "1") (pinfunction "1_1") (pintype "passive"))
      (node (ref "C6_10") (pin "1") (pinfunction "1_1") (pintype "passive"))
      (node (ref "C6_11") (pin "1") (pinfunction "1_1") (pintype "passive"))
      (node (ref "C6_12") (pin "1") (pinfunction "1_1") (pintype "passive"))
      (node (ref "C6_13") (pin "1") (pinfunction "1_1") (pintype "passive"))
      (node (ref "C6_14") (pin "1") (pinfunction "1_1") (pintype "passive"))
      (node (ref "C6_15") (pin "1") (pinfunction "1_1") (pintype "passive"))
      (node (ref "C6_16") (pin "1") (pinfunction "1_1") (pintype "passive"))
      (node (ref "C6_2") (pin "1") (pinfunction "1_1") (pintype "passive"))
      (node (ref "C6_3") (pin "1") (pinfunction "1_1") (pintype "passive"))
      (node (ref "C6_4") (pin "1") (pinfunction "1_1") (pintype "passive"))
      (node (ref "C6_5") (pin "1") (pinfunction "1_1") (pintype "passive"))
      (node (ref "C6_6") (pin "1") (pinfunction "1_1") (pintype "passive"))
      (node (ref "C6_7") (pin "1") (pinfunction "1_1") (pintype "passive"))
      (node (ref "C6_8") (pin "1") (pinfunction "1_1") (pintype "passive"))
      (node (ref "C6_9") (pin "1") (pinfunction "1_1") (pintype "passive"))
      (node (ref "C7P_1") (pin "1") (pinfunction "1_1") (pintype "passive"))
      (node (ref "C7P_2") (pin "1") (pinfunction "1_1") (pintype "passive"))
      (node (ref "C7P_3") (pin "1") (pinfunction "1_1") (pintype "passive"))
      (node (ref "C7_1") (pin "1") (pinfunction "1_1") (pintype "passive"))
      (node (ref "C7_10") (pin "1") (pinfunction "1_1") (pintype "passive"))
      (node (ref "C7_11") (pin "1") (pinfunction "1_1") (pintype "passive"))
      (node (ref "C7_12") (pin "1") (pinfunction "1_1") (pintype "passive"))
      (node (ref "C7_13") (pin "1") (pinfunction "1_1") (pintype "passive"))
      (node (ref "C7_14") (pin "1") (pinfunction "1_1") (pintype "passive"))
      (node (ref "C7_15") (pin "1") (pinfunction "1_1") (pintype "passive"))
      (node (ref "C7_16") (pin "1") (pinfunction "1_1") (pintype "passive"))
      (node (ref "C7_2") (pin "1") (pinfunction "1_1") (pintype "passive"))
      (node (ref "C7_3") (pin "1") (pinfunction "1_1") (pintype "passive"))
      (node (ref "C7_4") (pin "1") (pinfunction "1_1") (pintype "passive"))
      (node (ref "C7_5") (pin "1") (pinfunction "1_1") (pintype "passive"))
      (node (ref "C7_6") (pin "1") (pinfunction "1_1") (pintype "passive"))
      (node (ref "C7_7") (pin "1") (pinfunction "1_1") (pintype "passive"))
      (node (ref "C7_8") (pin "1") (pinfunction "1_1") (pintype "passive"))
      (node (ref "C7_9") (pin "1") (pinfunction "1_1") (pintype "passive"))
      (node (ref "C8P_1") (pin "1") (pinfunction "1_1") (pintype "passive"))
      (node (ref "C8P_2") (pin "1") (pinfunction "1_1") (pintype "passive"))
      (node (ref "C8P_3") (pin "1") (pinfunction "1_1") (pintype "passive"))
      (node (ref "C9_1") (pin "1") (pinfunction "1_1") (pintype "passive"))
      (node (ref "C9_10") (pin "1") (pinfunction "1_1") (pintype "passive"))
      (node (ref "C9_11") (pin "1") (pinfunction "1_1") (pintype "passive"))
      (node (ref "C9_12") (pin "1") (pinfunction "1_1") (pintype "passive"))
      (node (ref "C9_13") (pin "1") (pinfunction "1_1") (pintype "passive"))
      (node (ref "C9_14") (pin "1") (pinfunction "1_1") (pintype "passive"))
      (node (ref "C9_15") (pin "1") (pinfunction "1_1") (pintype "passive"))
      (node (ref "C9_16") (pin "1") (pinfunction "1_1") (pintype "passive"))
      (node (ref "C9_2") (pin "1") (pinfunction "1_1") (pintype "passive"))
      (node (ref "C9_3") (pin "1") (pinfunction "1_1") (pintype "passive"))
      (node (ref "C9_4") (pin "1") (pinfunction "1_1") (pintype "passive"))
      (node (ref "C9_5") (pin "1") (pinfunction "1_1") (pintype "passive"))
      (node (ref "C9_6") (pin "1") (pinfunction "1_1") (pintype "passive"))
      (node (ref "C9_7") (pin "1") (pinfunction "1_1") (pintype "passive"))
      (node (ref "C9_8") (pin "1") (pinfunction "1_1") (pintype "passive"))
      (node (ref "C9_9") (pin "1") (pinfunction "1_1") (pintype "passive"))
      (node (ref "C_220_1") (pin "1") (pinfunction "1_1") (pintype "passive"))
      (node (ref "C_220_10") (pin "1") (pinfunction "1_1") (pintype "passive"))
      (node (ref "C_220_11") (pin "1") (pinfunction "1_1") (pintype "passive"))
      (node (ref "C_220_12") (pin "1") (pinfunction "1_1") (pintype "passive"))
      (node (ref "C_220_13") (pin "1") (pinfunction "1_1") (pintype "passive"))
      (node (ref "C_220_14") (pin "1") (pinfunction "1_1") (pintype "passive"))
      (node (ref "C_220_15") (pin "1") (pinfunction "1_1") (pintype "passive"))
      (node (ref "C_220_16") (pin "1") (pinfunction "1_1") (pintype "passive"))
      (node (ref "C_220_17") (pin "1") (pinfunction "1_1") (pintype "passive"))
      (node (ref "C_220_18") (pin "1") (pinfunction "1_1") (pintype "passive"))
      (node (ref "C_220_19") (pin "1") (pinfunction "1_1") (pintype "passive"))
      (node (ref "C_220_2") (pin "1") (pinfunction "1_1") (pintype "passive"))
      (node (ref "C_220_20") (pin "1") (pinfunction "1_1") (pintype "passive"))
      (node (ref "C_220_21") (pin "1") (pinfunction "1_1") (pintype "passive"))
      (node (ref "C_220_22") (pin "1") (pinfunction "1_1") (pintype "passive"))
      (node (ref "C_220_23") (pin "1") (pinfunction "1_1") (pintype "passive"))
      (node (ref "C_220_24") (pin "1") (pinfunction "1_1") (pintype "passive"))
      (node (ref "C_220_25") (pin "1") (pinfunction "1_1") (pintype "passive"))
      (node (ref "C_220_26") (pin "1") (pinfunction "1_1") (pintype "passive"))
      (node (ref "C_220_27") (pin "1") (pinfunction "1_1") (pintype "passive"))
      (node (ref "C_220_28") (pin "1") (pinfunction "1_1") (pintype "passive"))
      (node (ref "C_220_29") (pin "1") (pinfunction "1_1") (pintype "passive"))
      (node (ref "C_220_3") (pin "1") (pinfunction "1_1") (pintype "passive"))
      (node (ref "C_220_30") (pin "1") (pinfunction "1_1") (pintype "passive"))
      (node (ref "C_220_31") (pin "1") (pinfunction "1_1") (pintype "passive"))
      (node (ref "C_220_32") (pin "1") (pinfunction "1_1") (pintype "passive"))
      (node (ref "C_220_33") (pin "1") (pinfunction "1_1") (pintype "passive"))
      (node (ref "C_220_34") (pin "1") (pinfunction "1_1") (pintype "passive"))
      (node (ref "C_220_35") (pin "1") (pinfunction "1_1") (pintype "passive"))
      (node (ref "C_220_36") (pin "1") (pinfunction "1_1") (pintype "passive"))
      (node (ref "C_220_37") (pin "1") (pinfunction "1_1") (pintype "passive"))
      (node (ref "C_220_38") (pin "1") (pinfunction "1_1") (pintype "passive"))
      (node (ref "C_220_39") (pin "1") (pinfunction "1_1") (pintype "passive"))
      (node (ref "C_220_4") (pin "1") (pinfunction "1_1") (pintype "passive"))
      (node (ref "C_220_40") (pin "1") (pinfunction "1_1") (pintype "passive"))
      (node (ref "C_220_41") (pin "1") (pinfunction "1_1") (pintype "passive"))
      (node (ref "C_220_42") (pin "1") (pinfunction "1_1") (pintype "passive"))
      (node (ref "C_220_43") (pin "1") (pinfunction "1_1") (pintype "passive"))
      (node (ref "C_220_44") (pin "1") (pinfunction "1_1") (pintype "passive"))
      (node (ref "C_220_45") (pin "1") (pinfunction "1_1") (pintype "passive"))
      (node (ref "C_220_46") (pin "1") (pinfunction "1_1") (pintype "passive"))
      (node (ref "C_220_47") (pin "1") (pinfunction "1_1") (pintype "passive"))
      (node (ref "C_220_48") (pin "1") (pinfunction "1_1") (pintype "passive"))
      (node (ref "C_220_49") (pin "1") (pinfunction "1_1") (pintype "passive"))
      (node (ref "C_220_5") (pin "1") (pinfunction "1_1") (pintype "passive"))
      (node (ref "C_220_50") (pin "1") (pinfunction "1_1") (pintype "passive"))
      (node (ref "C_220_51") (pin "1") (pinfunction "1_1") (pintype "passive"))
      (node (ref "C_220_52") (pin "1") (pinfunction "1_1") (pintype "passive"))
      (node (ref "C_220_53") (pin "1") (pinfunction "1_1") (pintype "passive"))
      (node (ref "C_220_54") (pin "1") (pinfunction "1_1") (pintype "passive"))
      (node (ref "C_220_55") (pin "1") (pinfunction "1_1") (pintype "passive"))
      (node (ref "C_220_56") (pin "1") (pinfunction "1_1") (pintype "passive"))
      (node (ref "C_220_57") (pin "1") (pinfunction "1_1") (pintype "passive"))
      (node (ref "C_220_58") (pin "1") (pinfunction "1_1") (pintype "passive"))
      (node (ref "C_220_59") (pin "1") (pinfunction "1_1") (pintype "passive"))
      (node (ref "C_220_6") (pin "1") (pinfunction "1_1") (pintype "passive"))
      (node (ref "C_220_60") (pin "1") (pinfunction "1_1") (pintype "passive"))
      (node (ref "C_220_61") (pin "1") (pinfunction "1_1") (pintype "passive"))
      (node (ref "C_220_62") (pin "1") (pinfunction "1_1") (pintype "passive"))
      (node (ref "C_220_63") (pin "1") (pinfunction "1_1") (pintype "passive"))
      (node (ref "C_220_64") (pin "1") (pinfunction "1_1") (pintype "passive"))
      (node (ref "C_220_65") (pin "1") (pinfunction "1_1") (pintype "passive"))
      (node (ref "C_220_66") (pin "1") (pinfunction "1_1") (pintype "passive"))
      (node (ref "C_220_67") (pin "1") (pinfunction "1_1") (pintype "passive"))
      (node (ref "C_220_68") (pin "1") (pinfunction "1_1") (pintype "passive"))
      (node (ref "C_220_69") (pin "1") (pinfunction "1_1") (pintype "passive"))
      (node (ref "C_220_7") (pin "1") (pinfunction "1_1") (pintype "passive"))
      (node (ref "C_220_70") (pin "1") (pinfunction "1_1") (pintype "passive"))
      (node (ref "C_220_71") (pin "1") (pinfunction "1_1") (pintype "passive"))
      (node (ref "C_220_73") (pin "1") (pinfunction "1_1") (pintype "passive"))
      (node (ref "C_220_8") (pin "1") (pinfunction "1_1") (pintype "passive"))
      (node (ref "C_220_9") (pin "1") (pinfunction "1_1") (pintype "passive"))
      (node (ref "L1P_1") (pin "2") (pinfunction "2_2") (pintype "passive"))
      (node (ref "L1P_2") (pin "2") (pinfunction "2_2") (pintype "passive"))
      (node (ref "L1P_3") (pin "2") (pinfunction "2_2") (pintype "passive"))
      (node (ref "R18") (pin "2") (pinfunction "2_2") (pintype "passive"))
      (node (ref "R20") (pin "2") (pinfunction "2_2") (pintype "passive"))
      (node (ref "R21") (pin "2") (pinfunction "2_2") (pintype "passive"))
      (node (ref "U1_1") (pin "10") (pinfunction "DVDD_10") (pintype "passive"))
      (node (ref "U1_1") (pin "11") (pinfunction "DVDD_11") (pintype "passive"))
      (node (ref "U1_1") (pin "13") (pinfunction "DVDD_13") (pintype "passive"))
      (node (ref "U1_1") (pin "14") (pinfunction "DVDD_14") (pintype "passive"))
      (node (ref "U1_1") (pin "15") (pinfunction "DVDD_15") (pintype "passive"))
      (node (ref "U1_1") (pin "18") (pinfunction "DVDD_18") (pintype "passive"))
      (node (ref "U1_1") (pin "19") (pinfunction "DVDD_19") (pintype "passive"))
      (node (ref "U1_1") (pin "20") (pinfunction "DVDD_20") (pintype "passive"))
      (node (ref "U1_1") (pin "21") (pinfunction "DVDD_21") (pintype "passive"))
      (node (ref "U1_1") (pin "22") (pinfunction "DVDD_22") (pintype "passive"))
      (node (ref "U1_1") (pin "25") (pinfunction "DVDD_25") (pintype "passive"))
      (node (ref "U1_1") (pin "26") (pinfunction "DVDD_26") (pintype "passive"))
      (node (ref "U1_1") (pin "28") (pinfunction "DVDD_28") (pintype "passive"))
      (node (ref "U1_1") (pin "29") (pinfunction "DVDD_29") (pintype "passive"))
      (node (ref "U1_1") (pin "3") (pinfunction "DVDD_3") (pintype "passive"))
      (node (ref "U1_1") (pin "30") (pinfunction "DVDD_30") (pintype "passive"))
      (node (ref "U1_1") (pin "31") (pinfunction "DVDD_31") (pintype "passive"))
      (node (ref "U1_1") (pin "32") (pinfunction "DVDD_32") (pintype "passive"))
      (node (ref "U1_1") (pin "33") (pinfunction "DVDD_33") (pintype "passive"))
      (node (ref "U1_1") (pin "34") (pinfunction "DVDD_34") (pintype "passive"))
      (node (ref "U1_1") (pin "39") (pinfunction "DVDD_39") (pintype "passive"))
      (node (ref "U1_1") (pin "4") (pinfunction "DVDD_4") (pintype "passive"))
      (node (ref "U1_1") (pin "40") (pinfunction "DVDD_40") (pintype "passive"))
      (node (ref "U1_1") (pin "41") (pinfunction "DVDD_41") (pintype "passive"))
      (node (ref "U1_1") (pin "42") (pinfunction "DVDD_42") (pintype "passive"))
      (node (ref "U1_1") (pin "45") (pinfunction "DVDD_45") (pintype "passive"))
      (node (ref "U1_1") (pin "46") (pinfunction "DVDD_46") (pintype "passive"))
      (node (ref "U1_1") (pin "47") (pinfunction "DVDD_47") (pintype "passive"))
      (node (ref "U1_1") (pin "48") (pinfunction "DVDD_48") (pintype "passive"))
      (node (ref "U1_10") (pin "10") (pinfunction "DVDD_10") (pintype "passive"))
      (node (ref "U1_10") (pin "11") (pinfunction "DVDD_11") (pintype "passive"))
      (node (ref "U1_10") (pin "13") (pinfunction "DVDD_13") (pintype "passive"))
      (node (ref "U1_10") (pin "14") (pinfunction "DVDD_14") (pintype "passive"))
      (node (ref "U1_10") (pin "15") (pinfunction "DVDD_15") (pintype "passive"))
      (node (ref "U1_10") (pin "18") (pinfunction "DVDD_18") (pintype "passive"))
      (node (ref "U1_10") (pin "19") (pinfunction "DVDD_19") (pintype "passive"))
      (node (ref "U1_10") (pin "20") (pinfunction "DVDD_20") (pintype "passive"))
      (node (ref "U1_10") (pin "21") (pinfunction "DVDD_21") (pintype "passive"))
      (node (ref "U1_10") (pin "22") (pinfunction "DVDD_22") (pintype "passive"))
      (node (ref "U1_10") (pin "25") (pinfunction "DVDD_25") (pintype "passive"))
      (node (ref "U1_10") (pin "26") (pinfunction "DVDD_26") (pintype "passive"))
      (node (ref "U1_10") (pin "28") (pinfunction "DVDD_28") (pintype "passive"))
      (node (ref "U1_10") (pin "29") (pinfunction "DVDD_29") (pintype "passive"))
      (node (ref "U1_10") (pin "3") (pinfunction "DVDD_3") (pintype "passive"))
      (node (ref "U1_10") (pin "30") (pinfunction "DVDD_30") (pintype "passive"))
      (node (ref "U1_10") (pin "31") (pinfunction "DVDD_31") (pintype "passive"))
      (node (ref "U1_10") (pin "32") (pinfunction "DVDD_32") (pintype "passive"))
      (node (ref "U1_10") (pin "33") (pinfunction "DVDD_33") (pintype "passive"))
      (node (ref "U1_10") (pin "34") (pinfunction "DVDD_34") (pintype "passive"))
      (node (ref "U1_10") (pin "39") (pinfunction "DVDD_39") (pintype "passive"))
      (node (ref "U1_10") (pin "4") (pinfunction "DVDD_4") (pintype "passive"))
      (node (ref "U1_10") (pin "40") (pinfunction "DVDD_40") (pintype "passive"))
      (node (ref "U1_10") (pin "41") (pinfunction "DVDD_41") (pintype "passive"))
      (node (ref "U1_10") (pin "42") (pinfunction "DVDD_42") (pintype "passive"))
      (node (ref "U1_10") (pin "45") (pinfunction "DVDD_45") (pintype "passive"))
      (node (ref "U1_10") (pin "46") (pinfunction "DVDD_46") (pintype "passive"))
      (node (ref "U1_10") (pin "47") (pinfunction "DVDD_47") (pintype "passive"))
      (node (ref "U1_10") (pin "48") (pinfunction "DVDD_48") (pintype "passive"))
      (node (ref "U1_11") (pin "10") (pinfunction "DVDD_10") (pintype "passive"))
      (node (ref "U1_11") (pin "11") (pinfunction "DVDD_11") (pintype "passive"))
      (node (ref "U1_11") (pin "13") (pinfunction "DVDD_13") (pintype "passive"))
      (node (ref "U1_11") (pin "14") (pinfunction "DVDD_14") (pintype "passive"))
      (node (ref "U1_11") (pin "15") (pinfunction "DVDD_15") (pintype "passive"))
      (node (ref "U1_11") (pin "18") (pinfunction "DVDD_18") (pintype "passive"))
      (node (ref "U1_11") (pin "19") (pinfunction "DVDD_19") (pintype "passive"))
      (node (ref "U1_11") (pin "20") (pinfunction "DVDD_20") (pintype "passive"))
      (node (ref "U1_11") (pin "21") (pinfunction "DVDD_21") (pintype "passive"))
      (node (ref "U1_11") (pin "22") (pinfunction "DVDD_22") (pintype "passive"))
      (node (ref "U1_11") (pin "25") (pinfunction "DVDD_25") (pintype "passive"))
      (node (ref "U1_11") (pin "26") (pinfunction "DVDD_26") (pintype "passive"))
      (node (ref "U1_11") (pin "28") (pinfunction "DVDD_28") (pintype "passive"))
      (node (ref "U1_11") (pin "29") (pinfunction "DVDD_29") (pintype "passive"))
      (node (ref "U1_11") (pin "3") (pinfunction "DVDD_3") (pintype "passive"))
      (node (ref "U1_11") (pin "30") (pinfunction "DVDD_30") (pintype "passive"))
      (node (ref "U1_11") (pin "31") (pinfunction "DVDD_31") (pintype "passive"))
      (node (ref "U1_11") (pin "32") (pinfunction "DVDD_32") (pintype "passive"))
      (node (ref "U1_11") (pin "33") (pinfunction "DVDD_33") (pintype "passive"))
      (node (ref "U1_11") (pin "34") (pinfunction "DVDD_34") (pintype "passive"))
      (node (ref "U1_11") (pin "39") (pinfunction "DVDD_39") (pintype "passive"))
      (node (ref "U1_11") (pin "4") (pinfunction "DVDD_4") (pintype "passive"))
      (node (ref "U1_11") (pin "40") (pinfunction "DVDD_40") (pintype "passive"))
      (node (ref "U1_11") (pin "41") (pinfunction "DVDD_41") (pintype "passive"))
      (node (ref "U1_11") (pin "42") (pinfunction "DVDD_42") (pintype "passive"))
      (node (ref "U1_11") (pin "45") (pinfunction "DVDD_45") (pintype "passive"))
      (node (ref "U1_11") (pin "46") (pinfunction "DVDD_46") (pintype "passive"))
      (node (ref "U1_11") (pin "47") (pinfunction "DVDD_47") (pintype "passive"))
      (node (ref "U1_11") (pin "48") (pinfunction "DVDD_48") (pintype "passive"))
      (node (ref "U1_12") (pin "10") (pinfunction "DVDD_10") (pintype "passive"))
      (node (ref "U1_12") (pin "11") (pinfunction "DVDD_11") (pintype "passive"))
      (node (ref "U1_12") (pin "13") (pinfunction "DVDD_13") (pintype "passive"))
      (node (ref "U1_12") (pin "14") (pinfunction "DVDD_14") (pintype "passive"))
      (node (ref "U1_12") (pin "15") (pinfunction "DVDD_15") (pintype "passive"))
      (node (ref "U1_12") (pin "18") (pinfunction "DVDD_18") (pintype "passive"))
      (node (ref "U1_12") (pin "19") (pinfunction "DVDD_19") (pintype "passive"))
      (node (ref "U1_12") (pin "20") (pinfunction "DVDD_20") (pintype "passive"))
      (node (ref "U1_12") (pin "21") (pinfunction "DVDD_21") (pintype "passive"))
      (node (ref "U1_12") (pin "22") (pinfunction "DVDD_22") (pintype "passive"))
      (node (ref "U1_12") (pin "25") (pinfunction "DVDD_25") (pintype "passive"))
      (node (ref "U1_12") (pin "26") (pinfunction "DVDD_26") (pintype "passive"))
      (node (ref "U1_12") (pin "28") (pinfunction "DVDD_28") (pintype "passive"))
      (node (ref "U1_12") (pin "29") (pinfunction "DVDD_29") (pintype "passive"))
      (node (ref "U1_12") (pin "3") (pinfunction "DVDD_3") (pintype "passive"))
      (node (ref "U1_12") (pin "30") (pinfunction "DVDD_30") (pintype "passive"))
      (node (ref "U1_12") (pin "31") (pinfunction "DVDD_31") (pintype "passive"))
      (node (ref "U1_12") (pin "32") (pinfunction "DVDD_32") (pintype "passive"))
      (node (ref "U1_12") (pin "33") (pinfunction "DVDD_33") (pintype "passive"))
      (node (ref "U1_12") (pin "34") (pinfunction "DVDD_34") (pintype "passive"))
      (node (ref "U1_12") (pin "39") (pinfunction "DVDD_39") (pintype "passive"))
      (node (ref "U1_12") (pin "4") (pinfunction "DVDD_4") (pintype "passive"))
      (node (ref "U1_12") (pin "40") (pinfunction "DVDD_40") (pintype "passive"))
      (node (ref "U1_12") (pin "41") (pinfunction "DVDD_41") (pintype "passive"))
      (node (ref "U1_12") (pin "42") (pinfunction "DVDD_42") (pintype "passive"))
      (node (ref "U1_12") (pin "45") (pinfunction "DVDD_45") (pintype "passive"))
      (node (ref "U1_12") (pin "46") (pinfunction "DVDD_46") (pintype "passive"))
      (node (ref "U1_12") (pin "47") (pinfunction "DVDD_47") (pintype "passive"))
      (node (ref "U1_12") (pin "48") (pinfunction "DVDD_48") (pintype "passive"))
      (node (ref "U1_13") (pin "10") (pinfunction "DVDD_10") (pintype "passive"))
      (node (ref "U1_13") (pin "11") (pinfunction "DVDD_11") (pintype "passive"))
      (node (ref "U1_13") (pin "13") (pinfunction "DVDD_13") (pintype "passive"))
      (node (ref "U1_13") (pin "14") (pinfunction "DVDD_14") (pintype "passive"))
      (node (ref "U1_13") (pin "15") (pinfunction "DVDD_15") (pintype "passive"))
      (node (ref "U1_13") (pin "18") (pinfunction "DVDD_18") (pintype "passive"))
      (node (ref "U1_13") (pin "19") (pinfunction "DVDD_19") (pintype "passive"))
      (node (ref "U1_13") (pin "20") (pinfunction "DVDD_20") (pintype "passive"))
      (node (ref "U1_13") (pin "21") (pinfunction "DVDD_21") (pintype "passive"))
      (node (ref "U1_13") (pin "22") (pinfunction "DVDD_22") (pintype "passive"))
      (node (ref "U1_13") (pin "25") (pinfunction "DVDD_25") (pintype "passive"))
      (node (ref "U1_13") (pin "26") (pinfunction "DVDD_26") (pintype "passive"))
      (node (ref "U1_13") (pin "28") (pinfunction "DVDD_28") (pintype "passive"))
      (node (ref "U1_13") (pin "29") (pinfunction "DVDD_29") (pintype "passive"))
      (node (ref "U1_13") (pin "3") (pinfunction "DVDD_3") (pintype "passive"))
      (node (ref "U1_13") (pin "30") (pinfunction "DVDD_30") (pintype "passive"))
      (node (ref "U1_13") (pin "31") (pinfunction "DVDD_31") (pintype "passive"))
      (node (ref "U1_13") (pin "32") (pinfunction "DVDD_32") (pintype "passive"))
      (node (ref "U1_13") (pin "33") (pinfunction "DVDD_33") (pintype "passive"))
      (node (ref "U1_13") (pin "34") (pinfunction "DVDD_34") (pintype "passive"))
      (node (ref "U1_13") (pin "39") (pinfunction "DVDD_39") (pintype "passive"))
      (node (ref "U1_13") (pin "4") (pinfunction "DVDD_4") (pintype "passive"))
      (node (ref "U1_13") (pin "40") (pinfunction "DVDD_40") (pintype "passive"))
      (node (ref "U1_13") (pin "41") (pinfunction "DVDD_41") (pintype "passive"))
      (node (ref "U1_13") (pin "42") (pinfunction "DVDD_42") (pintype "passive"))
      (node (ref "U1_13") (pin "45") (pinfunction "DVDD_45") (pintype "passive"))
      (node (ref "U1_13") (pin "46") (pinfunction "DVDD_46") (pintype "passive"))
      (node (ref "U1_13") (pin "47") (pinfunction "DVDD_47") (pintype "passive"))
      (node (ref "U1_13") (pin "48") (pinfunction "DVDD_48") (pintype "passive"))
      (node (ref "U1_14") (pin "10") (pinfunction "DVDD_10") (pintype "passive"))
      (node (ref "U1_14") (pin "11") (pinfunction "DVDD_11") (pintype "passive"))
      (node (ref "U1_14") (pin "13") (pinfunction "DVDD_13") (pintype "passive"))
      (node (ref "U1_14") (pin "14") (pinfunction "DVDD_14") (pintype "passive"))
      (node (ref "U1_14") (pin "15") (pinfunction "DVDD_15") (pintype "passive"))
      (node (ref "U1_14") (pin "18") (pinfunction "DVDD_18") (pintype "passive"))
      (node (ref "U1_14") (pin "19") (pinfunction "DVDD_19") (pintype "passive"))
      (node (ref "U1_14") (pin "20") (pinfunction "DVDD_20") (pintype "passive"))
      (node (ref "U1_14") (pin "21") (pinfunction "DVDD_21") (pintype "passive"))
      (node (ref "U1_14") (pin "22") (pinfunction "DVDD_22") (pintype "passive"))
      (node (ref "U1_14") (pin "25") (pinfunction "DVDD_25") (pintype "passive"))
      (node (ref "U1_14") (pin "26") (pinfunction "DVDD_26") (pintype "passive"))
      (node (ref "U1_14") (pin "28") (pinfunction "DVDD_28") (pintype "passive"))
      (node (ref "U1_14") (pin "29") (pinfunction "DVDD_29") (pintype "passive"))
      (node (ref "U1_14") (pin "3") (pinfunction "DVDD_3") (pintype "passive"))
      (node (ref "U1_14") (pin "30") (pinfunction "DVDD_30") (pintype "passive"))
      (node (ref "U1_14") (pin "31") (pinfunction "DVDD_31") (pintype "passive"))
      (node (ref "U1_14") (pin "32") (pinfunction "DVDD_32") (pintype "passive"))
      (node (ref "U1_14") (pin "33") (pinfunction "DVDD_33") (pintype "passive"))
      (node (ref "U1_14") (pin "34") (pinfunction "DVDD_34") (pintype "passive"))
      (node (ref "U1_14") (pin "39") (pinfunction "DVDD_39") (pintype "passive"))
      (node (ref "U1_14") (pin "4") (pinfunction "DVDD_4") (pintype "passive"))
      (node (ref "U1_14") (pin "40") (pinfunction "DVDD_40") (pintype "passive"))
      (node (ref "U1_14") (pin "41") (pinfunction "DVDD_41") (pintype "passive"))
      (node (ref "U1_14") (pin "42") (pinfunction "DVDD_42") (pintype "passive"))
      (node (ref "U1_14") (pin "45") (pinfunction "DVDD_45") (pintype "passive"))
      (node (ref "U1_14") (pin "46") (pinfunction "DVDD_46") (pintype "passive"))
      (node (ref "U1_14") (pin "47") (pinfunction "DVDD_47") (pintype "passive"))
      (node (ref "U1_14") (pin "48") (pinfunction "DVDD_48") (pintype "passive"))
      (node (ref "U1_15") (pin "10") (pinfunction "DVDD_10") (pintype "passive"))
      (node (ref "U1_15") (pin "11") (pinfunction "DVDD_11") (pintype "passive"))
      (node (ref "U1_15") (pin "13") (pinfunction "DVDD_13") (pintype "passive"))
      (node (ref "U1_15") (pin "14") (pinfunction "DVDD_14") (pintype "passive"))
      (node (ref "U1_15") (pin "15") (pinfunction "DVDD_15") (pintype "passive"))
      (node (ref "U1_15") (pin "18") (pinfunction "DVDD_18") (pintype "passive"))
      (node (ref "U1_15") (pin "19") (pinfunction "DVDD_19") (pintype "passive"))
      (node (ref "U1_15") (pin "20") (pinfunction "DVDD_20") (pintype "passive"))
      (node (ref "U1_15") (pin "21") (pinfunction "DVDD_21") (pintype "passive"))
      (node (ref "U1_15") (pin "22") (pinfunction "DVDD_22") (pintype "passive"))
      (node (ref "U1_15") (pin "25") (pinfunction "DVDD_25") (pintype "passive"))
      (node (ref "U1_15") (pin "26") (pinfunction "DVDD_26") (pintype "passive"))
      (node (ref "U1_15") (pin "28") (pinfunction "DVDD_28") (pintype "passive"))
      (node (ref "U1_15") (pin "29") (pinfunction "DVDD_29") (pintype "passive"))
      (node (ref "U1_15") (pin "3") (pinfunction "DVDD_3") (pintype "passive"))
      (node (ref "U1_15") (pin "30") (pinfunction "DVDD_30") (pintype "passive"))
      (node (ref "U1_15") (pin "31") (pinfunction "DVDD_31") (pintype "passive"))
      (node (ref "U1_15") (pin "32") (pinfunction "DVDD_32") (pintype "passive"))
      (node (ref "U1_15") (pin "33") (pinfunction "DVDD_33") (pintype "passive"))
      (node (ref "U1_15") (pin "34") (pinfunction "DVDD_34") (pintype "passive"))
      (node (ref "U1_15") (pin "39") (pinfunction "DVDD_39") (pintype "passive"))
      (node (ref "U1_15") (pin "4") (pinfunction "DVDD_4") (pintype "passive"))
      (node (ref "U1_15") (pin "40") (pinfunction "DVDD_40") (pintype "passive"))
      (node (ref "U1_15") (pin "41") (pinfunction "DVDD_41") (pintype "passive"))
      (node (ref "U1_15") (pin "42") (pinfunction "DVDD_42") (pintype "passive"))
      (node (ref "U1_15") (pin "45") (pinfunction "DVDD_45") (pintype "passive"))
      (node (ref "U1_15") (pin "46") (pinfunction "DVDD_46") (pintype "passive"))
      (node (ref "U1_15") (pin "47") (pinfunction "DVDD_47") (pintype "passive"))
      (node (ref "U1_15") (pin "48") (pinfunction "DVDD_48") (pintype "passive"))
      (node (ref "U1_16") (pin "10") (pinfunction "DVDD_10") (pintype "passive"))
      (node (ref "U1_16") (pin "11") (pinfunction "DVDD_11") (pintype "passive"))
      (node (ref "U1_16") (pin "13") (pinfunction "DVDD_13") (pintype "passive"))
      (node (ref "U1_16") (pin "14") (pinfunction "DVDD_14") (pintype "passive"))
      (node (ref "U1_16") (pin "15") (pinfunction "DVDD_15") (pintype "passive"))
      (node (ref "U1_16") (pin "18") (pinfunction "DVDD_18") (pintype "passive"))
      (node (ref "U1_16") (pin "19") (pinfunction "DVDD_19") (pintype "passive"))
      (node (ref "U1_16") (pin "20") (pinfunction "DVDD_20") (pintype "passive"))
      (node (ref "U1_16") (pin "21") (pinfunction "DVDD_21") (pintype "passive"))
      (node (ref "U1_16") (pin "22") (pinfunction "DVDD_22") (pintype "passive"))
      (node (ref "U1_16") (pin "25") (pinfunction "DVDD_25") (pintype "passive"))
      (node (ref "U1_16") (pin "26") (pinfunction "DVDD_26") (pintype "passive"))
      (node (ref "U1_16") (pin "28") (pinfunction "DVDD_28") (pintype "passive"))
      (node (ref "U1_16") (pin "29") (pinfunction "DVDD_29") (pintype "passive"))
      (node (ref "U1_16") (pin "3") (pinfunction "DVDD_3") (pintype "passive"))
      (node (ref "U1_16") (pin "30") (pinfunction "DVDD_30") (pintype "passive"))
      (node (ref "U1_16") (pin "31") (pinfunction "DVDD_31") (pintype "passive"))
      (node (ref "U1_16") (pin "32") (pinfunction "DVDD_32") (pintype "passive"))
      (node (ref "U1_16") (pin "33") (pinfunction "DVDD_33") (pintype "passive"))
      (node (ref "U1_16") (pin "34") (pinfunction "DVDD_34") (pintype "passive"))
      (node (ref "U1_16") (pin "39") (pinfunction "DVDD_39") (pintype "passive"))
      (node (ref "U1_16") (pin "4") (pinfunction "DVDD_4") (pintype "passive"))
      (node (ref "U1_16") (pin "40") (pinfunction "DVDD_40") (pintype "passive"))
      (node (ref "U1_16") (pin "41") (pinfunction "DVDD_41") (pintype "passive"))
      (node (ref "U1_16") (pin "42") (pinfunction "DVDD_42") (pintype "passive"))
      (node (ref "U1_16") (pin "45") (pinfunction "DVDD_45") (pintype "passive"))
      (node (ref "U1_16") (pin "46") (pinfunction "DVDD_46") (pintype "passive"))
      (node (ref "U1_16") (pin "47") (pinfunction "DVDD_47") (pintype "passive"))
      (node (ref "U1_16") (pin "48") (pinfunction "DVDD_48") (pintype "passive"))
      (node (ref "U1_2") (pin "10") (pinfunction "DVDD_10") (pintype "passive"))
      (node (ref "U1_2") (pin "11") (pinfunction "DVDD_11") (pintype "passive"))
      (node (ref "U1_2") (pin "13") (pinfunction "DVDD_13") (pintype "passive"))
      (node (ref "U1_2") (pin "14") (pinfunction "DVDD_14") (pintype "passive"))
      (node (ref "U1_2") (pin "15") (pinfunction "DVDD_15") (pintype "passive"))
      (node (ref "U1_2") (pin "18") (pinfunction "DVDD_18") (pintype "passive"))
      (node (ref "U1_2") (pin "19") (pinfunction "DVDD_19") (pintype "passive"))
      (node (ref "U1_2") (pin "20") (pinfunction "DVDD_20") (pintype "passive"))
      (node (ref "U1_2") (pin "21") (pinfunction "DVDD_21") (pintype "passive"))
      (node (ref "U1_2") (pin "22") (pinfunction "DVDD_22") (pintype "passive"))
      (node (ref "U1_2") (pin "25") (pinfunction "DVDD_25") (pintype "passive"))
      (node (ref "U1_2") (pin "26") (pinfunction "DVDD_26") (pintype "passive"))
      (node (ref "U1_2") (pin "28") (pinfunction "DVDD_28") (pintype "passive"))
      (node (ref "U1_2") (pin "29") (pinfunction "DVDD_29") (pintype "passive"))
      (node (ref "U1_2") (pin "3") (pinfunction "DVDD_3") (pintype "passive"))
      (node (ref "U1_2") (pin "30") (pinfunction "DVDD_30") (pintype "passive"))
      (node (ref "U1_2") (pin "31") (pinfunction "DVDD_31") (pintype "passive"))
      (node (ref "U1_2") (pin "32") (pinfunction "DVDD_32") (pintype "passive"))
      (node (ref "U1_2") (pin "33") (pinfunction "DVDD_33") (pintype "passive"))
      (node (ref "U1_2") (pin "34") (pinfunction "DVDD_34") (pintype "passive"))
      (node (ref "U1_2") (pin "39") (pinfunction "DVDD_39") (pintype "passive"))
      (node (ref "U1_2") (pin "4") (pinfunction "DVDD_4") (pintype "passive"))
      (node (ref "U1_2") (pin "40") (pinfunction "DVDD_40") (pintype "passive"))
      (node (ref "U1_2") (pin "41") (pinfunction "DVDD_41") (pintype "passive"))
      (node (ref "U1_2") (pin "42") (pinfunction "DVDD_42") (pintype "passive"))
      (node (ref "U1_2") (pin "45") (pinfunction "DVDD_45") (pintype "passive"))
      (node (ref "U1_2") (pin "46") (pinfunction "DVDD_46") (pintype "passive"))
      (node (ref "U1_2") (pin "47") (pinfunction "DVDD_47") (pintype "passive"))
      (node (ref "U1_2") (pin "48") (pinfunction "DVDD_48") (pintype "passive"))
      (node (ref "U1_3") (pin "10") (pinfunction "DVDD_10") (pintype "passive"))
      (node (ref "U1_3") (pin "11") (pinfunction "DVDD_11") (pintype "passive"))
      (node (ref "U1_3") (pin "13") (pinfunction "DVDD_13") (pintype "passive"))
      (node (ref "U1_3") (pin "14") (pinfunction "DVDD_14") (pintype "passive"))
      (node (ref "U1_3") (pin "15") (pinfunction "DVDD_15") (pintype "passive"))
      (node (ref "U1_3") (pin "18") (pinfunction "DVDD_18") (pintype "passive"))
      (node (ref "U1_3") (pin "19") (pinfunction "DVDD_19") (pintype "passive"))
      (node (ref "U1_3") (pin "20") (pinfunction "DVDD_20") (pintype "passive"))
      (node (ref "U1_3") (pin "21") (pinfunction "DVDD_21") (pintype "passive"))
      (node (ref "U1_3") (pin "22") (pinfunction "DVDD_22") (pintype "passive"))
      (node (ref "U1_3") (pin "25") (pinfunction "DVDD_25") (pintype "passive"))
      (node (ref "U1_3") (pin "26") (pinfunction "DVDD_26") (pintype "passive"))
      (node (ref "U1_3") (pin "28") (pinfunction "DVDD_28") (pintype "passive"))
      (node (ref "U1_3") (pin "29") (pinfunction "DVDD_29") (pintype "passive"))
      (node (ref "U1_3") (pin "3") (pinfunction "DVDD_3") (pintype "passive"))
      (node (ref "U1_3") (pin "30") (pinfunction "DVDD_30") (pintype "passive"))
      (node (ref "U1_3") (pin "31") (pinfunction "DVDD_31") (pintype "passive"))
      (node (ref "U1_3") (pin "32") (pinfunction "DVDD_32") (pintype "passive"))
      (node (ref "U1_3") (pin "33") (pinfunction "DVDD_33") (pintype "passive"))
      (node (ref "U1_3") (pin "34") (pinfunction "DVDD_34") (pintype "passive"))
      (node (ref "U1_3") (pin "39") (pinfunction "DVDD_39") (pintype "passive"))
      (node (ref "U1_3") (pin "4") (pinfunction "DVDD_4") (pintype "passive"))
      (node (ref "U1_3") (pin "40") (pinfunction "DVDD_40") (pintype "passive"))
      (node (ref "U1_3") (pin "41") (pinfunction "DVDD_41") (pintype "passive"))
      (node (ref "U1_3") (pin "42") (pinfunction "DVDD_42") (pintype "passive"))
      (node (ref "U1_3") (pin "45") (pinfunction "DVDD_45") (pintype "passive"))
      (node (ref "U1_3") (pin "46") (pinfunction "DVDD_46") (pintype "passive"))
      (node (ref "U1_3") (pin "47") (pinfunction "DVDD_47") (pintype "passive"))
      (node (ref "U1_3") (pin "48") (pinfunction "DVDD_48") (pintype "passive"))
      (node (ref "U1_4") (pin "10") (pinfunction "DVDD_10") (pintype "passive"))
      (node (ref "U1_4") (pin "11") (pinfunction "DVDD_11") (pintype "passive"))
      (node (ref "U1_4") (pin "13") (pinfunction "DVDD_13") (pintype "passive"))
      (node (ref "U1_4") (pin "14") (pinfunction "DVDD_14") (pintype "passive"))
      (node (ref "U1_4") (pin "15") (pinfunction "DVDD_15") (pintype "passive"))
      (node (ref "U1_4") (pin "18") (pinfunction "DVDD_18") (pintype "passive"))
      (node (ref "U1_4") (pin "19") (pinfunction "DVDD_19") (pintype "passive"))
      (node (ref "U1_4") (pin "20") (pinfunction "DVDD_20") (pintype "passive"))
      (node (ref "U1_4") (pin "21") (pinfunction "DVDD_21") (pintype "passive"))
      (node (ref "U1_4") (pin "22") (pinfunction "DVDD_22") (pintype "passive"))
      (node (ref "U1_4") (pin "25") (pinfunction "DVDD_25") (pintype "passive"))
      (node (ref "U1_4") (pin "26") (pinfunction "DVDD_26") (pintype "passive"))
      (node (ref "U1_4") (pin "28") (pinfunction "DVDD_28") (pintype "passive"))
      (node (ref "U1_4") (pin "29") (pinfunction "DVDD_29") (pintype "passive"))
      (node (ref "U1_4") (pin "3") (pinfunction "DVDD_3") (pintype "passive"))
      (node (ref "U1_4") (pin "30") (pinfunction "DVDD_30") (pintype "passive"))
      (node (ref "U1_4") (pin "31") (pinfunction "DVDD_31") (pintype "passive"))
      (node (ref "U1_4") (pin "32") (pinfunction "DVDD_32") (pintype "passive"))
      (node (ref "U1_4") (pin "33") (pinfunction "DVDD_33") (pintype "passive"))
      (node (ref "U1_4") (pin "34") (pinfunction "DVDD_34") (pintype "passive"))
      (node (ref "U1_4") (pin "39") (pinfunction "DVDD_39") (pintype "passive"))
      (node (ref "U1_4") (pin "4") (pinfunction "DVDD_4") (pintype "passive"))
      (node (ref "U1_4") (pin "40") (pinfunction "DVDD_40") (pintype "passive"))
      (node (ref "U1_4") (pin "41") (pinfunction "DVDD_41") (pintype "passive"))
      (node (ref "U1_4") (pin "42") (pinfunction "DVDD_42") (pintype "passive"))
      (node (ref "U1_4") (pin "45") (pinfunction "DVDD_45") (pintype "passive"))
      (node (ref "U1_4") (pin "46") (pinfunction "DVDD_46") (pintype "passive"))
      (node (ref "U1_4") (pin "47") (pinfunction "DVDD_47") (pintype "passive"))
      (node (ref "U1_4") (pin "48") (pinfunction "DVDD_48") (pintype "passive"))
      (node (ref "U1_5") (pin "10") (pinfunction "DVDD_10") (pintype "passive"))
      (node (ref "U1_5") (pin "11") (pinfunction "DVDD_11") (pintype "passive"))
      (node (ref "U1_5") (pin "13") (pinfunction "DVDD_13") (pintype "passive"))
      (node (ref "U1_5") (pin "14") (pinfunction "DVDD_14") (pintype "passive"))
      (node (ref "U1_5") (pin "15") (pinfunction "DVDD_15") (pintype "passive"))
      (node (ref "U1_5") (pin "18") (pinfunction "DVDD_18") (pintype "passive"))
      (node (ref "U1_5") (pin "19") (pinfunction "DVDD_19") (pintype "passive"))
      (node (ref "U1_5") (pin "20") (pinfunction "DVDD_20") (pintype "passive"))
      (node (ref "U1_5") (pin "21") (pinfunction "DVDD_21") (pintype "passive"))
      (node (ref "U1_5") (pin "22") (pinfunction "DVDD_22") (pintype "passive"))
      (node (ref "U1_5") (pin "25") (pinfunction "DVDD_25") (pintype "passive"))
      (node (ref "U1_5") (pin "26") (pinfunction "DVDD_26") (pintype "passive"))
      (node (ref "U1_5") (pin "28") (pinfunction "DVDD_28") (pintype "passive"))
      (node (ref "U1_5") (pin "29") (pinfunction "DVDD_29") (pintype "passive"))
      (node (ref "U1_5") (pin "3") (pinfunction "DVDD_3") (pintype "passive"))
      (node (ref "U1_5") (pin "30") (pinfunction "DVDD_30") (pintype "passive"))
      (node (ref "U1_5") (pin "31") (pinfunction "DVDD_31") (pintype "passive"))
      (node (ref "U1_5") (pin "32") (pinfunction "DVDD_32") (pintype "passive"))
      (node (ref "U1_5") (pin "33") (pinfunction "DVDD_33") (pintype "passive"))
      (node (ref "U1_5") (pin "34") (pinfunction "DVDD_34") (pintype "passive"))
      (node (ref "U1_5") (pin "39") (pinfunction "DVDD_39") (pintype "passive"))
      (node (ref "U1_5") (pin "4") (pinfunction "DVDD_4") (pintype "passive"))
      (node (ref "U1_5") (pin "40") (pinfunction "DVDD_40") (pintype "passive"))
      (node (ref "U1_5") (pin "41") (pinfunction "DVDD_41") (pintype "passive"))
      (node (ref "U1_5") (pin "42") (pinfunction "DVDD_42") (pintype "passive"))
      (node (ref "U1_5") (pin "45") (pinfunction "DVDD_45") (pintype "passive"))
      (node (ref "U1_5") (pin "46") (pinfunction "DVDD_46") (pintype "passive"))
      (node (ref "U1_5") (pin "47") (pinfunction "DVDD_47") (pintype "passive"))
      (node (ref "U1_5") (pin "48") (pinfunction "DVDD_48") (pintype "passive"))
      (node (ref "U1_6") (pin "10") (pinfunction "DVDD_10") (pintype "passive"))
      (node (ref "U1_6") (pin "11") (pinfunction "DVDD_11") (pintype "passive"))
      (node (ref "U1_6") (pin "13") (pinfunction "DVDD_13") (pintype "passive"))
      (node (ref "U1_6") (pin "14") (pinfunction "DVDD_14") (pintype "passive"))
      (node (ref "U1_6") (pin "15") (pinfunction "DVDD_15") (pintype "passive"))
      (node (ref "U1_6") (pin "18") (pinfunction "DVDD_18") (pintype "passive"))
      (node (ref "U1_6") (pin "19") (pinfunction "DVDD_19") (pintype "passive"))
      (node (ref "U1_6") (pin "20") (pinfunction "DVDD_20") (pintype "passive"))
      (node (ref "U1_6") (pin "21") (pinfunction "DVDD_21") (pintype "passive"))
      (node (ref "U1_6") (pin "22") (pinfunction "DVDD_22") (pintype "passive"))
      (node (ref "U1_6") (pin "25") (pinfunction "DVDD_25") (pintype "passive"))
      (node (ref "U1_6") (pin "26") (pinfunction "DVDD_26") (pintype "passive"))
      (node (ref "U1_6") (pin "28") (pinfunction "DVDD_28") (pintype "passive"))
      (node (ref "U1_6") (pin "29") (pinfunction "DVDD_29") (pintype "passive"))
      (node (ref "U1_6") (pin "3") (pinfunction "DVDD_3") (pintype "passive"))
      (node (ref "U1_6") (pin "30") (pinfunction "DVDD_30") (pintype "passive"))
      (node (ref "U1_6") (pin "31") (pinfunction "DVDD_31") (pintype "passive"))
      (node (ref "U1_6") (pin "32") (pinfunction "DVDD_32") (pintype "passive"))
      (node (ref "U1_6") (pin "33") (pinfunction "DVDD_33") (pintype "passive"))
      (node (ref "U1_6") (pin "34") (pinfunction "DVDD_34") (pintype "passive"))
      (node (ref "U1_6") (pin "39") (pinfunction "DVDD_39") (pintype "passive"))
      (node (ref "U1_6") (pin "4") (pinfunction "DVDD_4") (pintype "passive"))
      (node (ref "U1_6") (pin "40") (pinfunction "DVDD_40") (pintype "passive"))
      (node (ref "U1_6") (pin "41") (pinfunction "DVDD_41") (pintype "passive"))
      (node (ref "U1_6") (pin "42") (pinfunction "DVDD_42") (pintype "passive"))
      (node (ref "U1_6") (pin "45") (pinfunction "DVDD_45") (pintype "passive"))
      (node (ref "U1_6") (pin "46") (pinfunction "DVDD_46") (pintype "passive"))
      (node (ref "U1_6") (pin "47") (pinfunction "DVDD_47") (pintype "passive"))
      (node (ref "U1_6") (pin "48") (pinfunction "DVDD_48") (pintype "passive"))
      (node (ref "U1_7") (pin "10") (pinfunction "DVDD_10") (pintype "passive"))
      (node (ref "U1_7") (pin "11") (pinfunction "DVDD_11") (pintype "passive"))
      (node (ref "U1_7") (pin "13") (pinfunction "DVDD_13") (pintype "passive"))
      (node (ref "U1_7") (pin "14") (pinfunction "DVDD_14") (pintype "passive"))
      (node (ref "U1_7") (pin "15") (pinfunction "DVDD_15") (pintype "passive"))
      (node (ref "U1_7") (pin "18") (pinfunction "DVDD_18") (pintype "passive"))
      (node (ref "U1_7") (pin "19") (pinfunction "DVDD_19") (pintype "passive"))
      (node (ref "U1_7") (pin "20") (pinfunction "DVDD_20") (pintype "passive"))
      (node (ref "U1_7") (pin "21") (pinfunction "DVDD_21") (pintype "passive"))
      (node (ref "U1_7") (pin "22") (pinfunction "DVDD_22") (pintype "passive"))
      (node (ref "U1_7") (pin "25") (pinfunction "DVDD_25") (pintype "passive"))
      (node (ref "U1_7") (pin "26") (pinfunction "DVDD_26") (pintype "passive"))
      (node (ref "U1_7") (pin "28") (pinfunction "DVDD_28") (pintype "passive"))
      (node (ref "U1_7") (pin "29") (pinfunction "DVDD_29") (pintype "passive"))
      (node (ref "U1_7") (pin "3") (pinfunction "DVDD_3") (pintype "passive"))
      (node (ref "U1_7") (pin "30") (pinfunction "DVDD_30") (pintype "passive"))
      (node (ref "U1_7") (pin "31") (pinfunction "DVDD_31") (pintype "passive"))
      (node (ref "U1_7") (pin "32") (pinfunction "DVDD_32") (pintype "passive"))
      (node (ref "U1_7") (pin "33") (pinfunction "DVDD_33") (pintype "passive"))
      (node (ref "U1_7") (pin "34") (pinfunction "DVDD_34") (pintype "passive"))
      (node (ref "U1_7") (pin "39") (pinfunction "DVDD_39") (pintype "passive"))
      (node (ref "U1_7") (pin "4") (pinfunction "DVDD_4") (pintype "passive"))
      (node (ref "U1_7") (pin "40") (pinfunction "DVDD_40") (pintype "passive"))
      (node (ref "U1_7") (pin "41") (pinfunction "DVDD_41") (pintype "passive"))
      (node (ref "U1_7") (pin "42") (pinfunction "DVDD_42") (pintype "passive"))
      (node (ref "U1_7") (pin "45") (pinfunction "DVDD_45") (pintype "passive"))
      (node (ref "U1_7") (pin "46") (pinfunction "DVDD_46") (pintype "passive"))
      (node (ref "U1_7") (pin "47") (pinfunction "DVDD_47") (pintype "passive"))
      (node (ref "U1_7") (pin "48") (pinfunction "DVDD_48") (pintype "passive"))
      (node (ref "U1_8") (pin "10") (pinfunction "DVDD_10") (pintype "passive"))
      (node (ref "U1_8") (pin "11") (pinfunction "DVDD_11") (pintype "passive"))
      (node (ref "U1_8") (pin "13") (pinfunction "DVDD_13") (pintype "passive"))
      (node (ref "U1_8") (pin "14") (pinfunction "DVDD_14") (pintype "passive"))
      (node (ref "U1_8") (pin "15") (pinfunction "DVDD_15") (pintype "passive"))
      (node (ref "U1_8") (pin "18") (pinfunction "DVDD_18") (pintype "passive"))
      (node (ref "U1_8") (pin "19") (pinfunction "DVDD_19") (pintype "passive"))
      (node (ref "U1_8") (pin "20") (pinfunction "DVDD_20") (pintype "passive"))
      (node (ref "U1_8") (pin "21") (pinfunction "DVDD_21") (pintype "passive"))
      (node (ref "U1_8") (pin "22") (pinfunction "DVDD_22") (pintype "passive"))
      (node (ref "U1_8") (pin "25") (pinfunction "DVDD_25") (pintype "passive"))
      (node (ref "U1_8") (pin "26") (pinfunction "DVDD_26") (pintype "passive"))
      (node (ref "U1_8") (pin "28") (pinfunction "DVDD_28") (pintype "passive"))
      (node (ref "U1_8") (pin "29") (pinfunction "DVDD_29") (pintype "passive"))
      (node (ref "U1_8") (pin "3") (pinfunction "DVDD_3") (pintype "passive"))
      (node (ref "U1_8") (pin "30") (pinfunction "DVDD_30") (pintype "passive"))
      (node (ref "U1_8") (pin "31") (pinfunction "DVDD_31") (pintype "passive"))
      (node (ref "U1_8") (pin "32") (pinfunction "DVDD_32") (pintype "passive"))
      (node (ref "U1_8") (pin "33") (pinfunction "DVDD_33") (pintype "passive"))
      (node (ref "U1_8") (pin "34") (pinfunction "DVDD_34") (pintype "passive"))
      (node (ref "U1_8") (pin "39") (pinfunction "DVDD_39") (pintype "passive"))
      (node (ref "U1_8") (pin "4") (pinfunction "DVDD_4") (pintype "passive"))
      (node (ref "U1_8") (pin "40") (pinfunction "DVDD_40") (pintype "passive"))
      (node (ref "U1_8") (pin "41") (pinfunction "DVDD_41") (pintype "passive"))
      (node (ref "U1_8") (pin "42") (pinfunction "DVDD_42") (pintype "passive"))
      (node (ref "U1_8") (pin "45") (pinfunction "DVDD_45") (pintype "passive"))
      (node (ref "U1_8") (pin "46") (pinfunction "DVDD_46") (pintype "passive"))
      (node (ref "U1_8") (pin "47") (pinfunction "DVDD_47") (pintype "passive"))
      (node (ref "U1_8") (pin "48") (pinfunction "DVDD_48") (pintype "passive"))
      (node (ref "U1_9") (pin "10") (pinfunction "DVDD_10") (pintype "passive"))
      (node (ref "U1_9") (pin "11") (pinfunction "DVDD_11") (pintype "passive"))
      (node (ref "U1_9") (pin "13") (pinfunction "DVDD_13") (pintype "passive"))
      (node (ref "U1_9") (pin "14") (pinfunction "DVDD_14") (pintype "passive"))
      (node (ref "U1_9") (pin "15") (pinfunction "DVDD_15") (pintype "passive"))
      (node (ref "U1_9") (pin "18") (pinfunction "DVDD_18") (pintype "passive"))
      (node (ref "U1_9") (pin "19") (pinfunction "DVDD_19") (pintype "passive"))
      (node (ref "U1_9") (pin "20") (pinfunction "DVDD_20") (pintype "passive"))
      (node (ref "U1_9") (pin "21") (pinfunction "DVDD_21") (pintype "passive"))
      (node (ref "U1_9") (pin "22") (pinfunction "DVDD_22") (pintype "passive"))
      (node (ref "U1_9") (pin "25") (pinfunction "DVDD_25") (pintype "passive"))
      (node (ref "U1_9") (pin "26") (pinfunction "DVDD_26") (pintype "passive"))
      (node (ref "U1_9") (pin "28") (pinfunction "DVDD_28") (pintype "passive"))
      (node (ref "U1_9") (pin "29") (pinfunction "DVDD_29") (pintype "passive"))
      (node (ref "U1_9") (pin "3") (pinfunction "DVDD_3") (pintype "passive"))
      (node (ref "U1_9") (pin "30") (pinfunction "DVDD_30") (pintype "passive"))
      (node (ref "U1_9") (pin "31") (pinfunction "DVDD_31") (pintype "passive"))
      (node (ref "U1_9") (pin "32") (pinfunction "DVDD_32") (pintype "passive"))
      (node (ref "U1_9") (pin "33") (pinfunction "DVDD_33") (pintype "passive"))
      (node (ref "U1_9") (pin "34") (pinfunction "DVDD_34") (pintype "passive"))
      (node (ref "U1_9") (pin "39") (pinfunction "DVDD_39") (pintype "passive"))
      (node (ref "U1_9") (pin "4") (pinfunction "DVDD_4") (pintype "passive"))
      (node (ref "U1_9") (pin "40") (pinfunction "DVDD_40") (pintype "passive"))
      (node (ref "U1_9") (pin "41") (pinfunction "DVDD_41") (pintype "passive"))
      (node (ref "U1_9") (pin "42") (pinfunction "DVDD_42") (pintype "passive"))
      (node (ref "U1_9") (pin "45") (pinfunction "DVDD_45") (pintype "passive"))
      (node (ref "U1_9") (pin "46") (pinfunction "DVDD_46") (pintype "passive"))
      (node (ref "U1_9") (pin "47") (pinfunction "DVDD_47") (pintype "passive"))
      (node (ref "U1_9") (pin "48") (pinfunction "DVDD_48") (pintype "passive"))
    )
    (net (code "2") (name "/0.9V") (class "Default")
      (node (ref "C26") (pin "1") (pinfunction "1_1") (pintype "passive"))
      (node (ref "R29") (pin "2") (pinfunction "2_2") (pintype "passive"))
      (node (ref "R31") (pin "2") (pinfunction "2_2") (pintype "passive"))
      (node (ref "U1_1") (pin "7") (pinfunction "VDD_PLL_7") (pintype "passive"))
      (node (ref "U1_10") (pin "7") (pinfunction "VDD_PLL_7") (pintype "passive"))
      (node (ref "U1_11") (pin "7") (pinfunction "VDD_PLL_7") (pintype "passive"))
      (node (ref "U1_12") (pin "7") (pinfunction "VDD_PLL_7") (pintype "passive"))
      (node (ref "U1_13") (pin "7") (pinfunction "VDD_PLL_7") (pintype "passive"))
      (node (ref "U1_14") (pin "7") (pinfunction "VDD_PLL_7") (pintype "passive"))
      (node (ref "U1_15") (pin "7") (pinfunction "VDD_PLL_7") (pintype "passive"))
      (node (ref "U1_16") (pin "7") (pinfunction "VDD_PLL_7") (pintype "passive"))
      (node (ref "U1_2") (pin "7") (pinfunction "VDD_PLL_7") (pintype "passive"))
      (node (ref "U1_3") (pin "7") (pinfunction "VDD_PLL_7") (pintype "passive"))
      (node (ref "U1_4") (pin "7") (pinfunction "VDD_PLL_7") (pintype "passive"))
      (node (ref "U1_5") (pin "7") (pinfunction "VDD_PLL_7") (pintype "passive"))
      (node (ref "U1_6") (pin "7") (pinfunction "VDD_PLL_7") (pintype "passive"))
      (node (ref "U1_7") (pin "7") (pinfunction "VDD_PLL_7") (pintype "passive"))
      (node (ref "U1_8") (pin "7") (pinfunction "VDD_PLL_7") (pintype "passive"))
      (node (ref "U1_9") (pin "7") (pinfunction "VDD_PLL_7") (pintype "passive"))
    )
    (net (code "3") (name "/1.8V") (class "Default")
      (node (ref "C25") (pin "2") (pinfunction "2_2") (pintype "passive"))
      (node (ref "C5_1") (pin "2") (pinfunction "2_2") (pintype "passive"))
      (node (ref "C5_10") (pin "2") (pinfunction "2_2") (pintype "passive"))
      (node (ref "C5_11") (pin "2") (pinfunction "2_2") (pintype "passive"))
      (node (ref "C5_12") (pin "2") (pinfunction "2_2") (pintype "passive"))
      (node (ref "C5_13") (pin "2") (pinfunction "2_2") (pintype "passive"))
      (node (ref "C5_14") (pin "2") (pinfunction "2_2") (pintype "passive"))
      (node (ref "C5_15") (pin "2") (pinfunction "2_2") (pintype "passive"))
      (node (ref "C5_16") (pin "2") (pinfunction "2_2") (pintype "passive"))
      (node (ref "C5_2") (pin "2") (pinfunction "2_2") (pintype "passive"))
      (node (ref "C5_3") (pin "2") (pinfunction "2_2") (pintype "passive"))
      (node (ref "C5_4") (pin "2") (pinfunction "2_2") (pintype "passive"))
      (node (ref "C5_5") (pin "2") (pinfunction "2_2") (pintype "passive"))
      (node (ref "C5_6") (pin "2") (pinfunction "2_2") (pintype "passive"))
      (node (ref "C5_7") (pin "2") (pinfunction "2_2") (pintype "passive"))
      (node (ref "C5_8") (pin "2") (pinfunction "2_2") (pintype "passive"))
      (node (ref "C5_9") (pin "2") (pinfunction "2_2") (pintype "passive"))
      (node (ref "C8_1") (pin "1") (pinfunction "1_1") (pintype "passive"))
      (node (ref "C8_10") (pin "1") (pinfunction "1_1") (pintype "passive"))
      (node (ref "C8_11") (pin "1") (pinfunction "1_1") (pintype "passive"))
      (node (ref "C8_12") (pin "1") (pinfunction "1_1") (pintype "passive"))
      (node (ref "C8_13") (pin "1") (pinfunction "1_1") (pintype "passive"))
      (node (ref "C8_14") (pin "1") (pinfunction "1_1") (pintype "passive"))
      (node (ref "C8_15") (pin "1") (pinfunction "1_1") (pintype "passive"))
      (node (ref "C8_16") (pin "1") (pinfunction "1_1") (pintype "passive"))
      (node (ref "C8_2") (pin "1") (pinfunction "1_1") (pintype "passive"))
      (node (ref "C8_3") (pin "1") (pinfunction "1_1") (pintype "passive"))
      (node (ref "C8_4") (pin "1") (pinfunction "1_1") (pintype "passive"))
      (node (ref "C8_5") (pin "1") (pinfunction "1_1") (pintype "passive"))
      (node (ref "C8_6") (pin "1") (pinfunction "1_1") (pintype "passive"))
      (node (ref "C8_7") (pin "1") (pinfunction "1_1") (pintype "passive"))
      (node (ref "C8_8") (pin "1") (pinfunction "1_1") (pintype "passive"))
      (node (ref "C8_9") (pin "1") (pinfunction "1_1") (pintype "passive"))
      (node (ref "R1_1") (pin "1") (pinfunction "1_1") (pintype "passive"))
      (node (ref "R1_10") (pin "1") (pinfunction "1_1") (pintype "passive"))
      (node (ref "R1_11") (pin "1") (pinfunction "1_1") (pintype "passive"))
      (node (ref "R1_12") (pin "1") (pinfunction "1_1") (pintype "passive"))
      (node (ref "R1_13") (pin "1") (pinfunction "1_1") (pintype "passive"))
      (node (ref "R1_14") (pin "1") (pinfunction "1_1") (pintype "passive"))
      (node (ref "R1_15") (pin "1") (pinfunction "1_1") (pintype "passive"))
      (node (ref "R1_16") (pin "1") (pinfunction "1_1") (pintype "passive"))
      (node (ref "R1_2") (pin "1") (pinfunction "1_1") (pintype "passive"))
      (node (ref "R1_3") (pin "1") (pinfunction "1_1") (pintype "passive"))
      (node (ref "R1_4") (pin "1") (pinfunction "1_1") (pintype "passive"))
      (node (ref "R1_5") (pin "1") (pinfunction "1_1") (pintype "passive"))
      (node (ref "R1_6") (pin "1") (pinfunction "1_1") (pintype "passive"))
      (node (ref "R1_7") (pin "1") (pinfunction "1_1") (pintype "passive"))
      (node (ref "R1_8") (pin "1") (pinfunction "1_1") (pintype "passive"))
      (node (ref "R1_9") (pin "1") (pinfunction "1_1") (pintype "passive"))
      (node (ref "R24") (pin "2") (pinfunction "2_2") (pintype "passive"))
      (node (ref "R29") (pin "1") (pinfunction "1_1") (pintype "passive"))
      (node (ref "R32") (pin "2") (pinfunction "2_2") (pintype "passive"))
      (node (ref "U1_1") (pin "24") (pinfunction "OVDD1_24") (pintype "passive"))
      (node (ref "U1_1") (pin "37") (pinfunction "OVDD0_37") (pintype "passive"))
      (node (ref "U1_1") (pin "6") (pinfunction "VDDA_PLL_6") (pintype "passive"))
      (node (ref "U1_10") (pin "24") (pinfunction "OVDD1_24") (pintype "passive"))
      (node (ref "U1_10") (pin "37") (pinfunction "OVDD0_37") (pintype "passive"))
      (node (ref "U1_10") (pin "6") (pinfunction "VDDA_PLL_6") (pintype "passive"))
      (node (ref "U1_11") (pin "24") (pinfunction "OVDD1_24") (pintype "passive"))
      (node (ref "U1_11") (pin "37") (pinfunction "OVDD0_37") (pintype "passive"))
      (node (ref "U1_11") (pin "6") (pinfunction "VDDA_PLL_6") (pintype "passive"))
      (node (ref "U1_12") (pin "24") (pinfunction "OVDD1_24") (pintype "passive"))
      (node (ref "U1_12") (pin "37") (pinfunction "OVDD0_37") (pintype "passive"))
      (node (ref "U1_12") (pin "6") (pinfunction "VDDA_PLL_6") (pintype "passive"))
      (node (ref "U1_13") (pin "24") (pinfunction "OVDD1_24") (pintype "passive"))
      (node (ref "U1_13") (pin "37") (pinfunction "OVDD0_37") (pintype "passive"))
      (node (ref "U1_13") (pin "6") (pinfunction "VDDA_PLL_6") (pintype "passive"))
      (node (ref "U1_14") (pin "24") (pinfunction "OVDD1_24") (pintype "passive"))
      (node (ref "U1_14") (pin "37") (pinfunction "OVDD0_37") (pintype "passive"))
      (node (ref "U1_14") (pin "6") (pinfunction "VDDA_PLL_6") (pintype "passive"))
      (node (ref "U1_15") (pin "24") (pinfunction "OVDD1_24") (pintype "passive"))
      (node (ref "U1_15") (pin "37") (pinfunction "OVDD0_37") (pintype "passive"))
      (node (ref "U1_15") (pin "6") (pinfunction "VDDA_PLL_6") (pintype "passive"))
      (node (ref "U1_16") (pin "24") (pinfunction "OVDD1_24") (pintype "passive"))
      (node (ref "U1_16") (pin "37") (pinfunction "OVDD0_37") (pintype "passive"))
      (node (ref "U1_16") (pin "6") (pinfunction "VDDA_PLL_6") (pintype "passive"))
      (node (ref "U1_2") (pin "24") (pinfunction "OVDD1_24") (pintype "passive"))
      (node (ref "U1_2") (pin "37") (pinfunction "OVDD0_37") (pintype "passive"))
      (node (ref "U1_2") (pin "6") (pinfunction "VDDA_PLL_6") (pintype "passive"))
      (node (ref "U1_3") (pin "24") (pinfunction "OVDD1_24") (pintype "passive"))
      (node (ref "U1_3") (pin "37") (pinfunction "OVDD0_37") (pintype "passive"))
      (node (ref "U1_3") (pin "6") (pinfunction "VDDA_PLL_6") (pintype "passive"))
      (node (ref "U1_4") (pin "24") (pinfunction "OVDD1_24") (pintype "passive"))
      (node (ref "U1_4") (pin "37") (pinfunction "OVDD0_37") (pintype "passive"))
      (node (ref "U1_4") (pin "6") (pinfunction "VDDA_PLL_6") (pintype "passive"))
      (node (ref "U1_5") (pin "24") (pinfunction "OVDD1_24") (pintype "passive"))
      (node (ref "U1_5") (pin "37") (pinfunction "OVDD0_37") (pintype "passive"))
      (node (ref "U1_5") (pin "6") (pinfunction "VDDA_PLL_6") (pintype "passive"))
      (node (ref "U1_6") (pin "24") (pinfunction "OVDD1_24") (pintype "passive"))
      (node (ref "U1_6") (pin "37") (pinfunction "OVDD0_37") (pintype "passive"))
      (node (ref "U1_6") (pin "6") (pinfunction "VDDA_PLL_6") (pintype "passive"))
      (node (ref "U1_7") (pin "24") (pinfunction "OVDD1_24") (pintype "passive"))
      (node (ref "U1_7") (pin "37") (pinfunction "OVDD0_37") (pintype "passive"))
      (node (ref "U1_7") (pin "6") (pinfunction "VDDA_PLL_6") (pintype "passive"))
      (node (ref "U1_8") (pin "24") (pinfunction "OVDD1_24") (pintype "passive"))
      (node (ref "U1_8") (pin "37") (pinfunction "OVDD0_37") (pintype "passive"))
      (node (ref "U1_8") (pin "6") (pinfunction "VDDA_PLL_6") (pintype "passive"))
      (node (ref "U1_9") (pin "24") (pinfunction "OVDD1_24") (pintype "passive"))
      (node (ref "U1_9") (pin "37") (pinfunction "OVDD0_37") (pintype "passive"))
      (node (ref "U1_9") (pin "6") (pinfunction "VDDA_PLL_6") (pintype "passive"))
      (node (ref "U6") (pin "1") (pinfunction "OUTPUT_1") (pintype "passive"))
    )
    (net (code "4") (name "/3.3V") (class "Default")
      (node (ref "C10") (pin "1") (pinfunction "1_1") (pintype "passive"))
      (node (ref "C11") (pin "1") (pinfunction "1_1") (pintype "passive"))
      (node (ref "C16") (pin "1") (pinfunction "1_1") (pintype "passive"))
      (node (ref "C17") (pin "1") (pinfunction "1_1") (pintype "passive"))
      (node (ref "C4") (pin "1") (pinfunction "1_1") (pintype "passive"))
      (node (ref "C8") (pin "1") (pinfunction "1_1") (pintype "passive"))
      (node (ref "C9") (pin "1") (pinfunction "1_1") (pintype "passive"))
      (node (ref "J1") (pin "2") (pinfunction "2_2") (pintype "passive"))
      (node (ref "R1") (pin "2") (pinfunction "2_2") (pintype "passive"))
      (node (ref "R17") (pin "1") (pinfunction "1_1") (pintype "passive"))
      (node (ref "R2") (pin "2") (pinfunction "2_2") (pintype "passive"))
      (node (ref "R22") (pin "2") (pinfunction "2_2") (pintype "passive"))
      (node (ref "R27") (pin "1") (pinfunction "1_1") (pintype "passive"))
      (node (ref "U1") (pin "10") (pinfunction "VDD_10") (pintype "passive"))
      (node (ref "U1") (pin "19") (pinfunction "AVDD_19") (pintype "passive"))
      (node (ref "U1") (pin "26") (pinfunction "VDD_26") (pintype "passive"))
      (node (ref "U1") (pin "35") (pinfunction "VUSB3V3_35") (pintype "passive"))
      (node (ref "U1") (pin "38") (pinfunction "VDD_38") (pintype "passive"))
      (node (ref "U1") (pin "57") (pinfunction "VDD_57") (pintype "passive"))
      (node (ref "U3") (pin "4") (pinfunction "NC_4") (pintype "passive"))
      (node (ref "U3") (pin "5") (pinfunction "Vout_5") (pintype "passive"))
      (node (ref "U7") (pin "1") (pinfunction "OUTPUT_1") (pintype "passive"))
    )
    (net (code "5") (name "/5.0V") (class "Default")
      (node (ref "C14") (pin "1") (pinfunction "1_1") (pintype "passive"))
      (node (ref "C1P_1") (pin "2") (pinfunction "2_2") (pintype "passive"))
      (node (ref "C1P_2") (pin "2") (pinfunction "2_2") (pintype "passive"))
      (node (ref "C1P_3") (pin "2") (pinfunction "2_2") (pintype "passive"))
      (node (ref "D1P_1") (pin "1") (pinfunction "A1_1") (pintype "passive"))
      (node (ref "D1P_1") (pin "2") (pinfunction "A2_2") (pintype "passive"))
      (node (ref "D1P_2") (pin "1") (pinfunction "A1_1") (pintype "passive"))
      (node (ref "D1P_2") (pin "2") (pinfunction "A2_2") (pintype "passive"))
      (node (ref "D1P_3") (pin "1") (pinfunction "A1_1") (pintype "passive"))
      (node (ref "D1P_3") (pin "2") (pinfunction "A2_2") (pintype "passive"))
      (node (ref "D7") (pin "1") (pinfunction "C_1") (pintype "passive"))
      (node (ref "D8") (pin "2") (pinfunction "A_2") (pintype "passive"))
      (node (ref "J3") (pin "1") (pinfunction "1_1") (pintype "passive"))
      (node (ref "R26") (pin "1") (pinfunction "1_1") (pintype "passive"))
      (node (ref "U1P_1") (pin "7") (pinfunction "VCC_7") (pintype "passive"))
      (node (ref "U1P_2") (pin "7") (pinfunction "VCC_7") (pintype "passive"))
      (node (ref "U1P_3") (pin "7") (pinfunction "VCC_7") (pintype "passive"))
      (node (ref "U2") (pin "1") (pinfunction "OUTPUT_1") (pintype "passive"))
      (node (ref "U4") (pin "3") (pinfunction "Vin_3") (pintype "passive"))
      (node (ref "U5") (pin "3") (pinfunction "Vin_3") (pintype "passive"))
    )
    (net (code "6") (name "/12V") (class "Default")
      (node (ref "C4P_1") (pin "1") (pinfunction "1_1") (pintype "passive"))
      (node (ref "C4P_2") (pin "1") (pinfunction "1_1") (pintype "passive"))
      (node (ref "C4P_3") (pin "1") (pinfunction "1_1") (pintype "passive"))
      (node (ref "C5P_1") (pin "1") (pinfunction "1_1") (pintype "passive"))
      (node (ref "C5P_2") (pin "1") (pinfunction "1_1") (pintype "passive"))
      (node (ref "C5P_3") (pin "1") (pinfunction "1_1") (pintype "passive"))
      (node (ref "D10") (pin "1") (pinfunction "C_1") (pintype "passive"))
      (node (ref "D9") (pin "2") (pinfunction "A_2") (pintype "passive"))
      (node (ref "J3") (pin "3") (pinfunction "3_3") (pintype "passive"))
      (node (ref "J4") (pin "2") (pinfunction "2_2") (pintype "passive"))
      (node (ref "J4") (pin "4") (pinfunction "4_4") (pintype "passive"))
      (node (ref "J4") (pin "6") (pinfunction "6_6") (pintype "passive"))
      (node (ref "Q1P_1") (pin "5") (pinfunction "D_5") (pintype "passive"))
      (node (ref "Q1P_1") (pin "6") (pinfunction "D_6") (pintype "passive"))
      (node (ref "Q1P_1") (pin "7") (pinfunction "D_7") (pintype "passive"))
      (node (ref "Q1P_1") (pin "8") (pinfunction "D_8") (pintype "passive"))
      (node (ref "Q1P_2") (pin "5") (pinfunction "D_5") (pintype "passive"))
      (node (ref "Q1P_2") (pin "6") (pinfunction "D_6") (pintype "passive"))
      (node (ref "Q1P_2") (pin "7") (pinfunction "D_7") (pintype "passive"))
      (node (ref "Q1P_2") (pin "8") (pinfunction "D_8") (pintype "passive"))
      (node (ref "Q1P_3") (pin "5") (pinfunction "D_5") (pintype "passive"))
      (node (ref "Q1P_3") (pin "6") (pinfunction "D_6") (pintype "passive"))
      (node (ref "Q1P_3") (pin "7") (pinfunction "D_7") (pintype "passive"))
      (node (ref "Q1P_3") (pin "8") (pinfunction "D_8") (pintype "passive"))
      (node (ref "R15") (pin "1") (pinfunction "1_1") (pintype "passive"))
      (node (ref "R28") (pin "2") (pinfunction "2_2") (pintype "passive"))
    )
    (net (code "7") (name "/ASIC_RESET") (class "Default")
      (node (ref "C10_1") (pin "1") (pinfunction "1_1") (pintype "passive"))
      (node (ref "C10_10") (pin "1") (pinfunction "1_1") (pintype "passive"))
      (node (ref "C10_11") (pin "1") (pinfunction "1_1") (pintype "passive"))
      (node (ref "C10_12") (pin "1") (pinfunction "1_1") (pintype "passive"))
      (node (ref "C10_13") (pin "1") (pinfunction "1_1") (pintype "passive"))
      (node (ref "C10_14") (pin "1") (pinfunction "1_1") (pintype "passive"))
      (node (ref "C10_15") (pin "1") (pinfunction "1_1") (pintype "passive"))
      (node (ref "C10_16") (pin "1") (pinfunction "1_1") (pintype "passive"))
      (node (ref "C10_2") (pin "1") (pinfunction "1_1") (pintype "passive"))
      (node (ref "C10_3") (pin "1") (pinfunction "1_1") (pintype "passive"))
      (node (ref "C10_4") (pin "1") (pinfunction "1_1") (pintype "passive"))
      (node (ref "C10_5") (pin "1") (pinfunction "1_1") (pintype "passive"))
      (node (ref "C10_6") (pin "1") (pinfunction "1_1") (pintype "passive"))
      (node (ref "C10_7") (pin "1") (pinfunction "1_1") (pintype "passive"))
      (node (ref "C10_8") (pin "1") (pinfunction "1_1") (pintype "passive"))
      (node (ref "C10_9") (pin "1") (pinfunction "1_1") (pintype "passive"))
      (node (ref "R13") (pin "2") (pinfunction "2_2") (pintype "passive"))
      (node (ref "R1_1") (pin "2") (pinfunction "2_2") (pintype "passive"))
      (node (ref "R1_10") (pin "2") (pinfunction "2_2") (pintype "passive"))
      (node (ref "R1_11") (pin "2") (pinfunction "2_2") (pintype "passive"))
      (node (ref "R1_12") (pin "2") (pinfunction "2_2") (pintype "passive"))
      (node (ref "R1_13") (pin "2") (pinfunction "2_2") (pintype "passive"))
      (node (ref "R1_14") (pin "2") (pinfunction "2_2") (pintype "passive"))
      (node (ref "R1_15") (pin "2") (pinfunction "2_2") (pintype "passive"))
      (node (ref "R1_16") (pin "2") (pinfunction "2_2") (pintype "passive"))
      (node (ref "R1_2") (pin "2") (pinfunction "2_2") (pintype "passive"))
      (node (ref "R1_3") (pin "2") (pinfunction "2_2") (pintype "passive"))
      (node (ref "R1_4") (pin "2") (pinfunction "2_2") (pintype "passive"))
      (node (ref "R1_5") (pin "2") (pinfunction "2_2") (pintype "passive"))
      (node (ref "R1_6") (pin "2") (pinfunction "2_2") (pintype "passive"))
      (node (ref "R1_7") (pin "2") (pinfunction "2_2") (pintype "passive"))
      (node (ref "R1_8") (pin "2") (pinfunction "2_2") (pintype "passive"))
      (node (ref "R1_9") (pin "2") (pinfunction "2_2") (pintype "passive"))
      (node (ref "R3") (pin "1") (pinfunction "1_1") (pintype "passive"))
      (node (ref "U1_1") (pin "44") (pinfunction "RSTN_44") (pintype "passive"))
      (node (ref "U1_10") (pin "44") (pinfunction "RSTN_44") (pintype "passive"))
      (node (ref "U1_11") (pin "44") (pinfunction "RSTN_44") (pintype "passive"))
      (node (ref "U1_12") (pin "44") (pinfunction "RSTN_44") (pintype "passive"))
      (node (ref "U1_13") (pin "44") (pinfunction "RSTN_44") (pintype "passive"))
      (node (ref "U1_14") (pin "44") (pinfunction "RSTN_44") (pintype "passive"))
      (node (ref "U1_15") (pin "44") (pinfunction "RSTN_44") (pintype "passive"))
      (node (ref "U1_16") (pin "44") (pinfunction "RSTN_44") (pintype "passive"))
      (node (ref "U1_2") (pin "44") (pinfunction "RSTN_44") (pintype "passive"))
      (node (ref "U1_3") (pin "44") (pinfunction "RSTN_44") (pintype "passive"))
      (node (ref "U1_4") (pin "44") (pinfunction "RSTN_44") (pintype "passive"))
      (node (ref "U1_5") (pin "44") (pinfunction "RSTN_44") (pintype "passive"))
      (node (ref "U1_6") (pin "44") (pinfunction "RSTN_44") (pintype "passive"))
      (node (ref "U1_7") (pin "44") (pinfunction "RSTN_44") (pintype "passive"))
      (node (ref "U1_8") (pin "44") (pinfunction "RSTN_44") (pintype "passive"))
      (node (ref "U1_9") (pin "44") (pinfunction "RSTN_44") (pintype "passive"))
    )
    (net (code "8") (name "/ASIC_RESET_MCU") (class "Default")
      (node (ref "R3") (pin "2") (pinfunction "2_2") (pintype "passive"))
      (node (ref "U1") (pin "3") (pinfunction "AN31/PWM4H/PMD7/RP87/RE7_3") (pintype "passive"))
    )
    (net (code "9") (name "/BOOT1") (class "Default")
      (node (ref "C3P_1") (pin "1") (pinfunction "1_1") (pintype "passive"))
      (node (ref "D1P_1") (pin "3") (pinfunction "CC_3") (pintype "passive"))
      (node (ref "U1P_1") (pin "8") (pinfunction "BOOT_8") (pintype "passive"))
    )
    (net (code "10") (name "/BOOT2") (class "Default")
      (node (ref "C3P_2") (pin "1") (pinfunction "1_1") (pintype "passive"))
      (node (ref "D1P_2") (pin "3") (pinfunction "CC_3") (pintype "passive"))
      (node (ref "U1P_2") (pin "8") (pinfunction "BOOT_8") (pintype "passive"))
    )
    (net (code "11") (name "/BOOT3") (class "Default")
      (node (ref "C3P_3") (pin "1") (pinfunction "1_1") (pintype "passive"))
      (node (ref "D1P_3") (pin "3") (pinfunction "CC_3") (pintype "passive"))
      (node (ref "U1P_3") (pin "8") (pinfunction "BOOT_8") (pintype "passive"))
    )
    (net (code "12") (name "/CONFIG_N1") (class "Default")
      (node (ref "R6") (pin "1") (pinfunction "1_1") (pintype "passive"))
      (node (ref "R7") (pin "2") (pinfunction "2_2") (pintype "passive"))
      (node (ref "U1_1") (pin "2") (pinfunction "CONFIG_NI_2") (pintype "passive"))
    )
    (net (code "13") (name "/CONFIG_N1_MCU") (class "Default")
      (node (ref "R6") (pin "2") (pinfunction "2_2") (pintype "passive"))
      (node (ref "U1") (pin "42") (pinfunction "RTCC/DMLN/RPI72/RD8_42") (pintype "passive"))
    )
    (net (code "14") (name "/CONFIG_N2") (class "Default")
      (node (ref "U1_1") (pin "35") (pinfunction "CONFIG_NO_35") (pintype "passive"))
      (node (ref "U1_2") (pin "2") (pinfunction "CONFIG_NI_2") (pintype "passive"))
    )
    (net (code "15") (name "/CONFIG_N3") (class "Default")
      (node (ref "U1_2") (pin "35") (pinfunction "CONFIG_NO_35") (pintype "passive"))
      (node (ref "U1_3") (pin "2") (pinfunction "CONFIG_NI_2") (pintype "passive"))
    )
    (net (code "16") (name "/CONFIG_N4") (class "Default")
      (node (ref "U1_3") (pin "35") (pinfunction "CONFIG_NO_35") (pintype "passive"))
      (node (ref "U1_4") (pin "2") (pinfunction "CONFIG_NI_2") (pintype "passive"))
    )
    (net (code "17") (name "/CONFIG_N5") (class "Default")
      (node (ref "U1_4") (pin "35") (pinfunction "CONFIG_NO_35") (pintype "passive"))
      (node (ref "U1_5") (pin "2") (pinfunction "CONFIG_NI_2") (pintype "passive"))
    )
    (net (code "18") (name "/CONFIG_N6") (class "Default")
      (node (ref "U1_5") (pin "35") (pinfunction "CONFIG_NO_35") (pintype "passive"))
      (node (ref "U1_6") (pin "2") (pinfunction "CONFIG_NI_2") (pintype "passive"))
    )
    (net (code "19") (name "/CONFIG_N7") (class "Default")
      (node (ref "U1_6") (pin "35") (pinfunction "CONFIG_NO_35") (pintype "passive"))
      (node (ref "U1_7") (pin "2") (pinfunction "CONFIG_NI_2") (pintype "passive"))
    )
    (net (code "20") (name "/CONFIG_N8") (class "Default")
      (node (ref "U1_7") (pin "35") (pinfunction "CONFIG_NO_35") (pintype "passive"))
      (node (ref "U1_8") (pin "2") (pinfunction "CONFIG_NI_2") (pintype "passive"))
    )
    (net (code "21") (name "/CONFIG_N9") (class "Default")
      (node (ref "U1_8") (pin "35") (pinfunction "CONFIG_NO_35") (pintype "passive"))
      (node (ref "U1_9") (pin "2") (pinfunction "CONFIG_NI_2") (pintype "passive"))
    )
    (net (code "22") (name "/CONFIG_N10") (class "Default")
      (node (ref "U1_10") (pin "2") (pinfunction "CONFIG_NI_2") (pintype "passive"))
      (node (ref "U1_9") (pin "35") (pinfunction "CONFIG_NO_35") (pintype "passive"))
    )
    (net (code "23") (name "/CONFIG_N11") (class "Default")
      (node (ref "U1_10") (pin "35") (pinfunction "CONFIG_NO_35") (pintype "passive"))
      (node (ref "U1_11") (pin "2") (pinfunction "CONFIG_NI_2") (pintype "passive"))
    )
    (net (code "24") (name "/CONFIG_N12") (class "Default")
      (node (ref "U1_11") (pin "35") (pinfunction "CONFIG_NO_35") (pintype "passive"))
      (node (ref "U1_12") (pin "2") (pinfunction "CONFIG_NI_2") (pintype "passive"))
    )
    (net (code "25") (name "/CONFIG_N13") (class "Default")
      (node (ref "U1_12") (pin "35") (pinfunction "CONFIG_NO_35") (pintype "passive"))
      (node (ref "U1_13") (pin "2") (pinfunction "CONFIG_NI_2") (pintype "passive"))
    )
    (net (code "26") (name "/CONFIG_N14") (class "Default")
      (node (ref "U1_13") (pin "35") (pinfunction "CONFIG_NO_35") (pintype "passive"))
      (node (ref "U1_14") (pin "2") (pinfunction "CONFIG_NI_2") (pintype "passive"))
    )
    (net (code "27") (name "/CONFIG_N15") (class "Default")
      (node (ref "U1_14") (pin "35") (pinfunction "CONFIG_NO_35") (pintype "passive"))
      (node (ref "U1_15") (pin "2") (pinfunction "CONFIG_NI_2") (pintype "passive"))
    )
    (net (code "28") (name "/CONFIG_N16") (class "Default")
      (node (ref "U1_15") (pin "35") (pinfunction "CONFIG_NO_35") (pintype "passive"))
      (node (ref "U1_16") (pin "2") (pinfunction "CONFIG_NI_2") (pintype "passive"))
    )
    (net (code "29") (name "/CONFIG_N17") (class "Default")
      (node (ref "U1_16") (pin "35") (pinfunction "CONFIG_NO_35") (pintype "passive"))
    )
    (net (code "30") (name "/CONFIG_P1") (class "Default")
      (node (ref "R4") (pin "1") (pinfunction "1_1") (pintype "passive"))
      (node (ref "R5") (pin "2") (pinfunction "2_2") (pintype "passive"))
      (node (ref "U1_1") (pin "1") (pinfunction "CONFIG_PI_1") (pintype "passive"))
    )
    (net (code "31") (name "/CONFIG_P1_MCU") (class "Default")
      (node (ref "R4") (pin "2") (pinfunction "2_2") (pintype "passive"))
      (node (ref "U1") (pin "43") (pinfunction "ASDA1/DPLN/RPI73/RD9_43") (pintype "passive"))
    )
    (net (code "32") (name "/CONFIG_P2") (class "Default")
      (node (ref "U1_1") (pin "36") (pinfunction "CONFIG_PO_36") (pintype "passive"))
      (node (ref "U1_2") (pin "1") (pinfunction "CONFIG_PI_1") (pintype "passive"))
    )
    (net (code "33") (name "/CONFIG_P3") (class "Default")
      (node (ref "U1_2") (pin "36") (pinfunction "CONFIG_PO_36") (pintype "passive"))
      (node (ref "U1_3") (pin "1") (pinfunction "CONFIG_PI_1") (pintype "passive"))
    )
    (net (code "34") (name "/CONFIG_P4") (class "Default")
      (node (ref "U1_3") (pin "36") (pinfunction "CONFIG_PO_36") (pintype "passive"))
      (node (ref "U1_4") (pin "1") (pinfunction "CONFIG_PI_1") (pintype "passive"))
    )
    (net (code "35") (name "/CONFIG_P5") (class "Default")
      (node (ref "U1_4") (pin "36") (pinfunction "CONFIG_PO_36") (pintype "passive"))
      (node (ref "U1_5") (pin "1") (pinfunction "CONFIG_PI_1") (pintype "passive"))
    )
    (net (code "36") (name "/CONFIG_P6") (class "Default")
      (node (ref "U1_5") (pin "36") (pinfunction "CONFIG_PO_36") (pintype "passive"))
      (node (ref "U1_6") (pin "1") (pinfunction "CONFIG_PI_1") (pintype "passive"))
    )
    (net (code "37") (name "/CONFIG_P7") (class "Default")
      (node (ref "U1_6") (pin "36") (pinfunction "CONFIG_PO_36") (pintype "passive"))
      (node (ref "U1_7") (pin "1") (pinfunction "CONFIG_PI_1") (pintype "passive"))
    )
    (net (code "38") (name "/CONFIG_P8") (class "Default")
      (node (ref "U1_7") (pin "36") (pinfunction "CONFIG_PO_36") (pintype "passive"))
      (node (ref "U1_8") (pin "1") (pinfunction "CONFIG_PI_1") (pintype "passive"))
    )
    (net (code "39") (name "/CONFIG_P9") (class "Default")
      (node (ref "U1_8") (pin "36") (pinfunction "CONFIG_PO_36") (pintype "passive"))
      (node (ref "U1_9") (pin "1") (pinfunction "CONFIG_PI_1") (pintype "passive"))
    )
    (net (code "40") (name "/CONFIG_P10") (class "Default")
      (node (ref "U1_10") (pin "1") (pinfunction "CONFIG_PI_1") (pintype "passive"))
      (node (ref "U1_9") (pin "36") (pinfunction "CONFIG_PO_36") (pintype "passive"))
    )
    (net (code "41") (name "/CONFIG_P11") (class "Default")
      (node (ref "U1_10") (pin "36") (pinfunction "CONFIG_PO_36") (pintype "passive"))
      (node (ref "U1_11") (pin "1") (pinfunction "CONFIG_PI_1") (pintype "passive"))
    )
    (net (code "42") (name "/CONFIG_P12") (class "Default")
      (node (ref "U1_11") (pin "36") (pinfunction "CONFIG_PO_36") (pintype "passive"))
      (node (ref "U1_12") (pin "1") (pinfunction "CONFIG_PI_1") (pintype "passive"))
    )
    (net (code "43") (name "/CONFIG_P13") (class "Default")
      (node (ref "U1_12") (pin "36") (pinfunction "CONFIG_PO_36") (pintype "passive"))
      (node (ref "U1_13") (pin "1") (pinfunction "CONFIG_PI_1") (pintype "passive"))
    )
    (net (code "44") (name "/CONFIG_P14") (class "Default")
      (node (ref "U1_13") (pin "36") (pinfunction "CONFIG_PO_36") (pintype "passive"))
      (node (ref "U1_14") (pin "1") (pinfunction "CONFIG_PI_1") (pintype "passive"))
    )
    (net (code "45") (name "/CONFIG_P15") (class "Default")
      (node (ref "U1_14") (pin "36") (pinfunction "CONFIG_PO_36") (pintype "passive"))
      (node (ref "U1_15") (pin "1") (pinfunction "CONFIG_PI_1") (pintype "passive"))
    )
    (net (code "46") (name "/CONFIG_P16") (class "Default")
      (node (ref "U1_15") (pin "36") (pinfunction "CONFIG_PO_36") (pintype "passive"))
      (node (ref "U1_16") (pin "1") (pinfunction "CONFIG_PI_1") (pintype "passive"))
    )
    (net (code "47") (name "/CONFIG_P17") (class "Default")
      (node (ref "U1_16") (pin "36") (pinfunction "CONFIG_PO_36") (pintype "passive"))
    )
    (net (code "48") (name "/CSN4") (class "Default")
      (node (ref "U1") (pin "14") (pinfunction "AN2/C2IN2-/VMIO/RPI34/RB2_14") (pintype "passive"))
    )
    (net (code "49") (name "/CSP4") (class "Default")
      (node (ref "U1") (pin "13") (pinfunction "AN3/C2IN1+/VPIO/RPI35/RB3_13") (pintype "passive"))
    )
    (net (code "50") (name "/C_CLK_OUT1") (class "Default")
      (node (ref "U1_1") (pin "43") (pinfunction "CORE_CLKOUT_43") (pintype "passive"))
    )
    (net (code "51") (name "/C_CLK_OUT2") (class "Default")
      (node (ref "U1_2") (pin "43") (pinfunction "CORE_CLKOUT_43") (pintype "passive"))
    )
    (net (code "52") (name "/C_CLK_OUT3") (class "Default")
      (node (ref "U1_3") (pin "43") (pinfunction "CORE_CLKOUT_43") (pintype "passive"))
    )
    (net (code "53") (name "/C_CLK_OUT4") (class "Default")
      (node (ref "U1_4") (pin "43") (pinfunction "CORE_CLKOUT_43") (pintype "passive"))
    )
    (net (code "54") (name "/C_CLK_OUT5") (class "Default")
      (node (ref "U1_5") (pin "43") (pinfunction "CORE_CLKOUT_43") (pintype "passive"))
    )
    (net (code "55") (name "/C_CLK_OUT6") (class "Default")
      (node (ref "U1_6") (pin "43") (pinfunction "CORE_CLKOUT_43") (pintype "passive"))
    )
    (net (code "56") (name "/C_CLK_OUT7") (class "Default")
      (node (ref "U1_7") (pin "43") (pinfunction "CORE_CLKOUT_43") (pintype "passive"))
    )
    (net (code "57") (name "/C_CLK_OUT8") (class "Default")
      (node (ref "U1_8") (pin "43") (pinfunction "CORE_CLKOUT_43") (pintype "passive"))
    )
    (net (code "58") (name "/C_CLK_OUT9") (class "Default")
      (node (ref "U1_9") (pin "43") (pinfunction "CORE_CLKOUT_43") (pintype "passive"))
    )
    (net (code "59") (name "/C_CLK_OUT10") (class "Default")
      (node (ref "U1_10") (pin "43") (pinfunction "CORE_CLKOUT_43") (pintype "passive"))
    )
    (net (code "60") (name "/C_CLK_OUT11") (class "Default")
      (node (ref "U1_11") (pin "43") (pinfunction "CORE_CLKOUT_43") (pintype "passive"))
    )
    (net (code "61") (name "/C_CLK_OUT12") (class "Default")
      (node (ref "U1_12") (pin "43") (pinfunction "CORE_CLKOUT_43") (pintype "passive"))
    )
    (net (code "62") (name "/C_CLK_OUT13") (class "Default")
      (node (ref "U1_13") (pin "43") (pinfunction "CORE_CLKOUT_43") (pintype "passive"))
    )
    (net (code "63") (name "/C_CLK_OUT14") (class "Default")
      (node (ref "U1_14") (pin "43") (pinfunction "CORE_CLKOUT_43") (pintype "passive"))
    )
    (net (code "64") (name "/C_CLK_OUT15") (class "Default")
      (node (ref "U1_15") (pin "43") (pinfunction "CORE_CLKOUT_43") (pintype "passive"))
    )
    (net (code "65") (name "/C_CLK_OUT16") (class "Default")
      (node (ref "U1_16") (pin "43") (pinfunction "CORE_CLKOUT_43") (pintype "passive"))
    )
    (net (code "66") (name "/CompFB+") (class "Default")
      (node (ref "C5") (pin "1") (pinfunction "1_1") (pintype "passive"))
      (node (ref "R20") (pin "1") (pinfunction "1_1") (pintype "passive"))
      (node (ref "U1") (pin "11") (pinfunction "AN5/C1IN1+/VBUSON/VBUSST/RPI37/RB5_11") (pintype "passive"))
    )
    (net (code "67") (name "/CompFB-") (class "Default")
      (node (ref "C6") (pin "1") (pinfunction "1_1") (pintype "passive"))
      (node (ref "R21") (pin "1") (pinfunction "1_1") (pintype "passive"))
      (node (ref "U1") (pin "12") (pinfunction "AN4/C1IN2-/USBOEN/RPI36/RB4_12") (pintype "passive"))
    )
    (net (code "68") (name "/D+") (class "Default")
      (node (ref "D5") (pin "1") (pinfunction "C1_1") (pintype "passive"))
      (node (ref "J2") (pin "3") (pinfunction "3_3") (pintype "passive"))
      (node (ref "U1") (pin "37") (pinfunction "D+/RG2_37") (pintype "passive"))
    )
    (net (code "69") (name "/D-") (class "Default")
      (node (ref "D5") (pin "3") (pinfunction "C2_3") (pintype "passive"))
      (node (ref "J2") (pin "2") (pinfunction "2_2") (pintype "passive"))
      (node (ref "U1") (pin "36") (pinfunction "D-/RG3_36") (pintype "passive"))
    )
    (net (code "70") (name "/DRVLogic") (class "Default")
      (node (ref "C2P_1") (pin "1") (pinfunction "1_1") (pintype "passive"))
      (node (ref "C2P_2") (pin "1") (pinfunction "1_1") (pintype "passive"))
      (node (ref "C2P_3") (pin "1") (pinfunction "1_1") (pintype "passive"))
      (node (ref "R17") (pin "2") (pinfunction "2_2") (pintype "passive"))
      (node (ref "R19") (pin "2") (pinfunction "2_2") (pintype "passive"))
      (node (ref "U1") (pin "2") (pinfunction "AN30/PWM4L/PMD6/RPI86/RE6_2") (pintype "passive"))
      (node (ref "U1P_1") (pin "6") (pinfunction "Vlogic_6") (pintype "passive"))
      (node (ref "U1P_2") (pin "6") (pinfunction "Vlogic_6") (pintype "passive"))
      (node (ref "U1P_3") (pin "6") (pinfunction "Vlogic_6") (pintype "passive"))
    )
    (net (code "71") (name "/FB") (class "Default")
      (node (ref "C3") (pin "1") (pinfunction "1_1") (pintype "passive"))
      (node (ref "R18") (pin "1") (pinfunction "1_1") (pintype "passive"))
      (node (ref "U1") (pin "17") (pinfunction "PGEC1/AN6/RPI38/RB6_17") (pintype "passive"))
    )
    (net (code "72") (name "/GREEN") (class "Default")
      (node (ref "D2") (pin "2") (pinfunction "A_2") (pintype "passive"))
      (node (ref "U1") (pin "47") (pinfunction "PGED2/SOSCI/C3IN3-/RPI61/RC13_47") (pintype "passive"))
    )
    (net (code "73") (name "/HO1") (class "Default")
      (node (ref "Q1P_1") (pin "4") (pinfunction "G_4") (pintype "passive"))
      (node (ref "U1P_1") (pin "1") (pinfunction "HO_1") (pintype "passive"))
    )
    (net (code "74") (name "/HO2") (class "Default")
      (node (ref "Q1P_2") (pin "4") (pinfunction "G_4") (pintype "passive"))
      (node (ref "U1P_2") (pin "1") (pinfunction "HO_1") (pintype "passive"))
    )
    (net (code "75") (name "/HO3") (class "Default")
      (node (ref "Q1P_3") (pin "4") (pinfunction "G_4") (pintype "passive"))
      (node (ref "U1P_3") (pin "1") (pinfunction "HO_1") (pintype "passive"))
    )
    (net (code "76") (name "/LDO3.3V-5.0V") (class "Default")
      (node (ref "R27") (pin "2") (pinfunction "2_2") (pintype "passive"))
      (node (ref "R30") (pin "1") (pinfunction "1_1") (pintype "passive"))
      (node (ref "U6") (pin "5") (pinfunction "N.C._5") (pintype "passive"))
      (node (ref "U6") (pin "8") (pinfunction "INPUT_8") (pintype "passive"))
    )
    (net (code "77") (name "/LDO5.0V") (class "Default")
      (node (ref "C15") (pin "1") (pinfunction "1_1") (pintype "passive"))
      (node (ref "D7") (pin "2") (pinfunction "A_2") (pintype "passive"))
      (node (ref "D8") (pin "1") (pinfunction "C_1") (pintype "passive"))
      (node (ref "R25") (pin "1") (pinfunction "1_1") (pintype "passive"))
      (node (ref "R26") (pin "2") (pinfunction "2_2") (pintype "passive"))
      (node (ref "R30") (pin "2") (pinfunction "2_2") (pintype "passive"))
      (node (ref "U3") (pin "1") (pinfunction "Vin_1") (pintype "passive"))
      (node (ref "U3") (pin "3") (pinfunction "STBY_3") (pintype "passive"))
      (node (ref "U7") (pin "5") (pinfunction "N.C._5") (pintype "passive"))
      (node (ref "U7") (pin "8") (pinfunction "INPUT_8") (pintype "passive"))
    )
    (net (code "78") (name "/LM12V") (class "Default")
      (node (ref "D9") (pin "1") (pinfunction "C_1") (pintype "passive"))
      (node (ref "R28") (pin "1") (pinfunction "1_1") (pintype "passive"))
      (node (ref "U2") (pin "8") (pinfunction "INPUT_8") (pintype "passive"))
      (node (ref "U4") (pin "1") (pinfunction "Vout_1") (pintype "passive"))
      (node (ref "U5") (pin "1") (pinfunction "Vout_1") (pintype "passive"))
    )
    (net (code "79") (name "/LO1") (class "Default")
      (node (ref "Q2P_1") (pin "4") (pinfunction "G_4") (pintype "passive"))
      (node (ref "Q3P_1") (pin "4") (pinfunction "G_4") (pintype "passive"))
      (node (ref "U1P_1") (pin "3") (pinfunction "LO_3") (pintype "passive"))
    )
    (net (code "80") (name "/LO2") (class "Default")
      (node (ref "Q2P_2") (pin "4") (pinfunction "G_4") (pintype "passive"))
      (node (ref "Q3P_2") (pin "4") (pinfunction "G_4") (pintype "passive"))
      (node (ref "U1P_2") (pin "3") (pinfunction "LO_3") (pintype "passive"))
    )
    (net (code "81") (name "/LO3") (class "Default")
      (node (ref "Q2P_3") (pin "4") (pinfunction "G_4") (pintype "passive"))
      (node (ref "Q3P_3") (pin "4") (pinfunction "G_4") (pintype "passive"))
      (node (ref "U1P_3") (pin "3") (pinfunction "LO_3") (pintype "passive"))
    )
    (net (code "82") (name "/MCLR") (class "Default")
      (node (ref "C7") (pin "1") (pinfunction "1_1") (pintype "passive"))
      (node (ref "J1") (pin "1") (pinfunction "1_1") (pintype "passive"))
      (node (ref "R22") (pin "1") (pinfunction "1_1") (pintype "passive"))
      (node (ref "U1") (pin "7") (pinfunction "MCLR_7") (pintype "passive"))
    )
    (net (code "83") (name "/MCU5.0V") (class "Default")
      (node (ref "R23") (pin "2") (pinfunction "2_2") (pintype "passive"))
      (node (ref "U1") (pin "34") (pinfunction "VBUS_34") (pintype "passive"))
    )
    (net (code "84") (name "/MCU_MISO0") (class "Default")
      (node (ref "U1") (pin "5") (pinfunction "C1IN1-/SDI2/PMA4/RPI119/RG7_5") (pintype "passive"))
    )
    (net (code "85") (name "/MCU_MOSI0") (class "Default")
      (node (ref "U1") (pin "6") (pinfunction "C2IN3-/SDO2/PMA3/RP120/RG8_6") (pintype "passive"))
    )
    (net (code "86") (name "/MCU_SCK0") (class "Default")
      (node (ref "U1") (pin "4") (pinfunction "C1IN3-/SCK2/PMA5/RP118/RG6_4") (pintype "passive"))
    )
    (net (code "87") (name "/MEAS12") (class "Default")
      (node (ref "C2") (pin "1") (pinfunction "1_1") (pintype "passive"))
      (node (ref "R15") (pin "2") (pinfunction "2_2") (pintype "passive"))
      (node (ref "R16") (pin "2") (pinfunction "2_2") (pintype "passive"))
      (node (ref "U1") (pin "18") (pinfunction "PGED1/AN7/RCV/RPI39/RB7_18") (pintype "passive"))
    )
    (net (code "88") (name "/Main OSC In") (class "Default")
      (node (ref "C12") (pin "1") (pinfunction "1_1") (pintype "passive"))
      (node (ref "U1") (pin "39") (pinfunction "OSC1/RPI60/RC12_39") (pintype "passive"))
      (node (ref "Y1") (pin "1") (pinfunction "1_1") (pintype "passive"))
    )
    (net (code "89") (name "/Main OSC Out") (class "Default")
      (node (ref "C13") (pin "1") (pinfunction "1_1") (pintype "passive"))
      (node (ref "U1") (pin "40") (pinfunction "OSC2/CLKO/RC15_40") (pintype "passive"))
      (node (ref "Y1") (pin "2") (pinfunction "2_2") (pintype "passive"))
    )
    (net (code "90") (name "/ORANGE") (class "Default")
      (node (ref "D4") (pin "2") (pinfunction "A_2") (pintype "passive"))
      (node (ref "U1") (pin "45") (pinfunction "PMCS1/RPI75/RD11_45") (pintype "passive"))
    )
    (net (code "91") (name "/PGC") (class "Default")
      (node (ref "J1") (pin "5") (pinfunction "5_5") (pintype "passive"))
      (node (ref "U1") (pin "15") (pinfunction "PGEC3/AN1/VREF-/RPI33/RB1_15") (pintype "passive"))
    )
    (net (code "92") (name "/PGD") (class "Default")
      (node (ref "J1") (pin "4") (pinfunction "4_4") (pintype "passive"))
      (node (ref "U1") (pin "16") (pinfunction "PGED3/AN0/VREF+/RPI32/RB0_16") (pintype "passive"))
    )
    (net (code "93") (name "/PWM1H") (class "Default")
      (node (ref "U1") (pin "61") (pinfunction "AN25/PWM1H/PMD1/RPI81/RE1_61") (pintype "passive"))
    )
    (net (code "94") (name "/PWM1L") (class "Default")
      (node (ref "U1") (pin "60") (pinfunction "AN24/PWM1L/PMD0/RP80/RE0_60") (pintype "passive"))
    )
    (net (code "95") (name "/PWM2H") (class "Default")
      (node (ref "R10") (pin "1") (pinfunction "1_1") (pintype "passive"))
      (node (ref "U1") (pin "63") (pinfunction "AN27/PWM2H/PMD3/RPI83/RE3_63") (pintype "passive"))
      (node (ref "U1P_2") (pin "5") (pinfunction "IN_5") (pintype "passive"))
    )
    (net (code "96") (name "/PWM2L") (class "Default")
      (node (ref "R11") (pin "1") (pinfunction "1_1") (pintype "passive"))
      (node (ref "U1") (pin "62") (pinfunction "AN26/PWM2L/PMD2/RP82/RE2_62") (pintype "passive"))
      (node (ref "U1P_1") (pin "5") (pinfunction "IN_5") (pintype "passive"))
    )
    (net (code "97") (name "/PWM3H") (class "Default")
      (node (ref "R12") (pin "2") (pinfunction "2_2") (pintype "passive"))
      (node (ref "U1") (pin "1") (pinfunction "AN29/PWM3H/PMD5/RP85/RE5_1") (pintype "passive"))
    )
    (net (code "98") (name "/PWM3L") (class "Default")
      (node (ref "R9") (pin "1") (pinfunction "1_1") (pintype "passive"))
      (node (ref "U1") (pin "64") (pinfunction "AN28/PWM3L/PMD4/RP84/RE4_64") (pintype "passive"))
      (node (ref "U1P_3") (pin "5") (pinfunction "IN_5") (pintype "passive"))
    )
    (net (code "99") (name "/RED") (class "Default")
      (node (ref "D1") (pin "2") (pinfunction "A_2") (pintype "passive"))
      (node (ref "U1") (pin "48") (pinfunction "PGEC2/SOSCO/C3IN1-/T1CK/RPI62/RC14_48") (pintype "passive"))
    )
    (net (code "100") (name "/REPORT_N") (class "Default")
      (node (ref "Q1") (pin "3") (pinfunction "C_3") (pintype "passive"))
      (node (ref "R1") (pin "1") (pinfunction "1_1") (pintype "passive"))
      (node (ref "U1") (pin "51") (pinfunction "PMBE/RP67/RD3_51") (pintype "passive"))
    )
    (net (code "101") (name "/REPORT_NA") (class "Default")
      (node (ref "Q1") (pin "1") (pinfunction "B_1") (pintype "passive"))
      (node (ref "R24") (pin "1") (pinfunction "1_1") (pintype "passive"))
      (node (ref "U1_1") (pin "16") (pinfunction "REPORT_N_16") (pintype "passive"))
      (node (ref "U1_10") (pin "16") (pinfunction "REPORT_N_16") (pintype "passive"))
      (node (ref "U1_11") (pin "16") (pinfunction "REPORT_N_16") (pintype "passive"))
      (node (ref "U1_12") (pin "16") (pinfunction "REPORT_N_16") (pintype "passive"))
      (node (ref "U1_13") (pin "16") (pinfunction "REPORT_N_16") (pintype "passive"))
      (node (ref "U1_14") (pin "16") (pinfunction "REPORT_N_16") (pintype "passive"))
      (node (ref "U1_15") (pin "16") (pinfunction "REPORT_N_16") (pintype "passive"))
      (node (ref "U1_16") (pin "16") (pinfunction "REPORT_N_16") (pintype "passive"))
      (node (ref "U1_2") (pin "16") (pinfunction "REPORT_N_16") (pintype "passive"))
      (node (ref "U1_3") (pin "16") (pinfunction "REPORT_N_16") (pintype "passive"))
      (node (ref "U1_4") (pin "16") (pinfunction "REPORT_N_16") (pintype "passive"))
      (node (ref "U1_5") (pin "16") (pinfunction "REPORT_N_16") (pintype "passive"))
      (node (ref "U1_6") (pin "16") (pinfunction "REPORT_N_16") (pintype "passive"))
      (node (ref "U1_7") (pin "16") (pinfunction "REPORT_N_16") (pintype "passive"))
      (node (ref "U1_8") (pin "16") (pinfunction "REPORT_N_16") (pintype "passive"))
      (node (ref "U1_9") (pin "16") (pinfunction "REPORT_N_16") (pintype "passive"))
    )
    (net (code "102") (name "/REPORT_P") (class "Default")
      (node (ref "Q2") (pin "3") (pinfunction "C_3") (pintype "passive"))
      (node (ref "R2") (pin "1") (pinfunction "1_1") (pintype "passive"))
      (node (ref "U1") (pin "50") (pinfunction "DPH/RP66/RD2_50") (pintype "passive"))
    )
    (net (code "103") (name "/REPORT_PA") (class "Default")
      (node (ref "Q2") (pin "1") (pinfunction "B_1") (pintype "passive"))
      (node (ref "R32") (pin "1") (pinfunction "1_1") (pintype "passive"))
      (node (ref "U1_1") (pin "17") (pinfunction "REPORT_P_17") (pintype "passive"))
      (node (ref "U1_10") (pin "17") (pinfunction "REPORT_P_17") (pintype "passive"))
      (node (ref "U1_11") (pin "17") (pinfunction "REPORT_P_17") (pintype "passive"))
      (node (ref "U1_12") (pin "17") (pinfunction "REPORT_P_17") (pintype "passive"))
      (node (ref "U1_13") (pin "17") (pinfunction "REPORT_P_17") (pintype "passive"))
      (node (ref "U1_14") (pin "17") (pinfunction "REPORT_P_17") (pintype "passive"))
      (node (ref "U1_15") (pin "17") (pinfunction "REPORT_P_17") (pintype "passive"))
      (node (ref "U1_16") (pin "17") (pinfunction "REPORT_P_17") (pintype "passive"))
      (node (ref "U1_2") (pin "17") (pinfunction "REPORT_P_17") (pintype "passive"))
      (node (ref "U1_3") (pin "17") (pinfunction "REPORT_P_17") (pintype "passive"))
      (node (ref "U1_4") (pin "17") (pinfunction "REPORT_P_17") (pintype "passive"))
      (node (ref "U1_5") (pin "17") (pinfunction "REPORT_P_17") (pintype "passive"))
      (node (ref "U1_6") (pin "17") (pinfunction "REPORT_P_17") (pintype "passive"))
      (node (ref "U1_7") (pin "17") (pinfunction "REPORT_P_17") (pintype "passive"))
      (node (ref "U1_8") (pin "17") (pinfunction "REPORT_P_17") (pintype "passive"))
      (node (ref "U1_9") (pin "17") (pinfunction "REPORT_P_17") (pintype "passive"))
    )
    (net (code "104") (name "/SWN1") (class "Default")
      (node (ref "C3P_1") (pin "2") (pinfunction "2_2") (pintype "passive"))
      (node (ref "L1P_1") (pin "1") (pinfunction "1_1") (pintype "passive"))
      (node (ref "Q1P_1") (pin "1") (pinfunction "S_1") (pintype "passive"))
      (node (ref "Q1P_1") (pin "2") (pinfunction "S_2") (pintype "passive"))
      (node (ref "Q1P_1") (pin "3") (pinfunction "S_3") (pintype "passive"))
      (node (ref "Q2P_1") (pin "5") (pinfunction "D_5") (pintype "passive"))
      (node (ref "Q2P_1") (pin "6") (pinfunction "D_6") (pintype "passive"))
      (node (ref "Q2P_1") (pin "7") (pinfunction "D_7") (pintype "passive"))
      (node (ref "Q2P_1") (pin "8") (pinfunction "D_8") (pintype "passive"))
      (node (ref "Q3P_1") (pin "5") (pinfunction "D_5") (pintype "passive"))
      (node (ref "Q3P_1") (pin "6") (pinfunction "D_6") (pintype "passive"))
      (node (ref "Q3P_1") (pin "7") (pinfunction "D_7") (pintype "passive"))
      (node (ref "Q3P_1") (pin "8") (pinfunction "D_8") (pintype "passive"))
      (node (ref "U1P_1") (pin "2") (pinfunction "SW_2") (pintype "passive"))
    )
    (net (code "105") (name "/SWN2") (class "Default")
      (node (ref "C3P_2") (pin "2") (pinfunction "2_2") (pintype "passive"))
      (node (ref "L1P_2") (pin "1") (pinfunction "1_1") (pintype "passive"))
      (node (ref "Q1P_2") (pin "1") (pinfunction "S_1") (pintype "passive"))
      (node (ref "Q1P_2") (pin "2") (pinfunction "S_2") (pintype "passive"))
      (node (ref "Q1P_2") (pin "3") (pinfunction "S_3") (pintype "passive"))
      (node (ref "Q2P_2") (pin "5") (pinfunction "D_5") (pintype "passive"))
      (node (ref "Q2P_2") (pin "6") (pinfunction "D_6") (pintype "passive"))
      (node (ref "Q2P_2") (pin "7") (pinfunction "D_7") (pintype "passive"))
      (node (ref "Q2P_2") (pin "8") (pinfunction "D_8") (pintype "passive"))
      (node (ref "Q3P_2") (pin "5") (pinfunction "D_5") (pintype "passive"))
      (node (ref "Q3P_2") (pin "6") (pinfunction "D_6") (pintype "passive"))
      (node (ref "Q3P_2") (pin "7") (pinfunction "D_7") (pintype "passive"))
      (node (ref "Q3P_2") (pin "8") (pinfunction "D_8") (pintype "passive"))
      (node (ref "U1P_2") (pin "2") (pinfunction "SW_2") (pintype "passive"))
    )
    (net (code "106") (name "/SWN3") (class "Default")
      (node (ref "C3P_3") (pin "2") (pinfunction "2_2") (pintype "passive"))
      (node (ref "L1P_3") (pin "1") (pinfunction "1_1") (pintype "passive"))
      (node (ref "Q1P_3") (pin "1") (pinfunction "S_1") (pintype "passive"))
      (node (ref "Q1P_3") (pin "2") (pinfunction "S_2") (pintype "passive"))
      (node (ref "Q1P_3") (pin "3") (pinfunction "S_3") (pintype "passive"))
      (node (ref "Q2P_3") (pin "5") (pinfunction "D_5") (pintype "passive"))
      (node (ref "Q2P_3") (pin "6") (pinfunction "D_6") (pintype "passive"))
      (node (ref "Q2P_3") (pin "7") (pinfunction "D_7") (pintype "passive"))
      (node (ref "Q2P_3") (pin "8") (pinfunction "D_8") (pintype "passive"))
      (node (ref "Q3P_3") (pin "5") (pinfunction "D_5") (pintype "passive"))
      (node (ref "Q3P_3") (pin "6") (pinfunction "D_6") (pintype "passive"))
      (node (ref "Q3P_3") (pin "7") (pinfunction "D_7") (pintype "passive"))
      (node (ref "Q3P_3") (pin "8") (pinfunction "D_8") (pintype "passive"))
      (node (ref "U1P_3") (pin "2") (pinfunction "SW_2") (pintype "passive"))
    )
    (net (code "107") (name "/TP1") (class "Default")
      (node (ref "U1") (pin "54") (pinfunction "C3IN2-/RP70/RD6_54") (pintype "passive"))
    )
    (net (code "108") (name "/TP1_1") (class "Default")
      (node (ref "U1") (pin "59") (pinfunction "VCMPST2/RP97/RF1_59") (pintype "passive"))
    )
    (net (code "109") (name "/TP1_2") (class "Default")
      (node (ref "U1") (pin "58") (pinfunction "VCMPST1/RP96/RF0_58") (pintype "passive"))
    )
    (net (code "110") (name "/TP8") (class "Default")
      (node (ref "U1") (pin "33") (pinfunction "USBID/RP99/RF3_33") (pintype "passive"))
    )
    (net (code "111") (name "/TP9") (class "Default")
      (node (ref "U1") (pin "30") (pinfunction "AN15/PMA0/RPI47/RB15_30") (pintype "passive"))
    )
    (net (code "112") (name "/TP10") (class "Default")
      (node (ref "U1") (pin "29") (pinfunction "AN14/PMA1/RPI46/RB14_29") (pintype "passive"))
    )
    (net (code "113") (name "/TP11") (class "Default")
      (node (ref "U1") (pin "28") (pinfunction "TDI/AN13/PMA10/RPI45/RB13_28") (pintype "passive"))
    )
    (net (code "114") (name "/TP12") (class "Default")
      (node (ref "U1") (pin "27") (pinfunction "TCK/AN12/PMA11/RPI44/RB12_27") (pintype "passive"))
    )
    (net (code "115") (name "/TP13") (class "Default")
      (node (ref "U1") (pin "24") (pinfunction "TDO/AN11/PMA12/RPI43/RB11_24") (pintype "passive"))
    )
    (net (code "116") (name "/TP14") (class "Default")
      (node (ref "U1") (pin "23") (pinfunction "TMS/AN10/CVREF/PMA13/RPI42/RB10_23") (pintype "passive"))
    )
    (net (code "117") (name "/TP15") (class "Default")
      (node (ref "U1") (pin "22") (pinfunction "AN9/PMA7//RPI41/RB9_22") (pintype "passive"))
    )
    (net (code "118") (name "/TP16") (class "Default")
      (node (ref "U1") (pin "21") (pinfunction "AN8/PMA6/RPI40/RB8_21") (pintype "passive"))
    )
    (net (code "119") (name "/TP17") (class "Default")
      (node (ref "U1") (pin "8") (pinfunction "C2IN1-/PMA2/RPI121/RG9_8") (pintype "passive"))
    )
    (net (code "120") (name "/U2Rx") (class "Default")
      (node (ref "U1") (pin "31") (pinfunction "SDA2/PMA9/RP100/RF4_31") (pintype "passive"))
    )
    (net (code "121") (name "/U2Tx") (class "Default")
      (node (ref "U1") (pin "32") (pinfunction "SCL2/PMA8/RP101/RF5_32") (pintype "passive"))
    )
    (net (code "122") (name "/USB5.0V") (class "Default")
      (node (ref "D5") (pin "4") (pinfunction "C3_4") (pintype "passive"))
      (node (ref "D5") (pin "6") (pinfunction "C4_6") (pintype "passive"))
      (node (ref "J2") (pin "1") (pinfunction "1_1") (pintype "passive"))
      (node (ref "R23") (pin "1") (pinfunction "1_1") (pintype "passive"))
      (node (ref "R25") (pin "2") (pinfunction "2_2") (pintype "passive"))
    )
    (net (code "123") (name "/VCAP") (class "Default")
      (node (ref "C1") (pin "1") (pinfunction "1_1") (pintype "passive"))
      (node (ref "U1") (pin "56") (pinfunction "VCAP_56") (pintype "passive"))
    )
    (net (code "124") (name "/XCLK1") (class "Default")
      (node (ref "R14") (pin "2") (pinfunction "2_2") (pintype "passive"))
      (node (ref "U1") (pin "46") (pinfunction "INT0/DMH/RP64/RD0_46") (pintype "passive"))
      (node (ref "U1") (pin "49") (pinfunction "VCPCON/RP65/RD1_49") (pintype "passive"))
      (node (ref "U1") (pin "52") (pinfunction "PMWR/RP68/RD4_52") (pintype "passive"))
      (node (ref "U1") (pin "53") (pinfunction "PMRD/RP69/RD5_53") (pintype "passive"))
    )
    (net (code "125") (name "/XCLKIN") (class "Default")
      (node (ref "R14") (pin "1") (pinfunction "1_1") (pintype "passive"))
      (node (ref "R8") (pin "1") (pinfunction "1_1") (pintype "passive"))
      (node (ref "U1_1") (pin "9") (pinfunction "XCLKIN_9") (pintype "passive"))
      (node (ref "U1_10") (pin "9") (pinfunction "XCLKIN_9") (pintype "passive"))
      (node (ref "U1_11") (pin "9") (pinfunction "XCLKIN_9") (pintype "passive"))
      (node (ref "U1_12") (pin "9") (pinfunction "XCLKIN_9") (pintype "passive"))
      (node (ref "U1_13") (pin "9") (pinfunction "XCLKIN_9") (pintype "passive"))
      (node (ref "U1_14") (pin "9") (pinfunction "XCLKIN_9") (pintype "passive"))
      (node (ref "U1_15") (pin "9") (pinfunction "XCLKIN_9") (pintype "passive"))
      (node (ref "U1_16") (pin "9") (pinfunction "XCLKIN_9") (pintype "passive"))
      (node (ref "U1_2") (pin "9") (pinfunction "XCLKIN_9") (pintype "passive"))
      (node (ref "U1_3") (pin "9") (pinfunction "XCLKIN_9") (pintype "passive"))
      (node (ref "U1_4") (pin "9") (pinfunction "XCLKIN_9") (pintype "passive"))
      (node (ref "U1_5") (pin "9") (pinfunction "XCLKIN_9") (pintype "passive"))
      (node (ref "U1_6") (pin "9") (pinfunction "XCLKIN_9") (pintype "passive"))
      (node (ref "U1_7") (pin "9") (pinfunction "XCLKIN_9") (pintype "passive"))
      (node (ref "U1_8") (pin "9") (pinfunction "XCLKIN_9") (pintype "passive"))
      (node (ref "U1_9") (pin "9") (pinfunction "XCLKIN_9") (pintype "passive"))
    )
    (net (code "126") (name "/YELLOW") (class "Default")
      (node (ref "D3") (pin "2") (pinfunction "A_2") (pintype "passive"))
      (node (ref "U1") (pin "44") (pinfunction "ASCL1/PMCS2/RPI74/RD10_44") (pintype "passive"))
    )
    (net (code "127") (name "GND") (class "Default")
      (node (ref "C1") (pin "2") (pinfunction "2_2") (pintype "passive"))
      (node (ref "C10") (pin "2") (pinfunction "2_2") (pintype "passive"))
      (node (ref "C10_1") (pin "2") (pinfunction "2_2") (pintype "passive"))
      (node (ref "C10_10") (pin "2") (pinfunction "2_2") (pintype "passive"))
      (node (ref "C10_11") (pin "2") (pinfunction "2_2") (pintype "passive"))
      (node (ref "C10_12") (pin "2") (pinfunction "2_2") (pintype "passive"))
      (node (ref "C10_13") (pin "2") (pinfunction "2_2") (pintype "passive"))
      (node (ref "C10_14") (pin "2") (pinfunction "2_2") (pintype "passive"))
      (node (ref "C10_15") (pin "2") (pinfunction "2_2") (pintype "passive"))
      (node (ref "C10_16") (pin "2") (pinfunction "2_2") (pintype "passive"))
      (node (ref "C10_2") (pin "2") (pinfunction "2_2") (pintype "passive"))
      (node (ref "C10_3") (pin "2") (pinfunction "2_2") (pintype "passive"))
      (node (ref "C10_4") (pin "2") (pinfunction "2_2") (pintype "passive"))
      (node (ref "C10_5") (pin "2") (pinfunction "2_2") (pintype "passive"))
      (node (ref "C10_6") (pin "2") (pinfunction "2_2") (pintype "passive"))
      (node (ref "C10_7") (pin "2") (pinfunction "2_2") (pintype "passive"))
      (node (ref "C10_8") (pin "2") (pinfunction "2_2") (pintype "passive"))
      (node (ref "C10_9") (pin "2") (pinfunction "2_2") (pintype "passive"))
      (node (ref "C11") (pin "2") (pinfunction "2_2") (pintype "passive"))
      (node (ref "C11_1") (pin "2") (pinfunction "2_2") (pintype "passive"))
      (node (ref "C11_10") (pin "2") (pinfunction "2_2") (pintype "passive"))
      (node (ref "C11_11") (pin "2") (pinfunction "2_2") (pintype "passive"))
      (node (ref "C11_12") (pin "2") (pinfunction "2_2") (pintype "passive"))
      (node (ref "C11_13") (pin "2") (pinfunction "2_2") (pintype "passive"))
      (node (ref "C11_14") (pin "2") (pinfunction "2_2") (pintype "passive"))
      (node (ref "C11_15") (pin "2") (pinfunction "2_2") (pintype "passive"))
      (node (ref "C11_16") (pin "2") (pinfunction "2_2") (pintype "passive"))
      (node (ref "C11_2") (pin "2") (pinfunction "2_2") (pintype "passive"))
      (node (ref "C11_3") (pin "2") (pinfunction "2_2") (pintype "passive"))
      (node (ref "C11_4") (pin "2") (pinfunction "2_2") (pintype "passive"))
      (node (ref "C11_5") (pin "2") (pinfunction "2_2") (pintype "passive"))
      (node (ref "C11_6") (pin "2") (pinfunction "2_2") (pintype "passive"))
      (node (ref "C11_7") (pin "2") (pinfunction "2_2") (pintype "passive"))
      (node (ref "C11_8") (pin "2") (pinfunction "2_2") (pintype "passive"))
      (node (ref "C11_9") (pin "2") (pinfunction "2_2") (pintype "passive"))
      (node (ref "C12") (pin "2") (pinfunction "2_2") (pintype "passive"))
      (node (ref "C13") (pin "2") (pinfunction "2_2") (pintype "passive"))
      (node (ref "C14") (pin "2") (pinfunction "2_2") (pintype "passive"))
      (node (ref "C15") (pin "2") (pinfunction "2_2") (pintype "passive"))
      (node (ref "C16") (pin "2") (pinfunction "2_2") (pintype "passive"))
      (node (ref "C17") (pin "2") (pinfunction "2_2") (pintype "passive"))
      (node (ref "C1P_1") (pin "1") (pinfunction "1_1") (pintype "passive"))
      (node (ref "C1P_2") (pin "1") (pinfunction "1_1") (pintype "passive"))
      (node (ref "C1P_3") (pin "1") (pinfunction "1_1") (pintype "passive"))
      (node (ref "C1_1") (pin "2") (pinfunction "2_2") (pintype "passive"))
      (node (ref "C1_10") (pin "2") (pinfunction "2_2") (pintype "passive"))
      (node (ref "C1_11") (pin "2") (pinfunction "2_2") (pintype "passive"))
      (node (ref "C1_12") (pin "2") (pinfunction "2_2") (pintype "passive"))
      (node (ref "C1_13") (pin "2") (pinfunction "2_2") (pintype "passive"))
      (node (ref "C1_14") (pin "2") (pinfunction "2_2") (pintype "passive"))
      (node (ref "C1_15") (pin "2") (pinfunction "2_2") (pintype "passive"))
      (node (ref "C1_16") (pin "2") (pinfunction "2_2") (pintype "passive"))
      (node (ref "C1_2") (pin "2") (pinfunction "2_2") (pintype "passive"))
      (node (ref "C1_3") (pin "2") (pinfunction "2_2") (pintype "passive"))
      (node (ref "C1_4") (pin "2") (pinfunction "2_2") (pintype "passive"))
      (node (ref "C1_5") (pin "2") (pinfunction "2_2") (pintype "passive"))
      (node (ref "C1_6") (pin "2") (pinfunction "2_2") (pintype "passive"))
      (node (ref "C1_7") (pin "2") (pinfunction "2_2") (pintype "passive"))
      (node (ref "C1_8") (pin "2") (pinfunction "2_2") (pintype "passive"))
      (node (ref "C1_9") (pin "2") (pinfunction "2_2") (pintype "passive"))
      (node (ref "C2") (pin "2") (pinfunction "2_2") (pintype "passive"))
      (node (ref "C25") (pin "1") (pinfunction "1_1") (pintype "passive"))
      (node (ref "C26") (pin "2") (pinfunction "2_2") (pintype "passive"))
      (node (ref "C2P_1") (pin "2") (pinfunction "2_2") (pintype "passive"))
      (node (ref "C2P_2") (pin "2") (pinfunction "2_2") (pintype "passive"))
      (node (ref "C2P_3") (pin "2") (pinfunction "2_2") (pintype "passive"))
      (node (ref "C2_1") (pin "2") (pinfunction "2_2") (pintype "passive"))
      (node (ref "C2_10") (pin "2") (pinfunction "2_2") (pintype "passive"))
      (node (ref "C2_11") (pin "2") (pinfunction "2_2") (pintype "passive"))
      (node (ref "C2_12") (pin "2") (pinfunction "2_2") (pintype "passive"))
      (node (ref "C2_13") (pin "2") (pinfunction "2_2") (pintype "passive"))
      (node (ref "C2_14") (pin "2") (pinfunction "2_2") (pintype "passive"))
      (node (ref "C2_15") (pin "2") (pinfunction "2_2") (pintype "passive"))
      (node (ref "C2_16") (pin "2") (pinfunction "2_2") (pintype "passive"))
      (node (ref "C2_2") (pin "2") (pinfunction "2_2") (pintype "passive"))
      (node (ref "C2_3") (pin "2") (pinfunction "2_2") (pintype "passive"))
      (node (ref "C2_4") (pin "2") (pinfunction "2_2") (pintype "passive"))
      (node (ref "C2_5") (pin "2") (pinfunction "2_2") (pintype "passive"))
      (node (ref "C2_6") (pin "2") (pinfunction "2_2") (pintype "passive"))
      (node (ref "C2_7") (pin "2") (pinfunction "2_2") (pintype "passive"))
      (node (ref "C2_8") (pin "2") (pinfunction "2_2") (pintype "passive"))
      (node (ref "C2_9") (pin "2") (pinfunction "2_2") (pintype "passive"))
      (node (ref "C3") (pin "2") (pinfunction "2_2") (pintype "passive"))
      (node (ref "C3_1") (pin "2") (pinfunction "2_2") (pintype "passive"))
      (node (ref "C3_10") (pin "2") (pinfunction "2_2") (pintype "passive"))
      (node (ref "C3_11") (pin "2") (pinfunction "2_2") (pintype "passive"))
      (node (ref "C3_12") (pin "2") (pinfunction "2_2") (pintype "passive"))
      (node (ref "C3_13") (pin "2") (pinfunction "2_2") (pintype "passive"))
      (node (ref "C3_14") (pin "2") (pinfunction "2_2") (pintype "passive"))
      (node (ref "C3_15") (pin "2") (pinfunction "2_2") (pintype "passive"))
      (node (ref "C3_16") (pin "2") (pinfunction "2_2") (pintype "passive"))
      (node (ref "C3_2") (pin "2") (pinfunction "2_2") (pintype "passive"))
      (node (ref "C3_3") (pin "2") (pinfunction "2_2") (pintype "passive"))
      (node (ref "C3_4") (pin "2") (pinfunction "2_2") (pintype "passive"))
      (node (ref "C3_5") (pin "2") (pinfunction "2_2") (pintype "passive"))
      (node (ref "C3_6") (pin "2") (pinfunction "2_2") (pintype "passive"))
      (node (ref "C3_7") (pin "2") (pinfunction "2_2") (pintype "passive"))
      (node (ref "C3_8") (pin "2") (pinfunction "2_2") (pintype "passive"))
      (node (ref "C3_9") (pin "2") (pinfunction "2_2") (pintype "passive"))
      (node (ref "C4") (pin "2") (pinfunction "2_2") (pintype "passive"))
      (node (ref "C4P_1") (pin "2") (pinfunction "2_2") (pintype "passive"))
      (node (ref "C4P_2") (pin "2") (pinfunction "2_2") (pintype "passive"))
      (node (ref "C4P_3") (pin "2") (pinfunction "2_2") (pintype "passive"))
      (node (ref "C4_1") (pin "2") (pinfunction "2_2") (pintype "passive"))
      (node (ref "C4_10") (pin "2") (pinfunction "2_2") (pintype "passive"))
      (node (ref "C4_11") (pin "2") (pinfunction "2_2") (pintype "passive"))
      (node (ref "C4_12") (pin "2") (pinfunction "2_2") (pintype "passive"))
      (node (ref "C4_13") (pin "2") (pinfunction "2_2") (pintype "passive"))
      (node (ref "C4_14") (pin "2") (pinfunction "2_2") (pintype "passive"))
      (node (ref "C4_15") (pin "2") (pinfunction "2_2") (pintype "passive"))
      (node (ref "C4_16") (pin "2") (pinfunction "2_2") (pintype "passive"))
      (node (ref "C4_2") (pin "2") (pinfunction "2_2") (pintype "passive"))
      (node (ref "C4_3") (pin "2") (pinfunction "2_2") (pintype "passive"))
      (node (ref "C4_4") (pin "2") (pinfunction "2_2") (pintype "passive"))
      (node (ref "C4_5") (pin "2") (pinfunction "2_2") (pintype "passive"))
      (node (ref "C4_6") (pin "2") (pinfunction "2_2") (pintype "passive"))
      (node (ref "C4_7") (pin "2") (pinfunction "2_2") (pintype "passive"))
      (node (ref "C4_8") (pin "2") (pinfunction "2_2") (pintype "passive"))
      (node (ref "C4_9") (pin "2") (pinfunction "2_2") (pintype "passive"))
      (node (ref "C5") (pin "2") (pinfunction "2_2") (pintype "passive"))
      (node (ref "C5P_1") (pin "2") (pinfunction "2_2") (pintype "passive"))
      (node (ref "C5P_2") (pin "2") (pinfunction "2_2") (pintype "passive"))
      (node (ref "C5P_3") (pin "2") (pinfunction "2_2") (pintype "passive"))
      (node (ref "C5_1") (pin "1") (pinfunction "1_1") (pintype "passive"))
      (node (ref "C5_10") (pin "1") (pinfunction "1_1") (pintype "passive"))
      (node (ref "C5_11") (pin "1") (pinfunction "1_1") (pintype "passive"))
      (node (ref "C5_12") (pin "1") (pinfunction "1_1") (pintype "passive"))
      (node (ref "C5_13") (pin "1") (pinfunction "1_1") (pintype "passive"))
      (node (ref "C5_14") (pin "1") (pinfunction "1_1") (pintype "passive"))
      (node (ref "C5_15") (pin "1") (pinfunction "1_1") (pintype "passive"))
      (node (ref "C5_16") (pin "1") (pinfunction "1_1") (pintype "passive"))
      (node (ref "C5_2") (pin "1") (pinfunction "1_1") (pintype "passive"))
      (node (ref "C5_3") (pin "1") (pinfunction "1_1") (pintype "passive"))
      (node (ref "C5_4") (pin "1") (pinfunction "1_1") (pintype "passive"))
      (node (ref "C5_5") (pin "1") (pinfunction "1_1") (pintype "passive"))
      (node (ref "C5_6") (pin "1") (pinfunction "1_1") (pintype "passive"))
      (node (ref "C5_7") (pin "1") (pinfunction "1_1") (pintype "passive"))
      (node (ref "C5_8") (pin "1") (pinfunction "1_1") (pintype "passive"))
      (node (ref "C5_9") (pin "1") (pinfunction "1_1") (pintype "passive"))
      (node (ref "C6") (pin "2") (pinfunction "2_2") (pintype "passive"))
      (node (ref "C6P_1") (pin "2") (pinfunction "2_2") (pintype "passive"))
      (node (ref "C6P_2") (pin "2") (pinfunction "2_2") (pintype "passive"))
      (node (ref "C6P_3") (pin "2") (pinfunction "2_2") (pintype "passive"))
      (node (ref "C6_1") (pin "2") (pinfunction "2_2") (pintype "passive"))
      (node (ref "C6_10") (pin "2") (pinfunction "2_2") (pintype "passive"))
      (node (ref "C6_11") (pin "2") (pinfunction "2_2") (pintype "passive"))
      (node (ref "C6_12") (pin "2") (pinfunction "2_2") (pintype "passive"))
      (node (ref "C6_13") (pin "2") (pinfunction "2_2") (pintype "passive"))
      (node (ref "C6_14") (pin "2") (pinfunction "2_2") (pintype "passive"))
      (node (ref "C6_15") (pin "2") (pinfunction "2_2") (pintype "passive"))
      (node (ref "C6_16") (pin "2") (pinfunction "2_2") (pintype "passive"))
      (node (ref "C6_2") (pin "2") (pinfunction "2_2") (pintype "passive"))
      (node (ref "C6_3") (pin "2") (pinfunction "2_2") (pintype "passive"))
      (node (ref "C6_4") (pin "2") (pinfunction "2_2") (pintype "passive"))
      (node (ref "C6_5") (pin "2") (pinfunction "2_2") (pintype "passive"))
      (node (ref "C6_6") (pin "2") (pinfunction "2_2") (pintype "passive"))
      (node (ref "C6_7") (pin "2") (pinfunction "2_2") (pintype "passive"))
      (node (ref "C6_8") (pin "2") (pinfunction "2_2") (pintype "passive"))
      (node (ref "C6_9") (pin "2") (pinfunction "2_2") (pintype "passive"))
      (node (ref "C7") (pin "2") (pinfunction "2_2") (pintype "passive"))
      (node (ref "C7P_1") (pin "2") (pinfunction "2_2") (pintype "passive"))
      (node (ref "C7P_2") (pin "2") (pinfunction "2_2") (pintype "passive"))
      (node (ref "C7P_3") (pin "2") (pinfunction "2_2") (pintype "passive"))
      (node (ref "C7_1") (pin "2") (pinfunction "2_2") (pintype "passive"))
      (node (ref "C7_10") (pin "2") (pinfunction "2_2") (pintype "passive"))
      (node (ref "C7_11") (pin "2") (pinfunction "2_2") (pintype "passive"))
      (node (ref "C7_12") (pin "2") (pinfunction "2_2") (pintype "passive"))
      (node (ref "C7_13") (pin "2") (pinfunction "2_2") (pintype "passive"))
      (node (ref "C7_14") (pin "2") (pinfunction "2_2") (pintype "passive"))
      (node (ref "C7_15") (pin "2") (pinfunction "2_2") (pintype "passive"))
      (node (ref "C7_16") (pin "2") (pinfunction "2_2") (pintype "passive"))
      (node (ref "C7_2") (pin "2") (pinfunction "2_2") (pintype "passive"))
      (node (ref "C7_3") (pin "2") (pinfunction "2_2") (pintype "passive"))
      (node (ref "C7_4") (pin "2") (pinfunction "2_2") (pintype "passive"))
      (node (ref "C7_5") (pin "2") (pinfunction "2_2") (pintype "passive"))
      (node (ref "C7_6") (pin "2") (pinfunction "2_2") (pintype "passive"))
      (node (ref "C7_7") (pin "2") (pinfunction "2_2") (pintype "passive"))
      (node (ref "C7_8") (pin "2") (pinfunction "2_2") (pintype "passive"))
      (node (ref "C7_9") (pin "2") (pinfunction "2_2") (pintype "passive"))
      (node (ref "C8") (pin "2") (pinfunction "2_2") (pintype "passive"))
      (node (ref "C8P_1") (pin "2") (pinfunction "2_2") (pintype "passive"))
      (node (ref "C8P_2") (pin "2") (pinfunction "2_2") (pintype "passive"))
      (node (ref "C8P_3") (pin "2") (pinfunction "2_2") (pintype "passive"))
      (node (ref "C8_1") (pin "2") (pinfunction "2_2") (pintype "passive"))
      (node (ref "C8_10") (pin "2") (pinfunction "2_2") (pintype "passive"))
      (node (ref "C8_11") (pin "2") (pinfunction "2_2") (pintype "passive"))
      (node (ref "C8_12") (pin "2") (pinfunction "2_2") (pintype "passive"))
      (node (ref "C8_13") (pin "2") (pinfunction "2_2") (pintype "passive"))
      (node (ref "C8_14") (pin "2") (pinfunction "2_2") (pintype "passive"))
      (node (ref "C8_15") (pin "2") (pinfunction "2_2") (pintype "passive"))
      (node (ref "C8_16") (pin "2") (pinfunction "2_2") (pintype "passive"))
      (node (ref "C8_2") (pin "2") (pinfunction "2_2") (pintype "passive"))
      (node (ref "C8_3") (pin "2") (pinfunction "2_2") (pintype "passive"))
      (node (ref "C8_4") (pin "2") (pinfunction "2_2") (pintype "passive"))
      (node (ref "C8_5") (pin "2") (pinfunction "2_2") (pintype "passive"))
      (node (ref "C8_6") (pin "2") (pinfunction "2_2") (pintype "passive"))
      (node (ref "C8_7") (pin "2") (pinfunction "2_2") (pintype "passive"))
      (node (ref "C8_8") (pin "2") (pinfunction "2_2") (pintype "passive"))
      (node (ref "C8_9") (pin "2") (pinfunction "2_2") (pintype "passive"))
      (node (ref "C9") (pin "2") (pinfunction "2_2") (pintype "passive"))
      (node (ref "C9_1") (pin "2") (pinfunction "2_2") (pintype "passive"))
      (node (ref "C9_10") (pin "2") (pinfunction "2_2") (pintype "passive"))
      (node (ref "C9_11") (pin "2") (pinfunction "2_2") (pintype "passive"))
      (node (ref "C9_12") (pin "2") (pinfunction "2_2") (pintype "passive"))
      (node (ref "C9_13") (pin "2") (pinfunction "2_2") (pintype "passive"))
      (node (ref "C9_14") (pin "2") (pinfunction "2_2") (pintype "passive"))
      (node (ref "C9_15") (pin "2") (pinfunction "2_2") (pintype "passive"))
      (node (ref "C9_16") (pin "2") (pinfunction "2_2") (pintype "passive"))
      (node (ref "C9_2") (pin "2") (pinfunction "2_2") (pintype "passive"))
      (node (ref "C9_3") (pin "2") (pinfunction "2_2") (pintype "passive"))
      (node (ref "C9_4") (pin "2") (pinfunction "2_2") (pintype "passive"))
      (node (ref "C9_5") (pin "2") (pinfunction "2_2") (pintype "passive"))
      (node (ref "C9_6") (pin "2") (pinfunction "2_2") (pintype "passive"))
      (node (ref "C9_7") (pin "2") (pinfunction "2_2") (pintype "passive"))
      (node (ref "C9_8") (pin "2") (pinfunction "2_2") (pintype "passive"))
      (node (ref "C9_9") (pin "2") (pinfunction "2_2") (pintype "passive"))
      (node (ref "C_220_1") (pin "2") (pinfunction "2_2") (pintype "passive"))
      (node (ref "C_220_10") (pin "2") (pinfunction "2_2") (pintype "passive"))
      (node (ref "C_220_11") (pin "2") (pinfunction "2_2") (pintype "passive"))
      (node (ref "C_220_12") (pin "2") (pinfunction "2_2") (pintype "passive"))
      (node (ref "C_220_13") (pin "2") (pinfunction "2_2") (pintype "passive"))
      (node (ref "C_220_14") (pin "2") (pinfunction "2_2") (pintype "passive"))
      (node (ref "C_220_15") (pin "2") (pinfunction "2_2") (pintype "passive"))
      (node (ref "C_220_16") (pin "2") (pinfunction "2_2") (pintype "passive"))
      (node (ref "C_220_17") (pin "2") (pinfunction "2_2") (pintype "passive"))
      (node (ref "C_220_18") (pin "2") (pinfunction "2_2") (pintype "passive"))
      (node (ref "C_220_19") (pin "2") (pinfunction "2_2") (pintype "passive"))
      (node (ref "C_220_2") (pin "2") (pinfunction "2_2") (pintype "passive"))
      (node (ref "C_220_20") (pin "2") (pinfunction "2_2") (pintype "passive"))
      (node (ref "C_220_21") (pin "2") (pinfunction "2_2") (pintype "passive"))
      (node (ref "C_220_22") (pin "2") (pinfunction "2_2") (pintype "passive"))
      (node (ref "C_220_23") (pin "2") (pinfunction "2_2") (pintype "passive"))
      (node (ref "C_220_24") (pin "2") (pinfunction "2_2") (pintype "passive"))
      (node (ref "C_220_25") (pin "2") (pinfunction "2_2") (pintype "passive"))
      (node (ref "C_220_26") (pin "2") (pinfunction "2_2") (pintype "passive"))
      (node (ref "C_220_27") (pin "2") (pinfunction "2_2") (pintype "passive"))
      (node (ref "C_220_28") (pin "2") (pinfunction "2_2") (pintype "passive"))
      (node (ref "C_220_29") (pin "2") (pinfunction "2_2") (pintype "passive"))
      (node (ref "C_220_3") (pin "2") (pinfunction "2_2") (pintype "passive"))
      (node (ref "C_220_30") (pin "2") (pinfunction "2_2") (pintype "passive"))
      (node (ref "C_220_31") (pin "2") (pinfunction "2_2") (pintype "passive"))
      (node (ref "C_220_32") (pin "2") (pinfunction "2_2") (pintype "passive"))
      (node (ref "C_220_33") (pin "2") (pinfunction "2_2") (pintype "passive"))
      (node (ref "C_220_34") (pin "2") (pinfunction "2_2") (pintype "passive"))
      (node (ref "C_220_35") (pin "2") (pinfunction "2_2") (pintype "passive"))
      (node (ref "C_220_36") (pin "2") (pinfunction "2_2") (pintype "passive"))
      (node (ref "C_220_37") (pin "2") (pinfunction "2_2") (pintype "passive"))
      (node (ref "C_220_38") (pin "2") (pinfunction "2_2") (pintype "passive"))
      (node (ref "C_220_39") (pin "2") (pinfunction "2_2") (pintype "passive"))
      (node (ref "C_220_4") (pin "2") (pinfunction "2_2") (pintype "passive"))
      (node (ref "C_220_40") (pin "2") (pinfunction "2_2") (pintype "passive"))
      (node (ref "C_220_41") (pin "2") (pinfunction "2_2") (pintype "passive"))
      (node (ref "C_220_42") (pin "2") (pinfunction "2_2") (pintype "passive"))
      (node (ref "C_220_43") (pin "2") (pinfunction "2_2") (pintype "passive"))
      (node (ref "C_220_44") (pin "2") (pinfunction "2_2") (pintype "passive"))
      (node (ref "C_220_45") (pin "2") (pinfunction "2_2") (pintype "passive"))
      (node (ref "C_220_46") (pin "2") (pinfunction "2_2") (pintype "passive"))
      (node (ref "C_220_47") (pin "2") (pinfunction "2_2") (pintype "passive"))
      (node (ref "C_220_48") (pin "2") (pinfunction "2_2") (pintype "passive"))
      (node (ref "C_220_49") (pin "2") (pinfunction "2_2") (pintype "passive"))
      (node (ref "C_220_5") (pin "2") (pinfunction "2_2") (pintype "passive"))
      (node (ref "C_220_50") (pin "2") (pinfunction "2_2") (pintype "passive"))
      (node (ref "C_220_51") (pin "2") (pinfunction "2_2") (pintype "passive"))
      (node (ref "C_220_52") (pin "2") (pinfunction "2_2") (pintype "passive"))
      (node (ref "C_220_53") (pin "2") (pinfunction "2_2") (pintype "passive"))
      (node (ref "C_220_54") (pin "2") (pinfunction "2_2") (pintype "passive"))
      (node (ref "C_220_55") (pin "2") (pinfunction "2_2") (pintype "passive"))
      (node (ref "C_220_56") (pin "2") (pinfunction "2_2") (pintype "passive"))
      (node (ref "C_220_57") (pin "2") (pinfunction "2_2") (pintype "passive"))
      (node (ref "C_220_58") (pin "2") (pinfunction "2_2") (pintype "passive"))
      (node (ref "C_220_59") (pin "2") (pinfunction "2_2") (pintype "passive"))
      (node (ref "C_220_6") (pin "2") (pinfunction "2_2") (pintype "passive"))
      (node (ref "C_220_60") (pin "2") (pinfunction "2_2") (pintype "passive"))
      (node (ref "C_220_61") (pin "2") (pinfunction "2_2") (pintype "passive"))
      (node (ref "C_220_62") (pin "2") (pinfunction "2_2") (pintype "passive"))
      (node (ref "C_220_63") (pin "2") (pinfunction "2_2") (pintype "passive"))
      (node (ref "C_220_64") (pin "2") (pinfunction "2_2") (pintype "passive"))
      (node (ref "C_220_65") (pin "2") (pinfunction "2_2") (pintype "passive"))
      (node (ref "C_220_66") (pin "2") (pinfunction "2_2") (pintype "passive"))
      (node (ref "C_220_67") (pin "2") (pinfunction "2_2") (pintype "passive"))
      (node (ref "C_220_68") (pin "2") (pinfunction "2_2") (pintype "passive"))
      (node (ref "C_220_69") (pin "2") (pinfunction "2_2") (pintype "passive"))
      (node (ref "C_220_7") (pin "2") (pinfunction "2_2") (pintype "passive"))
      (node (ref "C_220_70") (pin "2") (pinfunction "2_2") (pintype "passive"))
      (node (ref "C_220_71") (pin "2") (pinfunction "2_2") (pintype "passive"))
      (node (ref "C_220_73") (pin "2") (pinfunction "2_2") (pintype "passive"))
      (node (ref "C_220_8") (pin "2") (pinfunction "2_2") (pintype "passive"))
      (node (ref "C_220_9") (pin "2") (pinfunction "2_2") (pintype "passive"))
      (node (ref "D1") (pin "1") (pinfunction "C_1") (pintype "passive"))
      (node (ref "D10") (pin "2") (pinfunction "A_2") (pintype "passive"))
      (node (ref "D2") (pin "1") (pinfunction "C_1") (pintype "passive"))
      (node (ref "D3") (pin "1") (pinfunction "C_1") (pintype "passive"))
      (node (ref "D4") (pin "1") (pinfunction "C_1") (pintype "passive"))
      (node (ref "D5") (pin "2") (pinfunction "AAAA_2") (pintype "passive"))
      (node (ref "D5") (pin "5") (pinfunction "C4_5") (pintype "passive"))
      (node (ref "J1") (pin "3") (pinfunction "3_3") (pintype "passive"))
      (node (ref "J2") (pin "5") (pinfunction "5_5") (pintype "passive"))
      (node (ref "J2") (pin "6") (pinfunction "6_6") (pintype "passive"))
      (node (ref "J2") (pin "7") (pinfunction "7_7") (pintype "passive"))
      (node (ref "J2") (pin "8") (pinfunction "8_8") (pintype "passive"))
      (node (ref "J2") (pin "9") (pinfunction "9_9") (pintype "passive"))
      (node (ref "J3") (pin "2") (pinfunction "2_2") (pintype "passive"))
      (node (ref "J4") (pin "1") (pinfunction "1_1") (pintype "passive"))
      (node (ref "J4") (pin "3") (pinfunction "3_3") (pintype "passive"))
      (node (ref "J4") (pin "5") (pinfunction "5_5") (pintype "passive"))
      (node (ref "Q1") (pin "2") (pinfunction "E_2") (pintype "passive"))
      (node (ref "Q2") (pin "2") (pinfunction "E_2") (pintype "passive"))
      (node (ref "Q2P_1") (pin "1") (pinfunction "S_1") (pintype "passive"))
      (node (ref "Q2P_1") (pin "2") (pinfunction "S_2") (pintype "passive"))
      (node (ref "Q2P_1") (pin "3") (pinfunction "S_3") (pintype "passive"))
      (node (ref "Q2P_2") (pin "1") (pinfunction "S_1") (pintype "passive"))
      (node (ref "Q2P_2") (pin "2") (pinfunction "S_2") (pintype "passive"))
      (node (ref "Q2P_2") (pin "3") (pinfunction "S_3") (pintype "passive"))
      (node (ref "Q2P_3") (pin "1") (pinfunction "S_1") (pintype "passive"))
      (node (ref "Q2P_3") (pin "2") (pinfunction "S_2") (pintype "passive"))
      (node (ref "Q2P_3") (pin "3") (pinfunction "S_3") (pintype "passive"))
      (node (ref "Q3P_1") (pin "1") (pinfunction "S_1") (pintype "passive"))
      (node (ref "Q3P_1") (pin "2") (pinfunction "S_2") (pintype "passive"))
      (node (ref "Q3P_1") (pin "3") (pinfunction "S_3") (pintype "passive"))
      (node (ref "Q3P_2") (pin "1") (pinfunction "S_1") (pintype "passive"))
      (node (ref "Q3P_2") (pin "2") (pinfunction "S_2") (pintype "passive"))
      (node (ref "Q3P_2") (pin "3") (pinfunction "S_3") (pintype "passive"))
      (node (ref "Q3P_3") (pin "1") (pinfunction "S_1") (pintype "passive"))
      (node (ref "Q3P_3") (pin "2") (pinfunction "S_2") (pintype "passive"))
      (node (ref "Q3P_3") (pin "3") (pinfunction "S_3") (pintype "passive"))
      (node (ref "R10") (pin "2") (pinfunction "2_2") (pintype "passive"))
      (node (ref "R11") (pin "2") (pinfunction "2_2") (pintype "passive"))
      (node (ref "R12") (pin "1") (pinfunction "1_1") (pintype "passive"))
      (node (ref "R13") (pin "1") (pinfunction "1_1") (pintype "passive"))
      (node (ref "R16") (pin "1") (pinfunction "1_1") (pintype "passive"))
      (node (ref "R19") (pin "1") (pinfunction "1_1") (pintype "passive"))
      (node (ref "R31") (pin "1") (pinfunction "1_1") (pintype "passive"))
      (node (ref "R5") (pin "1") (pinfunction "1_1") (pintype "passive"))
      (node (ref "R7") (pin "1") (pinfunction "1_1") (pintype "passive"))
      (node (ref "R8") (pin "2") (pinfunction "2_2") (pintype "passive"))
      (node (ref "R9") (pin "2") (pinfunction "2_2") (pintype "passive"))
      (node (ref "U1") (pin "20") (pinfunction "AVSS_20") (pintype "passive"))
      (node (ref "U1") (pin "25") (pinfunction "VSS_25") (pintype "passive"))
      (node (ref "U1") (pin "41") (pinfunction "VSS_41") (pintype "passive"))
      (node (ref "U1") (pin "9") (pinfunction "VSS_9") (pintype "passive"))
      (node (ref "U1P_1") (pin "4") (pinfunction "GND_4") (pintype "passive"))
      (node (ref "U1P_1") (pin "9") (pinfunction "EP_9") (pintype "passive"))
      (node (ref "U1P_2") (pin "4") (pinfunction "GND_4") (pintype "passive"))
      (node (ref "U1P_2") (pin "9") (pinfunction "EP_9") (pintype "passive"))
      (node (ref "U1P_3") (pin "4") (pinfunction "GND_4") (pintype "passive"))
      (node (ref "U1P_3") (pin "9") (pinfunction "EP_9") (pintype "passive"))
      (node (ref "U1_1") (pin "12") (pinfunction "DVSS_12") (pintype "passive"))
      (node (ref "U1_1") (pin "23") (pinfunction "OVSS1_23") (pintype "passive"))
      (node (ref "U1_1") (pin "27") (pinfunction "DVSS_27") (pintype "passive"))
      (node (ref "U1_1") (pin "38") (pinfunction "OVSS0_38") (pintype "passive"))
      (node (ref "U1_1") (pin "49") (pinfunction "EP_49") (pintype "passive"))
      (node (ref "U1_1") (pin "5") (pinfunction "VSSA_PLL_5") (pintype "passive"))
      (node (ref "U1_1") (pin "8") (pinfunction "VSS_PLL_8") (pintype "passive"))
      (node (ref "U1_10") (pin "12") (pinfunction "DVSS_12") (pintype "passive"))
      (node (ref "U1_10") (pin "23") (pinfunction "OVSS1_23") (pintype "passive"))
      (node (ref "U1_10") (pin "27") (pinfunction "DVSS_27") (pintype "passive"))
      (node (ref "U1_10") (pin "38") (pinfunction "OVSS0_38") (pintype "passive"))
      (node (ref "U1_10") (pin "49") (pinfunction "EP_49") (pintype "passive"))
      (node (ref "U1_10") (pin "5") (pinfunction "VSSA_PLL_5") (pintype "passive"))
      (node (ref "U1_10") (pin "8") (pinfunction "VSS_PLL_8") (pintype "passive"))
      (node (ref "U1_11") (pin "12") (pinfunction "DVSS_12") (pintype "passive"))
      (node (ref "U1_11") (pin "23") (pinfunction "OVSS1_23") (pintype "passive"))
      (node (ref "U1_11") (pin "27") (pinfunction "DVSS_27") (pintype "passive"))
      (node (ref "U1_11") (pin "38") (pinfunction "OVSS0_38") (pintype "passive"))
      (node (ref "U1_11") (pin "49") (pinfunction "EP_49") (pintype "passive"))
      (node (ref "U1_11") (pin "5") (pinfunction "VSSA_PLL_5") (pintype "passive"))
      (node (ref "U1_11") (pin "8") (pinfunction "VSS_PLL_8") (pintype "passive"))
      (node (ref "U1_12") (pin "12") (pinfunction "DVSS_12") (pintype "passive"))
      (node (ref "U1_12") (pin "23") (pinfunction "OVSS1_23") (pintype "passive"))
      (node (ref "U1_12") (pin "27") (pinfunction "DVSS_27") (pintype "passive"))
      (node (ref "U1_12") (pin "38") (pinfunction "OVSS0_38") (pintype "passive"))
      (node (ref "U1_12") (pin "49") (pinfunction "EP_49") (pintype "passive"))
      (node (ref "U1_12") (pin "5") (pinfunction "VSSA_PLL_5") (pintype "passive"))
      (node (ref "U1_12") (pin "8") (pinfunction "VSS_PLL_8") (pintype "passive"))
      (node (ref "U1_13") (pin "12") (pinfunction "DVSS_12") (pintype "passive"))
      (node (ref "U1_13") (pin "23") (pinfunction "OVSS1_23") (pintype "passive"))
      (node (ref "U1_13") (pin "27") (pinfunction "DVSS_27") (pintype "passive"))
      (node (ref "U1_13") (pin "38") (pinfunction "OVSS0_38") (pintype "passive"))
      (node (ref "U1_13") (pin "49") (pinfunction "EP_49") (pintype "passive"))
      (node (ref "U1_13") (pin "5") (pinfunction "VSSA_PLL_5") (pintype "passive"))
      (node (ref "U1_13") (pin "8") (pinfunction "VSS_PLL_8") (pintype "passive"))
      (node (ref "U1_14") (pin "12") (pinfunction "DVSS_12") (pintype "passive"))
      (node (ref "U1_14") (pin "23") (pinfunction "OVSS1_23") (pintype "passive"))
      (node (ref "U1_14") (pin "27") (pinfunction "DVSS_27") (pintype "passive"))
      (node (ref "U1_14") (pin "38") (pinfunction "OVSS0_38") (pintype "passive"))
      (node (ref "U1_14") (pin "49") (pinfunction "EP_49") (pintype "passive"))
      (node (ref "U1_14") (pin "5") (pinfunction "VSSA_PLL_5") (pintype "passive"))
      (node (ref "U1_14") (pin "8") (pinfunction "VSS_PLL_8") (pintype "passive"))
      (node (ref "U1_15") (pin "12") (pinfunction "DVSS_12") (pintype "passive"))
      (node (ref "U1_15") (pin "23") (pinfunction "OVSS1_23") (pintype "passive"))
      (node (ref "U1_15") (pin "27") (pinfunction "DVSS_27") (pintype "passive"))
      (node (ref "U1_15") (pin "38") (pinfunction "OVSS0_38") (pintype "passive"))
      (node (ref "U1_15") (pin "49") (pinfunction "EP_49") (pintype "passive"))
      (node (ref "U1_15") (pin "5") (pinfunction "VSSA_PLL_5") (pintype "passive"))
      (node (ref "U1_15") (pin "8") (pinfunction "VSS_PLL_8") (pintype "passive"))
      (node (ref "U1_16") (pin "12") (pinfunction "DVSS_12") (pintype "passive"))
      (node (ref "U1_16") (pin "23") (pinfunction "OVSS1_23") (pintype "passive"))
      (node (ref "U1_16") (pin "27") (pinfunction "DVSS_27") (pintype "passive"))
      (node (ref "U1_16") (pin "38") (pinfunction "OVSS0_38") (pintype "passive"))
      (node (ref "U1_16") (pin "49") (pinfunction "EP_49") (pintype "passive"))
      (node (ref "U1_16") (pin "5") (pinfunction "VSSA_PLL_5") (pintype "passive"))
      (node (ref "U1_16") (pin "8") (pinfunction "VSS_PLL_8") (pintype "passive"))
      (node (ref "U1_2") (pin "12") (pinfunction "DVSS_12") (pintype "passive"))
      (node (ref "U1_2") (pin "23") (pinfunction "OVSS1_23") (pintype "passive"))
      (node (ref "U1_2") (pin "27") (pinfunction "DVSS_27") (pintype "passive"))
      (node (ref "U1_2") (pin "38") (pinfunction "OVSS0_38") (pintype "passive"))
      (node (ref "U1_2") (pin "49") (pinfunction "EP_49") (pintype "passive"))
      (node (ref "U1_2") (pin "5") (pinfunction "VSSA_PLL_5") (pintype "passive"))
      (node (ref "U1_2") (pin "8") (pinfunction "VSS_PLL_8") (pintype "passive"))
      (node (ref "U1_3") (pin "12") (pinfunction "DVSS_12") (pintype "passive"))
      (node (ref "U1_3") (pin "23") (pinfunction "OVSS1_23") (pintype "passive"))
      (node (ref "U1_3") (pin "27") (pinfunction "DVSS_27") (pintype "passive"))
      (node (ref "U1_3") (pin "38") (pinfunction "OVSS0_38") (pintype "passive"))
      (node (ref "U1_3") (pin "49") (pinfunction "EP_49") (pintype "passive"))
      (node (ref "U1_3") (pin "5") (pinfunction "VSSA_PLL_5") (pintype "passive"))
      (node (ref "U1_3") (pin "8") (pinfunction "VSS_PLL_8") (pintype "passive"))
      (node (ref "U1_4") (pin "12") (pinfunction "DVSS_12") (pintype "passive"))
      (node (ref "U1_4") (pin "23") (pinfunction "OVSS1_23") (pintype "passive"))
      (node (ref "U1_4") (pin "27") (pinfunction "DVSS_27") (pintype "passive"))
      (node (ref "U1_4") (pin "38") (pinfunction "OVSS0_38") (pintype "passive"))
      (node (ref "U1_4") (pin "49") (pinfunction "EP_49") (pintype "passive"))
      (node (ref "U1_4") (pin "5") (pinfunction "VSSA_PLL_5") (pintype "passive"))
      (node (ref "U1_4") (pin "8") (pinfunction "VSS_PLL_8") (pintype "passive"))
      (node (ref "U1_5") (pin "12") (pinfunction "DVSS_12") (pintype "passive"))
      (node (ref "U1_5") (pin "23") (pinfunction "OVSS1_23") (pintype "passive"))
      (node (ref "U1_5") (pin "27") (pinfunction "DVSS_27") (pintype "passive"))
      (node (ref "U1_5") (pin "38") (pinfunction "OVSS0_38") (pintype "passive"))
      (node (ref "U1_5") (pin "49") (pinfunction "EP_49") (pintype "passive"))
      (node (ref "U1_5") (pin "5") (pinfunction "VSSA_PLL_5") (pintype "passive"))
      (node (ref "U1_5") (pin "8") (pinfunction "VSS_PLL_8") (pintype "passive"))
      (node (ref "U1_6") (pin "12") (pinfunction "DVSS_12") (pintype "passive"))
      (node (ref "U1_6") (pin "23") (pinfunction "OVSS1_23") (pintype "passive"))
      (node (ref "U1_6") (pin "27") (pinfunction "DVSS_27") (pintype "passive"))
      (node (ref "U1_6") (pin "38") (pinfunction "OVSS0_38") (pintype "passive"))
      (node (ref "U1_6") (pin "49") (pinfunction "EP_49") (pintype "passive"))
      (node (ref "U1_6") (pin "5") (pinfunction "VSSA_PLL_5") (pintype "passive"))
      (node (ref "U1_6") (pin "8") (pinfunction "VSS_PLL_8") (pintype "passive"))
      (node (ref "U1_7") (pin "12") (pinfunction "DVSS_12") (pintype "passive"))
      (node (ref "U1_7") (pin "23") (pinfunction "OVSS1_23") (pintype "passive"))
      (node (ref "U1_7") (pin "27") (pinfunction "DVSS_27") (pintype "passive"))
      (node (ref "U1_7") (pin "38") (pinfunction "OVSS0_38") (pintype "passive"))
      (node (ref "U1_7") (pin "49") (pinfunction "EP_49") (pintype "passive"))
      (node (ref "U1_7") (pin "5") (pinfunction "VSSA_PLL_5") (pintype "passive"))
      (node (ref "U1_7") (pin "8") (pinfunction "VSS_PLL_8") (pintype "passive"))
      (node (ref "U1_8") (pin "12") (pinfunction "DVSS_12") (pintype "passive"))
      (node (ref "U1_8") (pin "23") (pinfunction "OVSS1_23") (pintype "passive"))
      (node (ref "U1_8") (pin "27") (pinfunction "DVSS_27") (pintype "passive"))
      (node (ref "U1_8") (pin "38") (pinfunction "OVSS0_38") (pintype "passive"))
      (node (ref "U1_8") (pin "49") (pinfunction "EP_49") (pintype "passive"))
      (node (ref "U1_8") (pin "5") (pinfunction "VSSA_PLL_5") (pintype "passive"))
      (node (ref "U1_8") (pin "8") (pinfunction "VSS_PLL_8") (pintype "passive"))
      (node (ref "U1_9") (pin "12") (pinfunction "DVSS_12") (pintype "passive"))
      (node (ref "U1_9") (pin "23") (pinfunction "OVSS1_23") (pintype "passive"))
      (node (ref "U1_9") (pin "27") (pinfunction "DVSS_27") (pintype "passive"))
      (node (ref "U1_9") (pin "38") (pinfunction "OVSS0_38") (pintype "passive"))
      (node (ref "U1_9") (pin "49") (pinfunction "EP_49") (pintype "passive"))
      (node (ref "U1_9") (pin "5") (pinfunction "VSSA_PLL_5") (pintype "passive"))
      (node (ref "U1_9") (pin "8") (pinfunction "VSS_PLL_8") (pintype "passive"))
      (node (ref "U2") (pin "2") (pinfunction "GND_2") (pintype "passive"))
      (node (ref "U2") (pin "3") (pinfunction "GND_3") (pintype "passive"))
      (node (ref "U2") (pin "4") (pinfunction "N.C._4") (pintype "passive"))
      (node (ref "U2") (pin "5") (pinfunction "N.C._5") (pintype "passive"))
      (node (ref "U2") (pin "6") (pinfunction "GND_6") (pintype "passive"))
      (node (ref "U2") (pin "7") (pinfunction "GND_7") (pintype "passive"))
      (node (ref "U3") (pin "2") (pinfunction "GND_2") (pintype "passive"))
      (node (ref "U4") (pin "2") (pinfunction "GND_2") (pintype "passive"))
      (node (ref "U5") (pin "2") (pinfunction "GND_2") (pintype "passive"))
      (node (ref "U6") (pin "6") (pinfunction "GND_6") (pintype "passive"))
      (node (ref "U6") (pin "7") (pinfunction "GND_7") (pintype "passive"))
      (node (ref "U7") (pin "6") (pinfunction "GND_6") (pintype "passive"))
      (node (ref "U7") (pin "7") (pinfunction "GND_7") (pintype "passive"))
    )
    (net (code "128") (name "unconnected-(J2-Pad4)") (class "Default")
      (node (ref "J2") (pin "4") (pinfunction "4_4") (pintype "passive"))
    )
    (net (code "129") (name "unconnected-(U1-C3IN1+{slash}VCMPST3{slash}RP71{slash}RD7-Pad55)") (class "Default")
      (node (ref "U1") (pin "55") (pinfunction "C3IN1+/VCMPST3/RP71/RD7_55") (pintype "passive"))
    )
    (net (code "130") (name "unconnected-(U6-GND-Pad2)") (class "Default")
      (node (ref "U6") (pin "2") (pinfunction "GND_2") (pintype "passive"))
    )
    (net (code "131") (name "unconnected-(U6-GND-Pad3)") (class "Default")
      (node (ref "U6") (pin "3") (pinfunction "GND_3") (pintype "passive"))
    )
    (net (code "132") (name "unconnected-(U6-N.C.-Pad4)") (class "Default")
      (node (ref "U6") (pin "4") (pinfunction "N.C._4") (pintype "passive"))
    )
    (net (code "133") (name "unconnected-(U7-GND-Pad2)") (class "Default")
      (node (ref "U7") (pin "2") (pinfunction "GND_2") (pintype "passive"))
    )
    (net (code "134") (name "unconnected-(U7-GND-Pad3)") (class "Default")
      (node (ref "U7") (pin "3") (pinfunction "GND_3") (pintype "passive"))
    )
    (net (code "135") (name "unconnected-(U7-N.C.-Pad4)") (class "Default")
      (node (ref "U7") (pin "4") (pinfunction "N.C._4") (pintype "passive"))
    )
  )
)
